# oresat-live-card.net
KiCad netlist of a schematic drawn in EAGLE
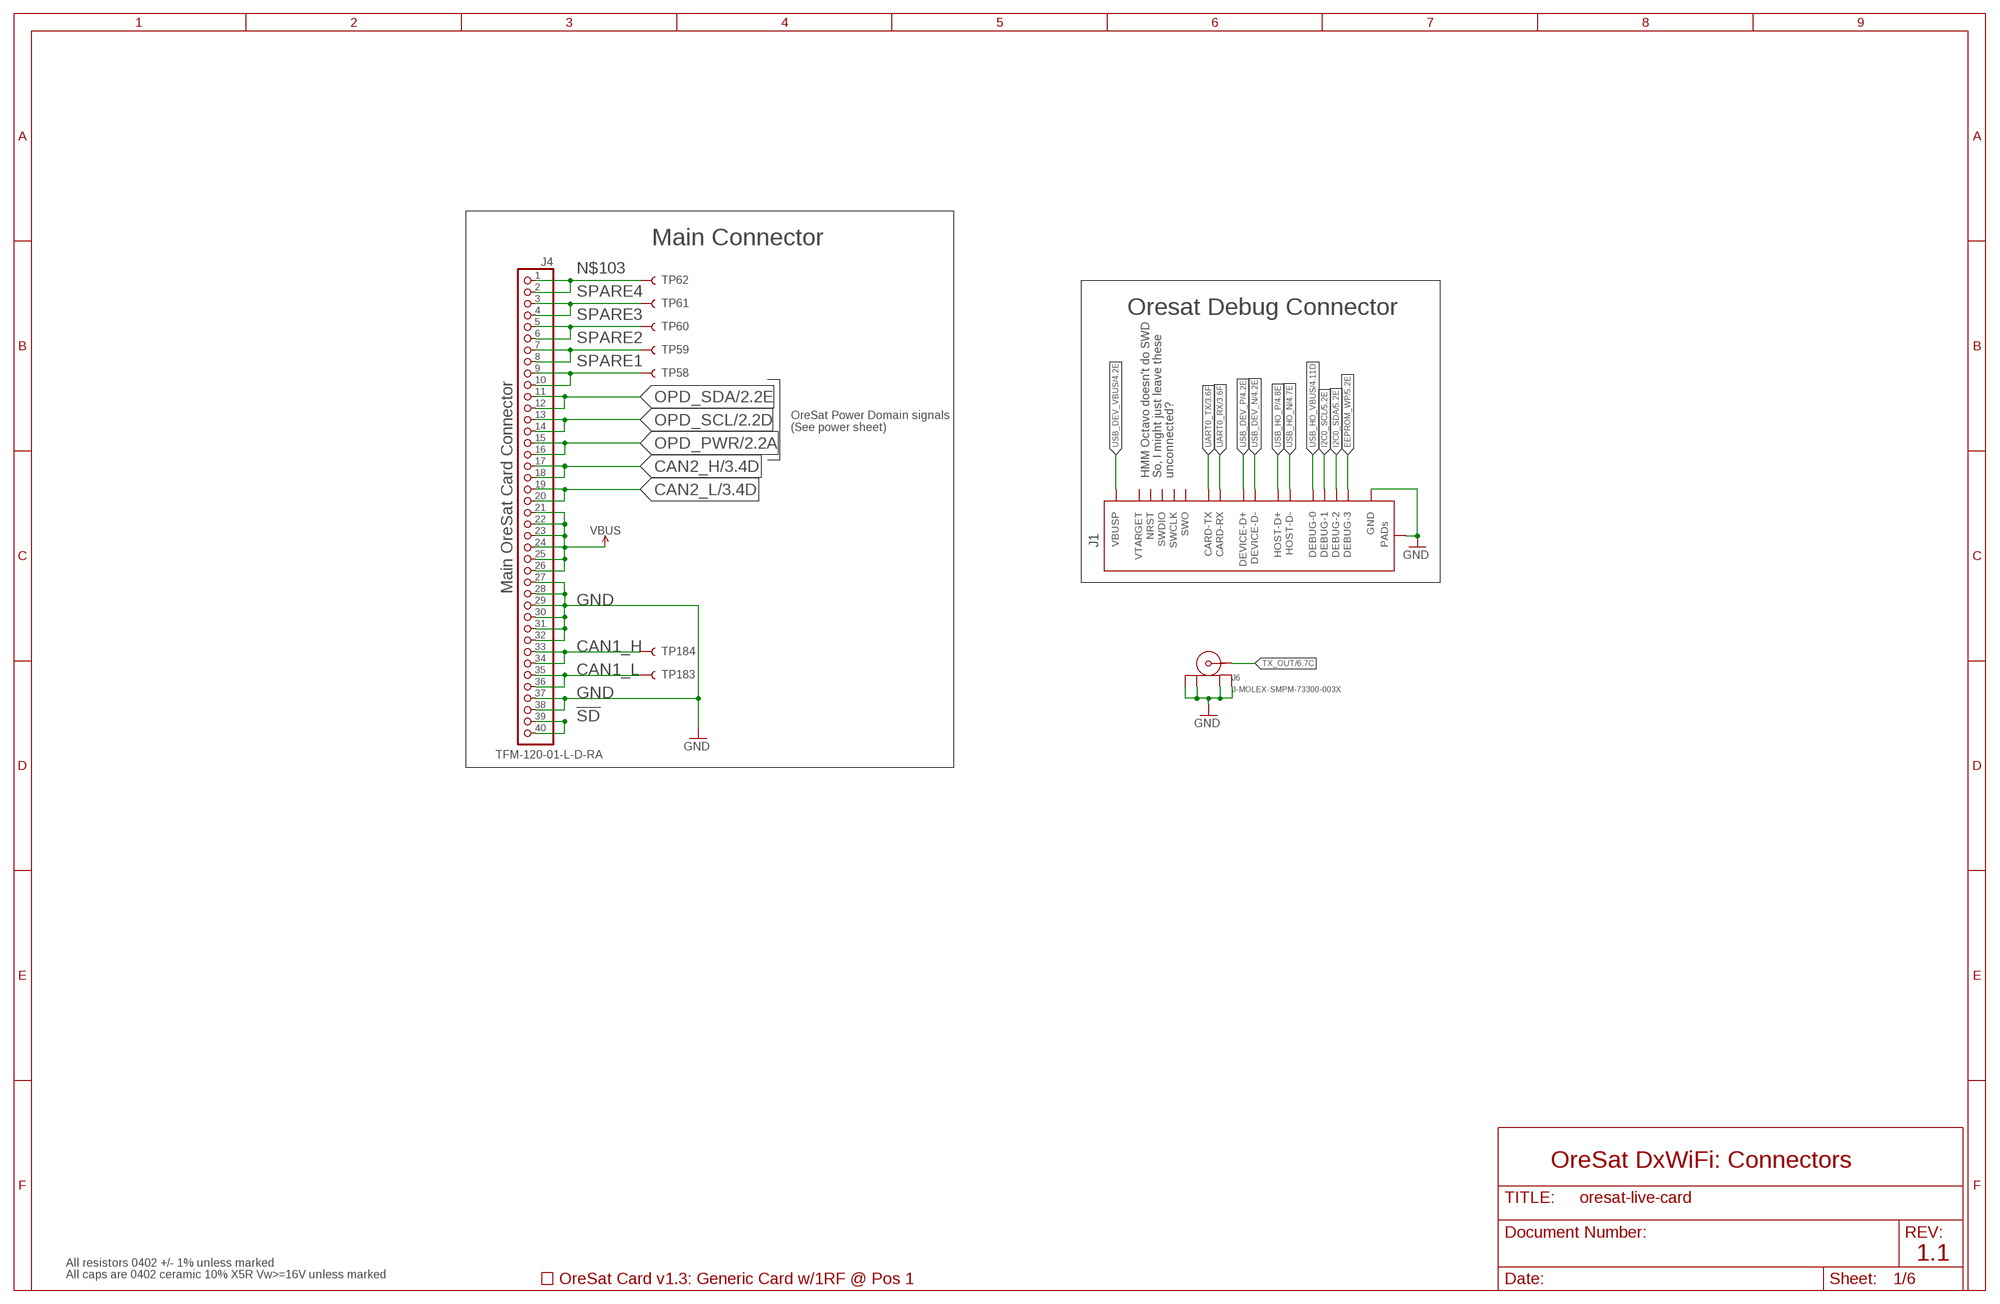
[diagram p0: schematic, sheet 1]
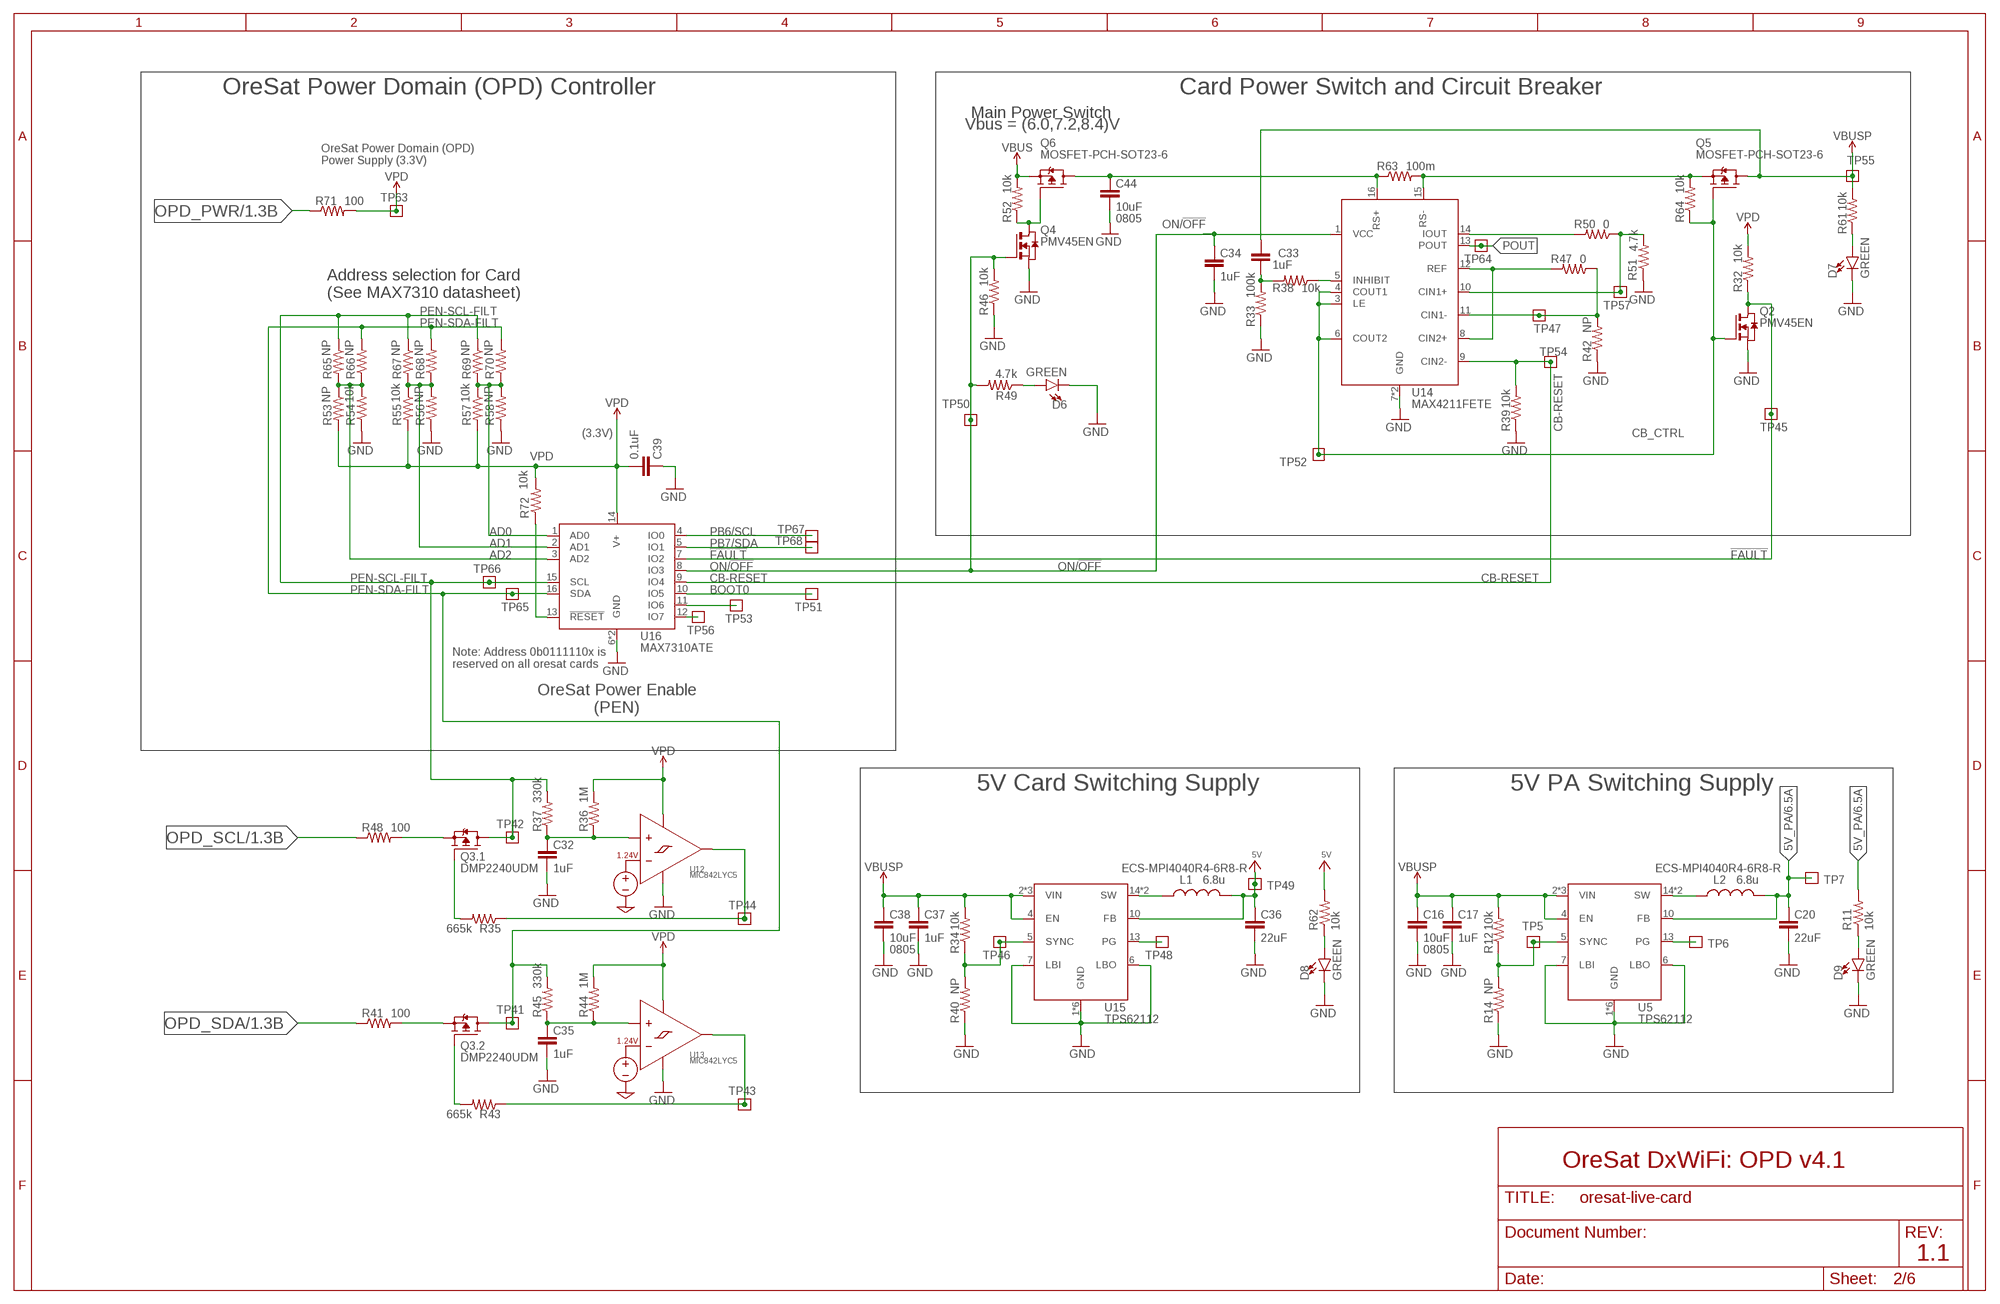
[diagram p1: schematic, sheet 2]
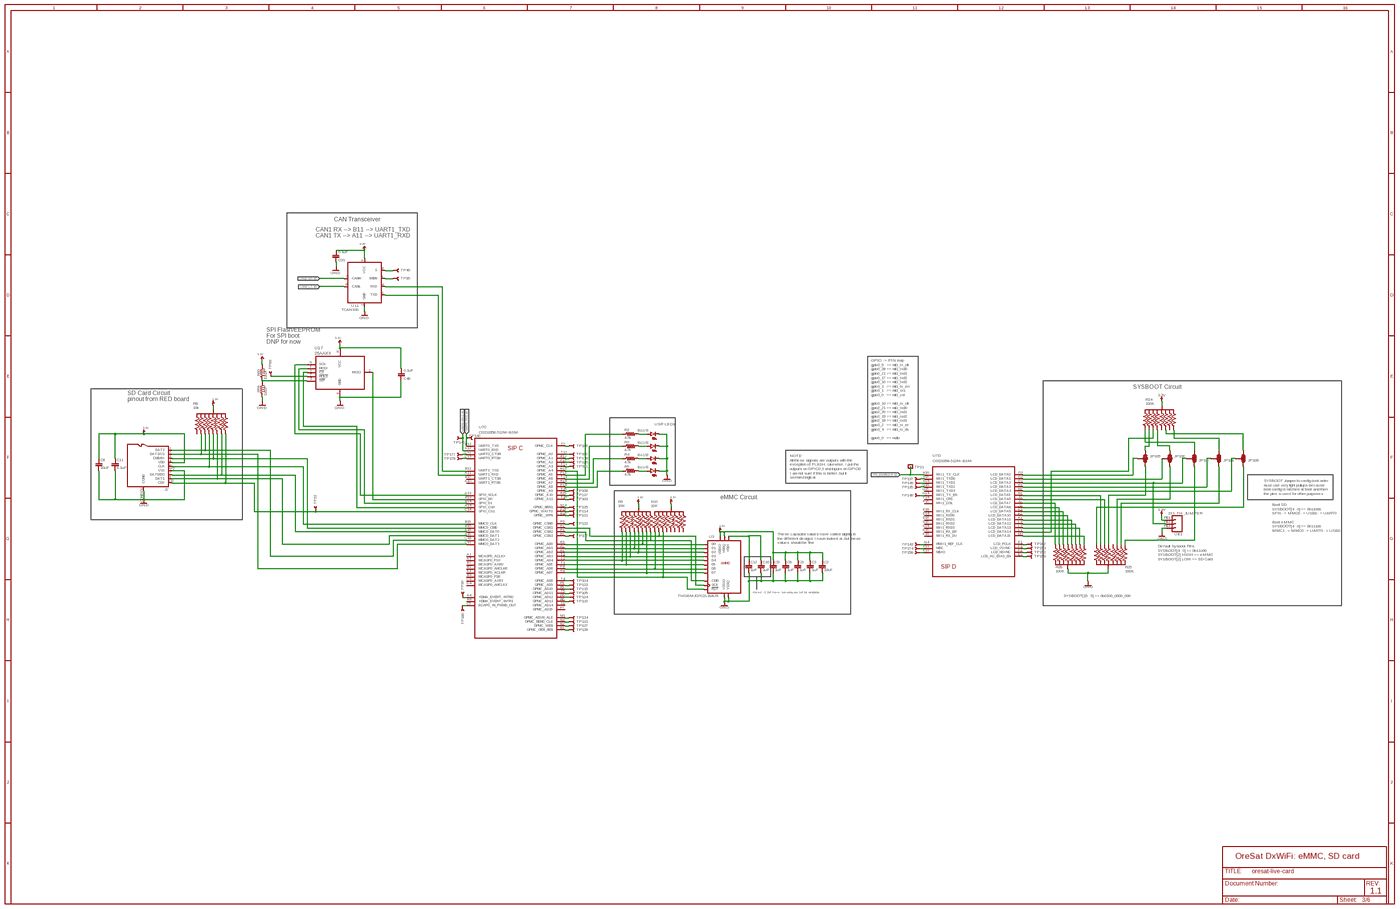
[diagram p2: schematic, sheet 3, overview]
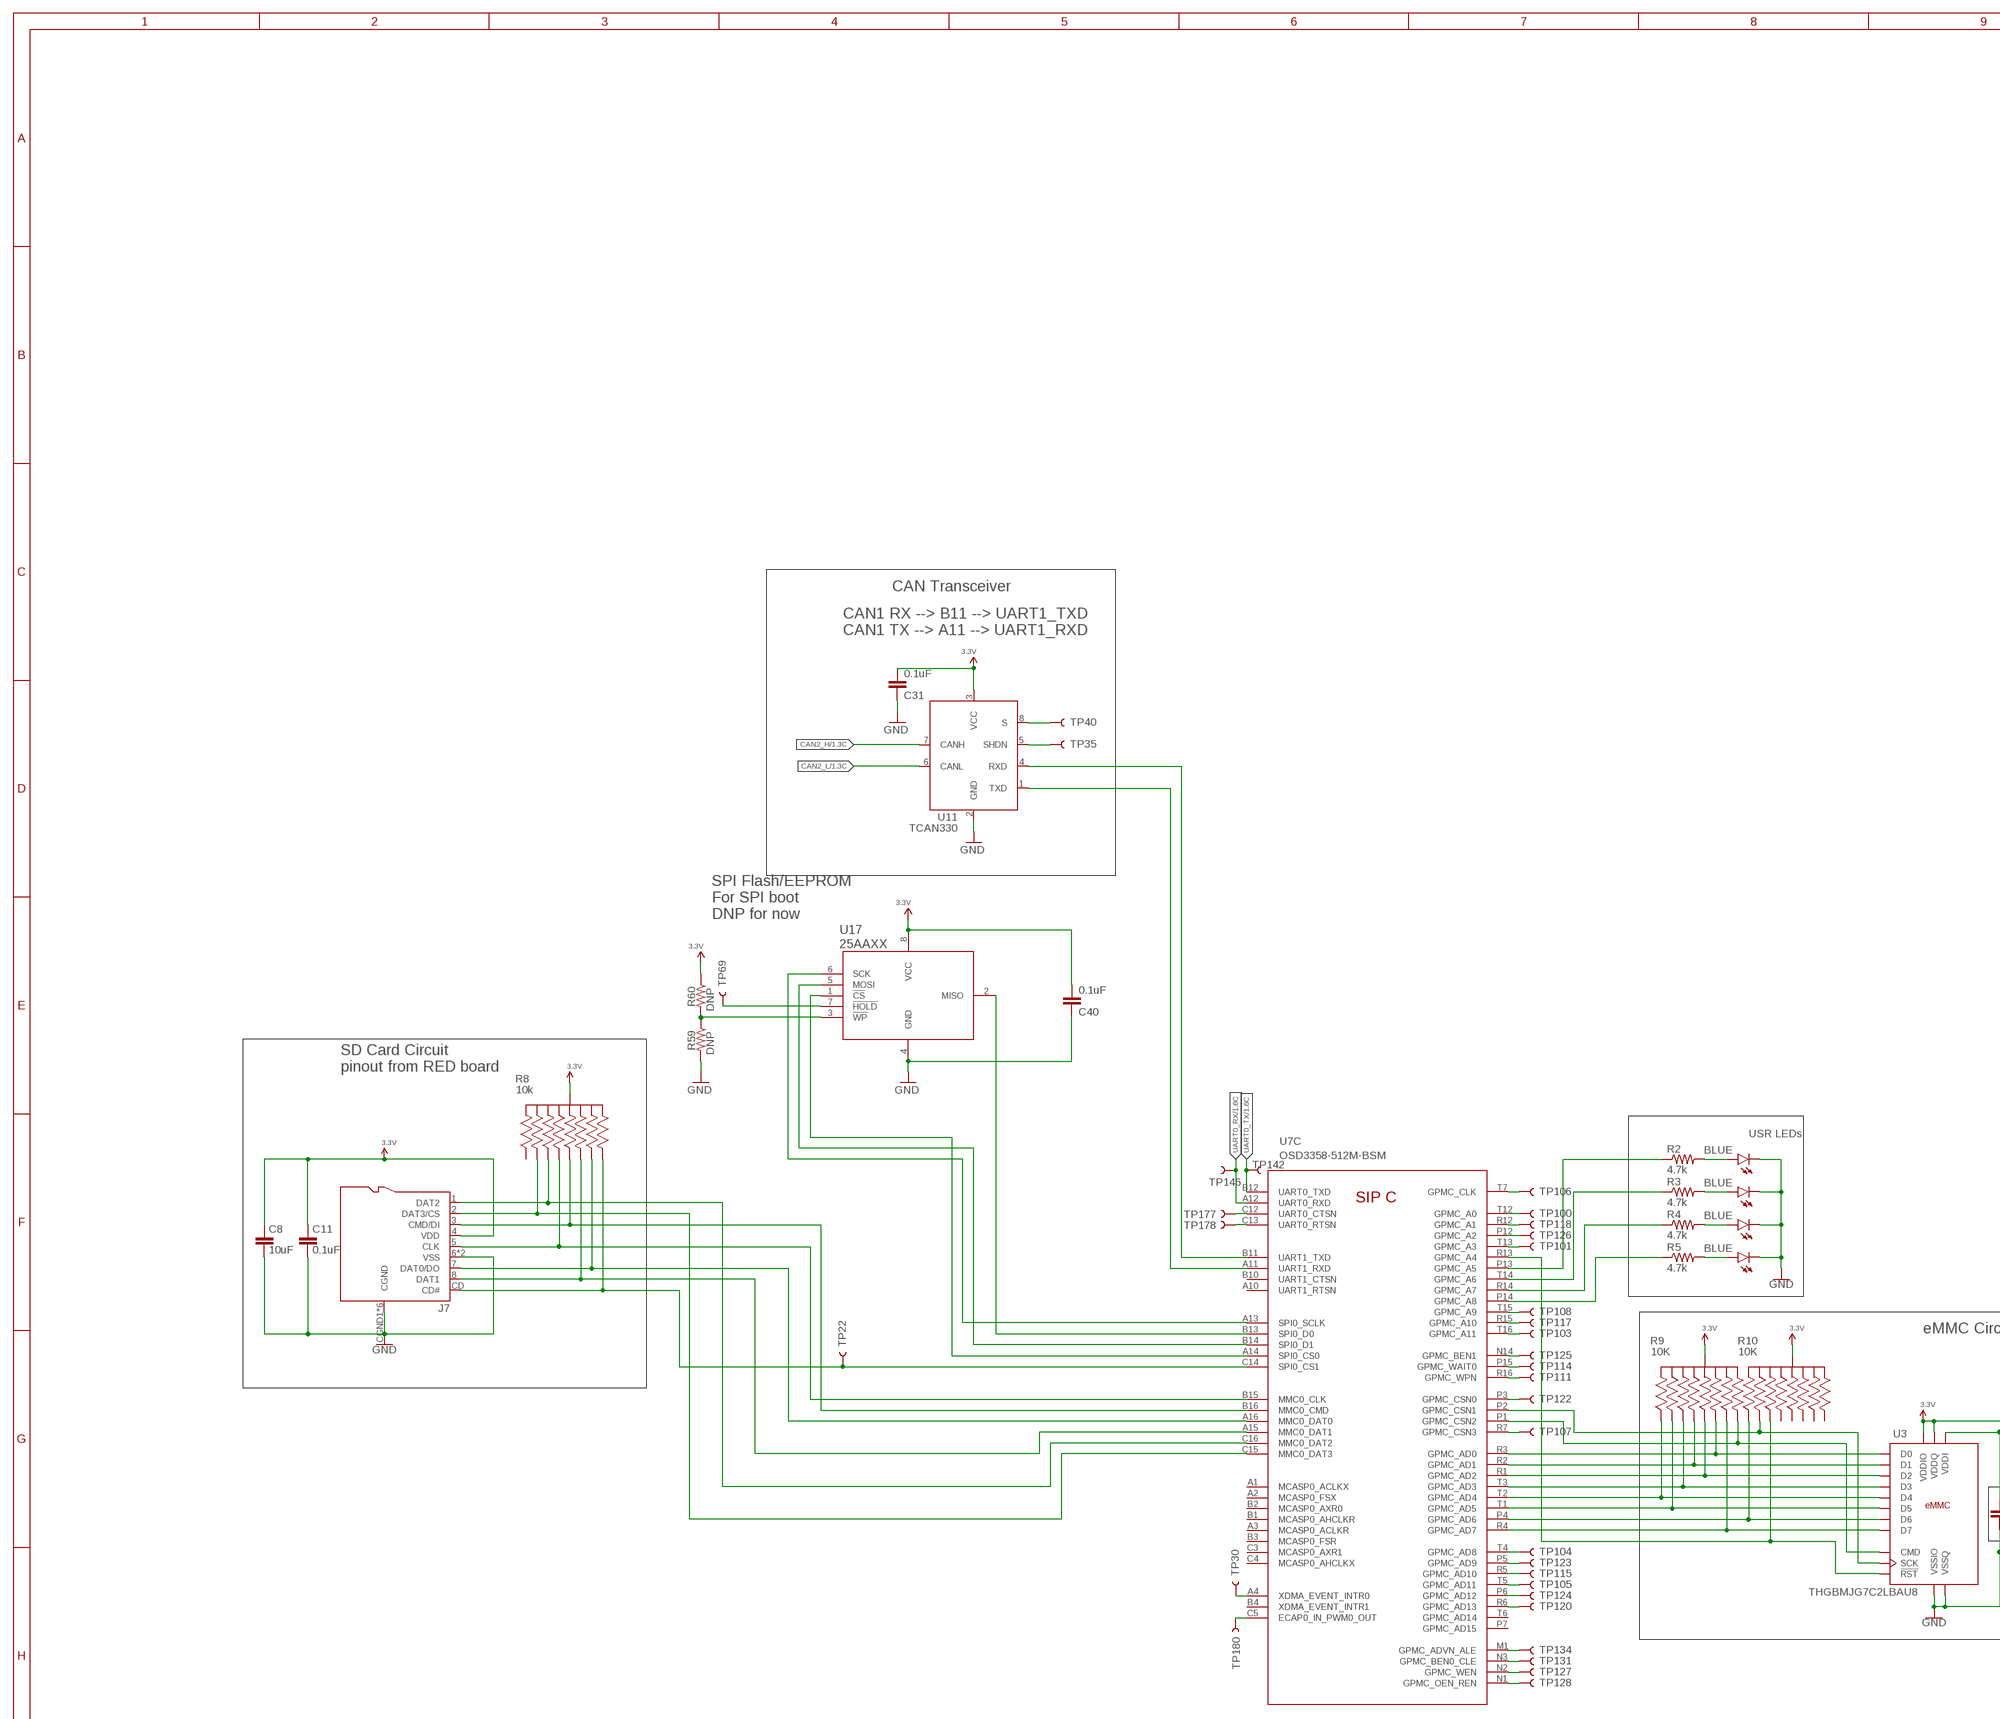
[diagram p3: schematic, sheet 3, part 1 of 4]
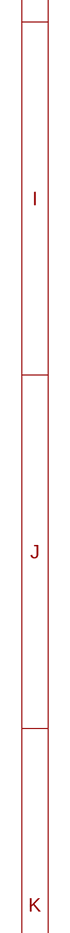
[diagram p4: schematic, sheet 3, part 2 of 4]
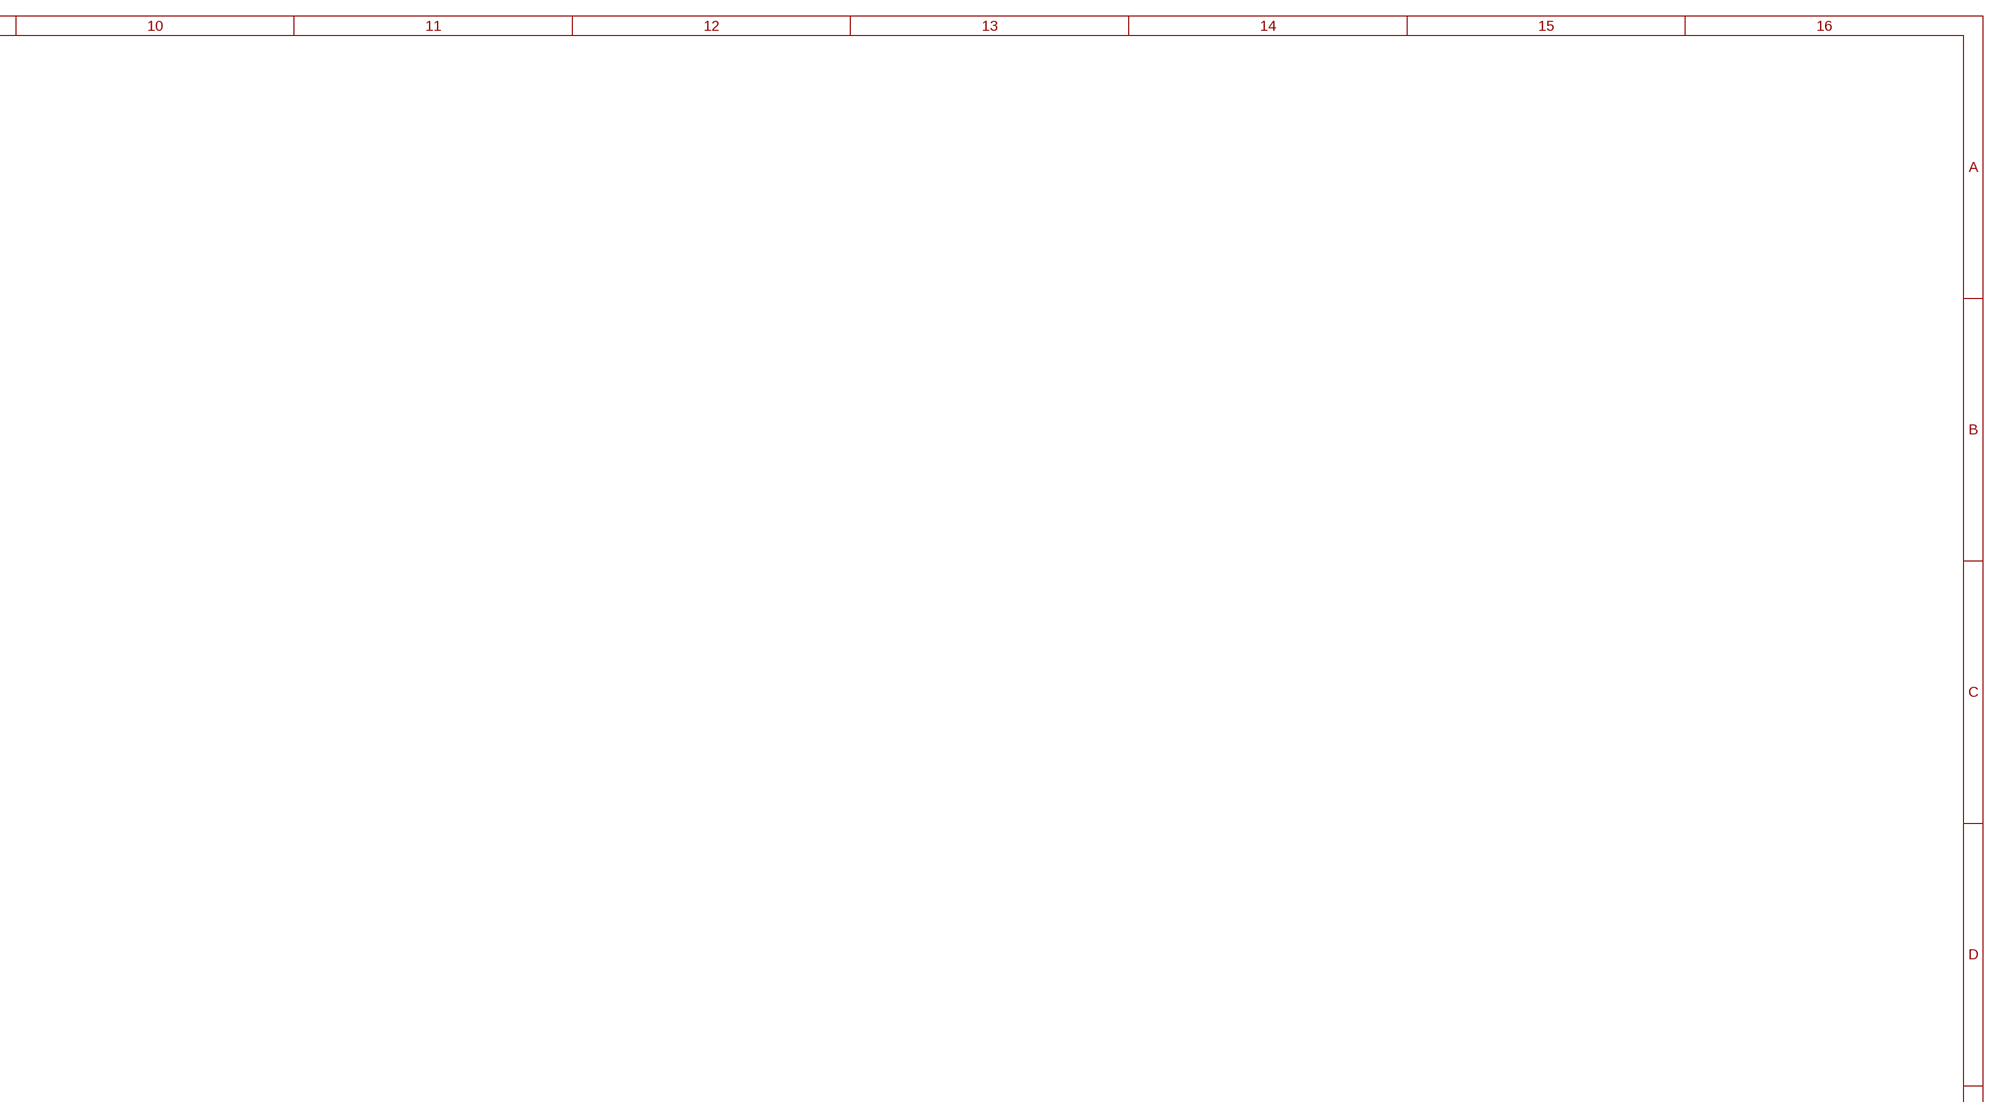
[diagram p5: schematic, sheet 3, part 3 of 4]
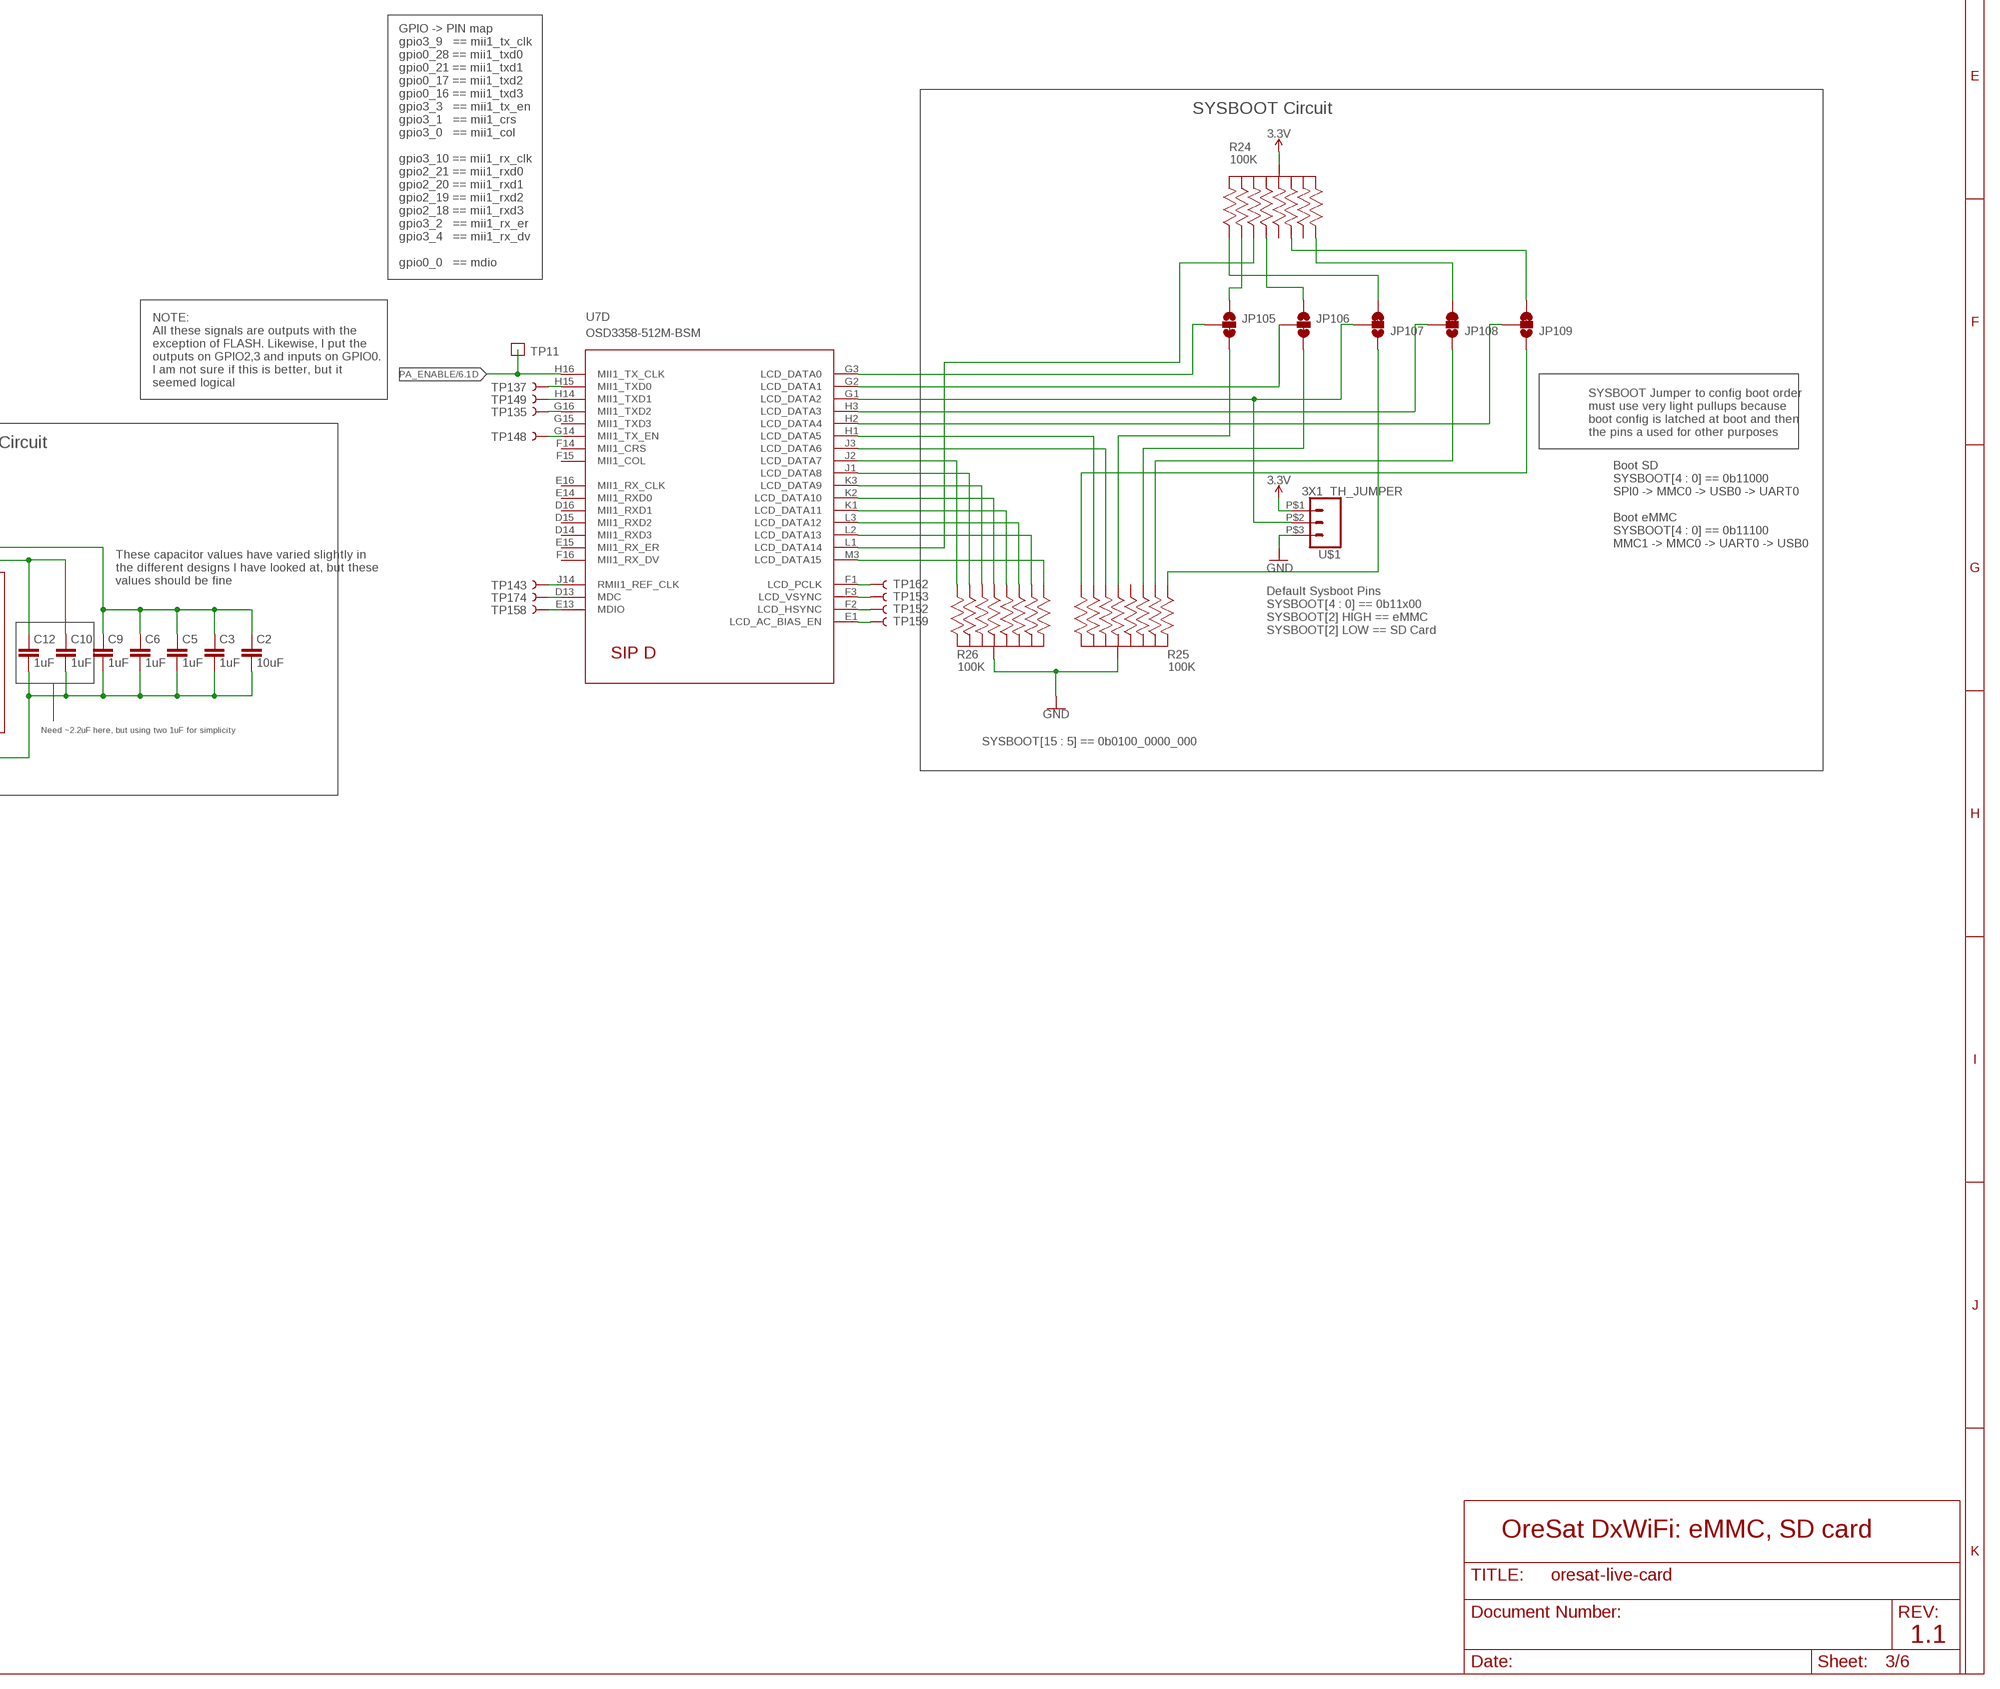
[diagram p6: schematic, sheet 3, part 4 of 4]
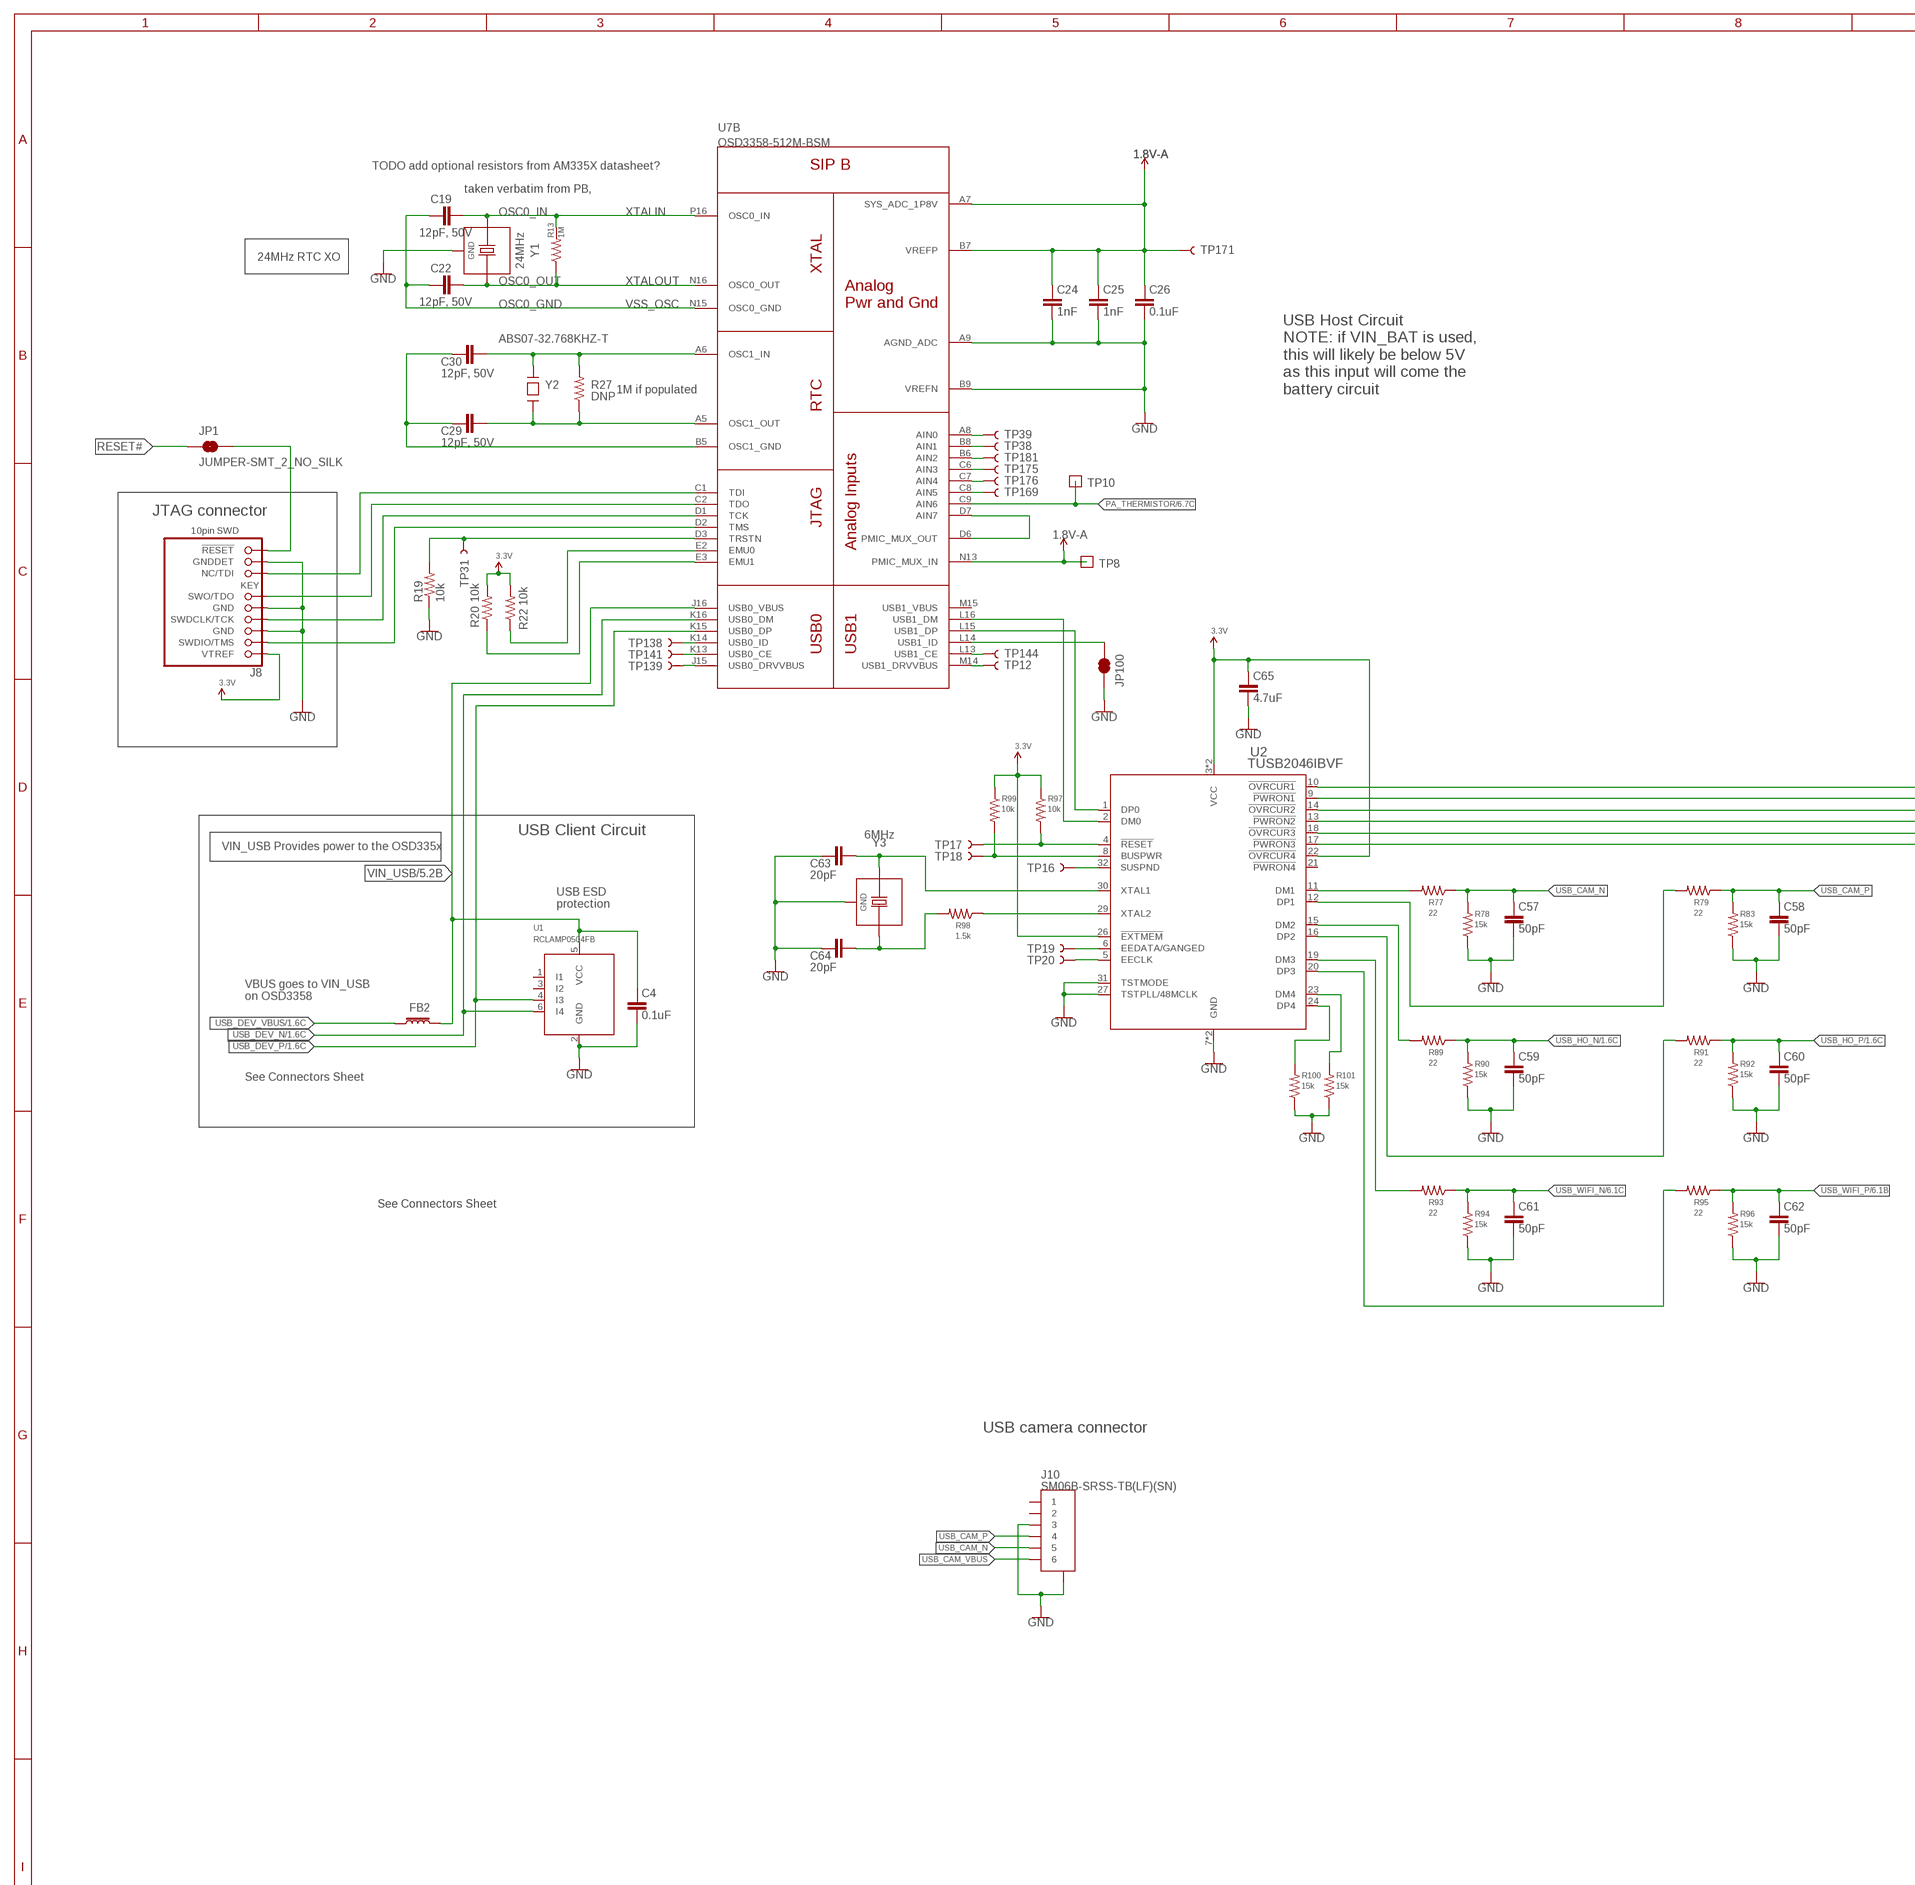
[diagram p7: schematic, sheet 4, part 1 of 2]
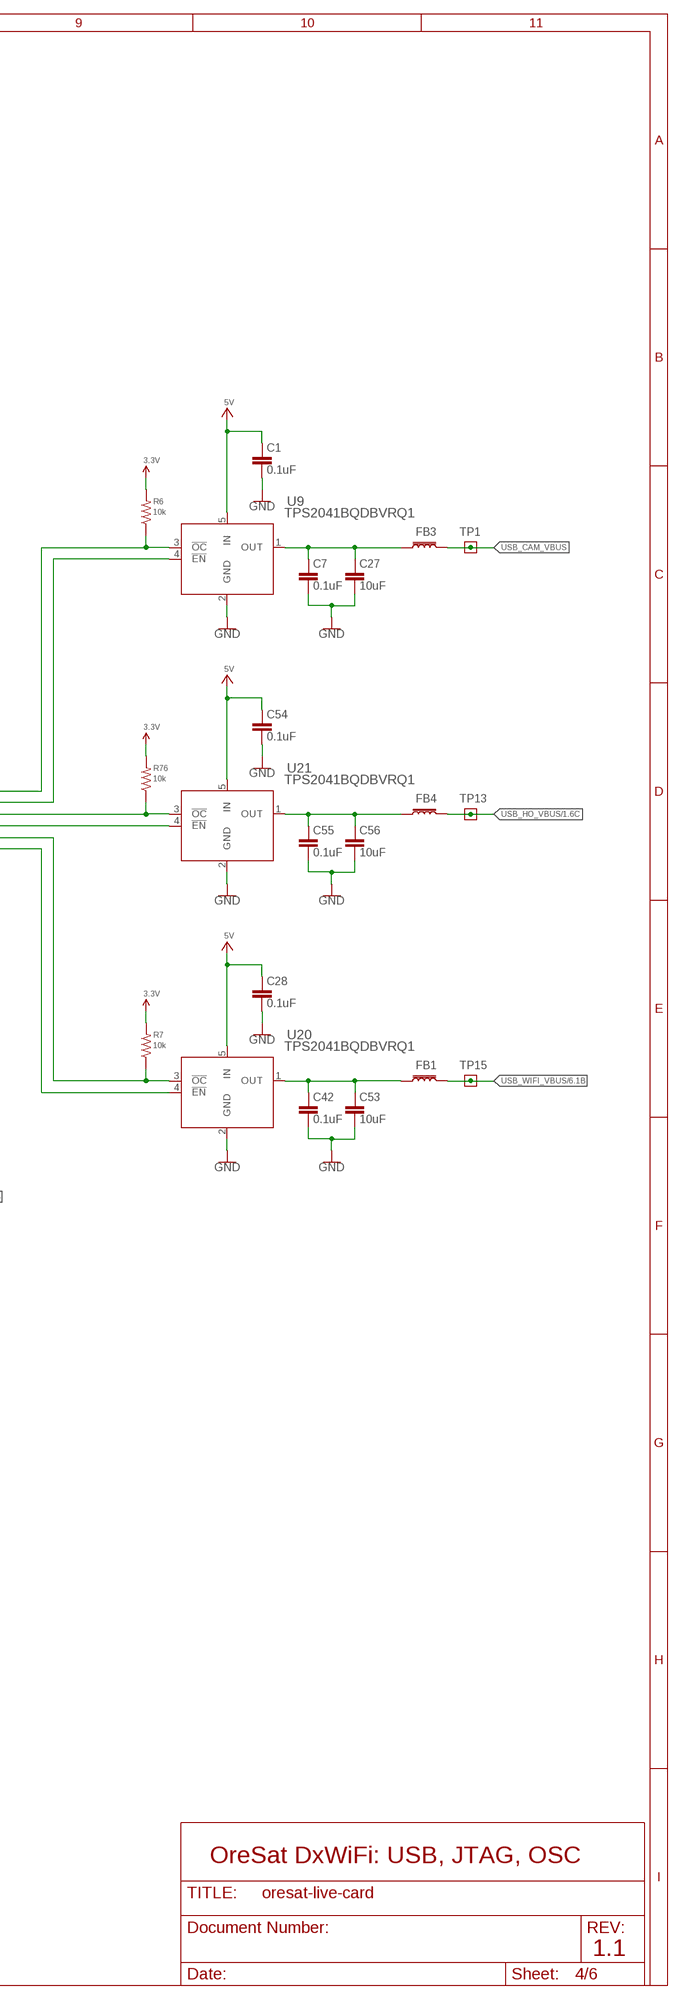
[diagram p8: schematic, sheet 4, part 2 of 2]
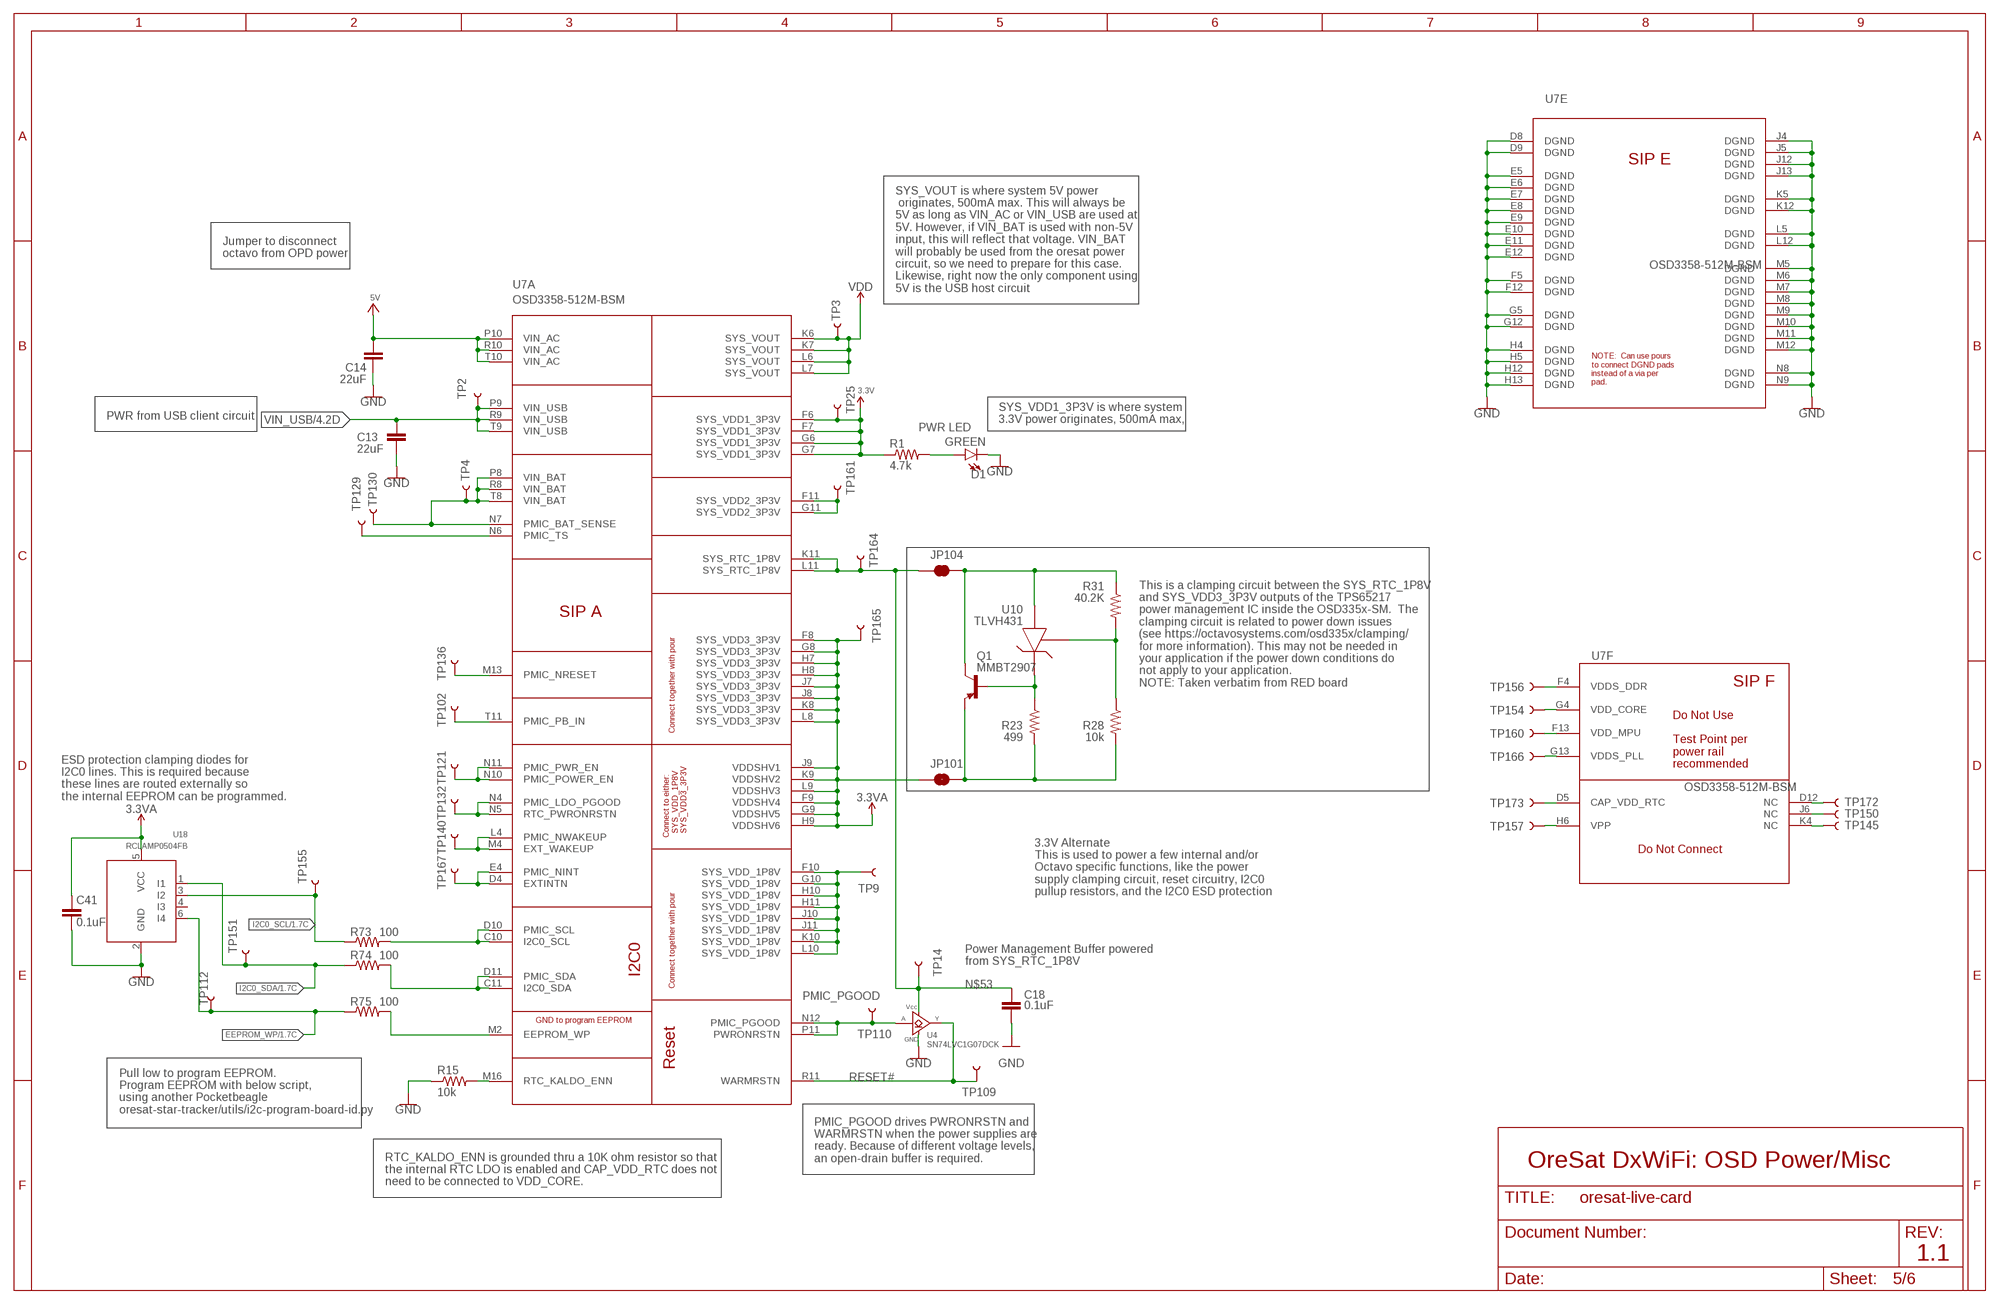
[diagram p9: schematic, sheet 5]
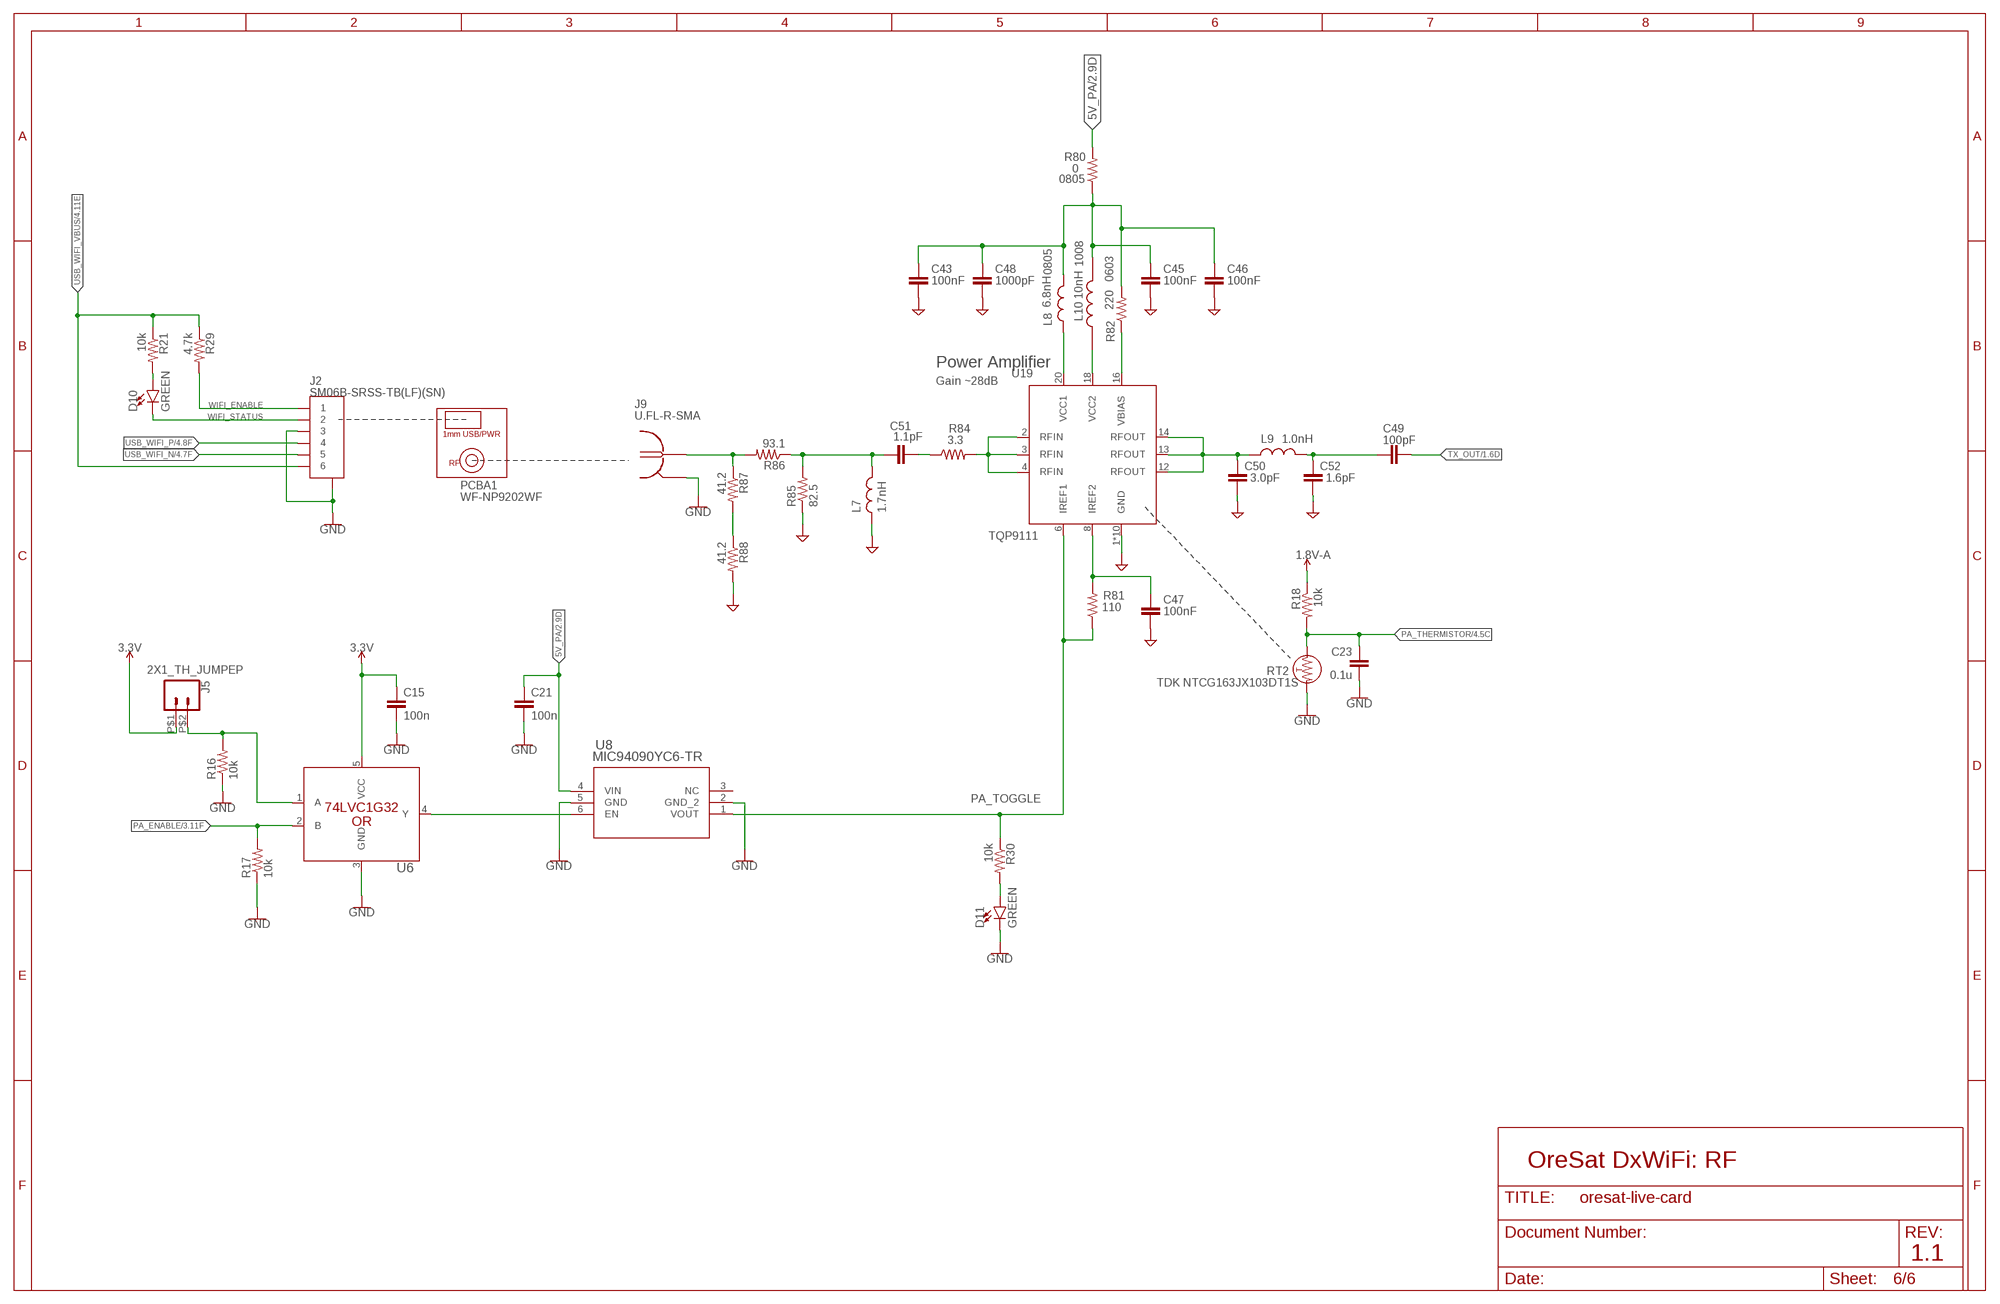
[diagram p10: schematic, sheet 6]

(export (version "E")
  (design (tool "Eeschema 10.0.6"))
  (components
    (comp (ref "C1")
      (value "0.1uF")
      (footprint "eagle-import:.0603-A")
      (libsource (lib "eagle-import") (part "C-EU0603-A"))
    )
    (comp (ref "C4")
      (value "0.1uF")
      (footprint "eagle-import:.0603-A")
      (libsource (lib "eagle-import") (part "C-EU0603-A"))
    )
    (comp (ref "C7")
      (value "0.1uF")
      (footprint "eagle-import:.0603-A")
      (libsource (lib "eagle-import") (part "C-EU0603-A"))
    )
    (comp (ref "C19")
      (value "12pF, 50V")
      (footprint "eagle-import:.0603-A")
      (libsource (lib "eagle-import") (part "C-EU0603-A"))
    )
    (comp (ref "C22")
      (value "12pF, 50V")
      (footprint "eagle-import:.0603-A")
      (libsource (lib "eagle-import") (part "C-EU0603-A"))
    )
    (comp (ref "C24")
      (value "1nF")
      (footprint "eagle-import:.0805-B")
      (libsource (lib "eagle-import") (part "C-EU0805-B"))
    )
    (comp (ref "C25")
      (value "1nF")
      (footprint "eagle-import:.0805-B")
      (libsource (lib "eagle-import") (part "C-EU0805-B"))
    )
    (comp (ref "C26")
      (value "0.1uF")
      (footprint "eagle-import:.0805-B")
      (libsource (lib "eagle-import") (part "C-EU0805-B"))
    )
    (comp (ref "C27")
      (value "10uF")
      (footprint "eagle-import:.0603-A")
      (libsource (lib "eagle-import") (part "C-EU0603-A"))
    )
    (comp (ref "C28")
      (value "0.1uF")
      (footprint "eagle-import:.0603-A")
      (libsource (lib "eagle-import") (part "C-EU0603-A"))
    )
    (comp (ref "C29")
      (value "12pF, 50V")
      (footprint "eagle-import:.0603-A")
      (libsource (lib "eagle-import") (part "C-EU0603-A"))
    )
    (comp (ref "C30")
      (value "12pF, 50V")
      (footprint "eagle-import:.0603-A")
      (libsource (lib "eagle-import") (part "C-EU0603-A"))
    )
    (comp (ref "C42")
      (value "0.1uF")
      (footprint "eagle-import:.0603-A")
      (libsource (lib "eagle-import") (part "C-EU0603-A"))
    )
    (comp (ref "C53")
      (value "10uF")
      (footprint "eagle-import:.0603-A")
      (libsource (lib "eagle-import") (part "C-EU0603-A"))
    )
    (comp (ref "C54")
      (value "0.1uF")
      (footprint "eagle-import:.0603-A")
      (libsource (lib "eagle-import") (part "C-EU0603-A"))
    )
    (comp (ref "C55")
      (value "0.1uF")
      (footprint "eagle-import:.0603-A")
      (libsource (lib "eagle-import") (part "C-EU0603-A"))
    )
    (comp (ref "C56")
      (value "10uF")
      (footprint "eagle-import:.0603-A")
      (libsource (lib "eagle-import") (part "C-EU0603-A"))
    )
    (comp (ref "C57")
      (value "50pF")
      (footprint "eagle-import:.0603-A")
      (libsource (lib "eagle-import") (part "C-EU0603-A"))
    )
    (comp (ref "C58")
      (value "50pF")
      (footprint "eagle-import:.0603-A")
      (libsource (lib "eagle-import") (part "C-EU0603-A"))
    )
    (comp (ref "C59")
      (value "50pF")
      (footprint "eagle-import:.0603-A")
      (libsource (lib "eagle-import") (part "C-EU0603-A"))
    )
    (comp (ref "C60")
      (value "50pF")
      (footprint "eagle-import:.0603-A")
      (libsource (lib "eagle-import") (part "C-EU0603-A"))
    )
    (comp (ref "C61")
      (value "50pF")
      (footprint "eagle-import:.0603-A")
      (libsource (lib "eagle-import") (part "C-EU0603-A"))
    )
    (comp (ref "C62")
      (value "50pF")
      (footprint "eagle-import:.0603-A")
      (libsource (lib "eagle-import") (part "C-EU0603-A"))
    )
    (comp (ref "C63")
      (value "20pF")
      (footprint "eagle-import:.0603-A")
      (libsource (lib "eagle-import") (part "C-EU0603-A"))
    )
    (comp (ref "C64")
      (value "20pF")
      (footprint "eagle-import:.0603-A")
      (libsource (lib "eagle-import") (part "C-EU0603-A"))
    )
    (comp (ref "C65")
      (value "4.7uF")
      (footprint "eagle-import:.0603-A")
      (libsource (lib "eagle-import") (part "C-EU0603-A"))
    )
    (comp (ref "FB1")
      (value "30Ω/1.8A")
      (footprint "eagle-import:0603")
      (fields (field (name "MPN") "BLM18KG300JH1D"))
      (libsource (lib "eagle-import") (part "FERRITE_BEAD-0603"))
    )
    (comp (ref "FB2")
      (value "30Ω/1.8A")
      (footprint "eagle-import:0603")
      (fields (field (name "MPN") "BLM18KG300JH1D"))
      (libsource (lib "eagle-import") (part "FERRITE_BEAD-0603"))
    )
    (comp (ref "FB3")
      (value "30Ω/1.8A")
      (footprint "eagle-import:0603")
      (fields (field (name "MPN") "BLM18KG300JH1D"))
      (libsource (lib "eagle-import") (part "FERRITE_BEAD-0603"))
    )
    (comp (ref "FB4")
      (value "30Ω/1.8A")
      (footprint "eagle-import:0603")
      (fields (field (name "MPN") "BLM18KG300JH1D"))
      (libsource (lib "eagle-import") (part "FERRITE_BEAD-0603"))
    )
    (comp (ref "J8")
      (value "FTSH-105-XX-X-DV-K")
      (footprint "eagle-import:CON10_2X5_DUK_FTSH")
      (libsource (lib "eagle-import") (part "FTSH-105-XX-X-DV-K"))
    )
    (comp (ref "J10")
      (value "SM06B-SRSS-TB(LF)(SN)")
      (footprint "eagle-import:CONN_SM06B-SRSS-TB_JST")
      (fields (field (name "COPYRIGHT") "Copyright (C) 2018 Accelerated Designs. All rights reserved"))
      (libsource (lib "eagle-import") (part "SM06B-SRSS-TB(LF)(SN)"))
    )
    (comp (ref "JP1")
      (value "JUMPER-SMT_2_NO_SILK")
      (footprint "eagle-import:SMT-JUMPER_2_NO_SILK")
      (libsource (lib "eagle-import") (part "JUMPER-SMT_2_NO_SILK"))
    )
    (comp (ref "JP100")
      (value "JUMPER-SMT_2_NC_TRACE_SILK")
      (footprint "eagle-import:SMT-JUMPER_2_NC_TRACE_SILK")
      (libsource (lib "eagle-import") (part "JUMPER-SMT_2_NC_TRACE_SILK"))
    )
    (comp (ref "R6")
      (value "10k")
      (footprint "eagle-import:.0603-A")
      (libsource (lib "eagle-import") (part "R-US_0603-A"))
    )
    (comp (ref "R7")
      (value "10k")
      (footprint "eagle-import:.0603-A")
      (libsource (lib "eagle-import") (part "R-US_0603-A"))
    )
    (comp (ref "R13")
      (value "1M")
      (footprint "eagle-import:.0603-A")
      (libsource (lib "eagle-import") (part "R-US_0603-A"))
    )
    (comp (ref "R19")
      (value "10k")
      (footprint "eagle-import:.0603-A")
      (libsource (lib "eagle-import") (part "R-US_0603-A"))
    )
    (comp (ref "R20")
      (value "10k")
      (footprint "eagle-import:.0603-A")
      (libsource (lib "eagle-import") (part "R-US_0603-A"))
    )
    (comp (ref "R22")
      (value "10k")
      (footprint "eagle-import:.0603-A")
      (libsource (lib "eagle-import") (part "R-US_0603-A"))
    )
    (comp (ref "R27")
      (value "DNP")
      (footprint "eagle-import:.0603-A")
      (libsource (lib "eagle-import") (part "R-US_0603-A"))
    )
    (comp (ref "R76")
      (value "10k")
      (footprint "eagle-import:.0603-A")
      (libsource (lib "eagle-import") (part "R-US_0603-A"))
    )
    (comp (ref "R77")
      (value "22")
      (footprint "eagle-import:.0603-A")
      (libsource (lib "eagle-import") (part "R-US_0603-A"))
    )
    (comp (ref "R78")
      (value "15k")
      (footprint "eagle-import:.0603-A")
      (libsource (lib "eagle-import") (part "R-US_0603-A"))
    )
    (comp (ref "R79")
      (value "22")
      (footprint "eagle-import:.0603-A")
      (libsource (lib "eagle-import") (part "R-US_0603-A"))
    )
    (comp (ref "R83")
      (value "15k")
      (footprint "eagle-import:.0603-A")
      (libsource (lib "eagle-import") (part "R-US_0603-A"))
    )
    (comp (ref "R89")
      (value "22")
      (footprint "eagle-import:.0603-A")
      (libsource (lib "eagle-import") (part "R-US_0603-A"))
    )
    (comp (ref "R90")
      (value "15k")
      (footprint "eagle-import:.0603-A")
      (libsource (lib "eagle-import") (part "R-US_0603-A"))
    )
    (comp (ref "R91")
      (value "22")
      (footprint "eagle-import:.0603-A")
      (libsource (lib "eagle-import") (part "R-US_0603-A"))
    )
    (comp (ref "R92")
      (value "15k")
      (footprint "eagle-import:.0603-A")
      (libsource (lib "eagle-import") (part "R-US_0603-A"))
    )
    (comp (ref "R93")
      (value "22")
      (footprint "eagle-import:.0603-A")
      (libsource (lib "eagle-import") (part "R-US_0603-A"))
    )
    (comp (ref "R94")
      (value "15k")
      (footprint "eagle-import:.0603-A")
      (libsource (lib "eagle-import") (part "R-US_0603-A"))
    )
    (comp (ref "R95")
      (value "22")
      (footprint "eagle-import:.0603-A")
      (libsource (lib "eagle-import") (part "R-US_0603-A"))
    )
    (comp (ref "R96")
      (value "15k")
      (footprint "eagle-import:.0603-A")
      (libsource (lib "eagle-import") (part "R-US_0603-A"))
    )
    (comp (ref "R97")
      (value "10k")
      (footprint "eagle-import:.0603-A")
      (libsource (lib "eagle-import") (part "R-US_0603-A"))
    )
    (comp (ref "R98")
      (value "1.5k")
      (footprint "eagle-import:.0603-A")
      (libsource (lib "eagle-import") (part "R-US_0603-A"))
    )
    (comp (ref "R99")
      (value "10k")
      (footprint "eagle-import:.0603-A")
      (libsource (lib "eagle-import") (part "R-US_0603-A"))
    )
    (comp (ref "R100")
      (value "15k")
      (footprint "eagle-import:.0603-A")
      (libsource (lib "eagle-import") (part "R-US_0603-A"))
    )
    (comp (ref "R101")
      (value "15k")
      (footprint "eagle-import:.0603-A")
      (libsource (lib "eagle-import") (part "R-US_0603-A"))
    )
    (comp (ref "TP1")
      (value "TEST-POINT")
      (footprint "eagle-import:2MM-TEST-POINT")
      (libsource (lib "eagle-import") (part "TEST-POINT"))
    )
    (comp (ref "TP8")
      (value "TEST-POINT")
      (footprint "eagle-import:2MM-TEST-POINT")
      (libsource (lib "eagle-import") (part "TEST-POINT"))
    )
    (comp (ref "TP10")
      (value "TEST-POINT")
      (footprint "eagle-import:2MM-TEST-POINT")
      (libsource (lib "eagle-import") (part "TEST-POINT"))
    )
    (comp (ref "TP12")
      (value "TEST-POINT3X4")
      (footprint "eagle-import:PAD.03X.04")
      (libsource (lib "eagle-import") (part "TEST-POINT3X4"))
    )
    (comp (ref "TP13")
      (value "TEST-POINT")
      (footprint "eagle-import:2MM-TEST-POINT")
      (libsource (lib "eagle-import") (part "TEST-POINT"))
    )
    (comp (ref "TP15")
      (value "TEST-POINT")
      (footprint "eagle-import:2MM-TEST-POINT")
      (libsource (lib "eagle-import") (part "TEST-POINT"))
    )
    (comp (ref "TP16")
      (value "TEST-POINT3X4")
      (footprint "eagle-import:PAD.03X.04")
      (libsource (lib "eagle-import") (part "TEST-POINT3X4"))
    )
    (comp (ref "TP17")
      (value "TEST-POINT3X4")
      (footprint "eagle-import:PAD.03X.04")
      (libsource (lib "eagle-import") (part "TEST-POINT3X4"))
    )
    (comp (ref "TP18")
      (value "TEST-POINT3X4")
      (footprint "eagle-import:PAD.03X.04")
      (libsource (lib "eagle-import") (part "TEST-POINT3X4"))
    )
    (comp (ref "TP19")
      (value "TEST-POINT3X4")
      (footprint "eagle-import:PAD.03X.04")
      (libsource (lib "eagle-import") (part "TEST-POINT3X4"))
    )
    (comp (ref "TP20")
      (value "TEST-POINT3X4")
      (footprint "eagle-import:PAD.03X.04")
      (libsource (lib "eagle-import") (part "TEST-POINT3X4"))
    )
    (comp (ref "TP31")
      (value "TEST-POINT3X4")
      (footprint "eagle-import:PAD.03X.04")
      (libsource (lib "eagle-import") (part "TEST-POINT3X4"))
    )
    (comp (ref "TP38")
      (value "TEST-POINT3X4")
      (footprint "eagle-import:PAD.03X.04")
      (libsource (lib "eagle-import") (part "TEST-POINT3X4"))
    )
    (comp (ref "TP39")
      (value "TEST-POINT3X4")
      (footprint "eagle-import:PAD.03X.04")
      (libsource (lib "eagle-import") (part "TEST-POINT3X4"))
    )
    (comp (ref "TP138")
      (value "TEST-POINT3X4")
      (footprint "eagle-import:PAD.03X.04")
      (libsource (lib "eagle-import") (part "TEST-POINT3X4"))
    )
    (comp (ref "TP139")
      (value "TEST-POINT3X4")
      (footprint "eagle-import:PAD.03X.04")
      (libsource (lib "eagle-import") (part "TEST-POINT3X4"))
    )
    (comp (ref "TP141")
      (value "TEST-POINT3X4")
      (footprint "eagle-import:PAD.03X.04")
      (libsource (lib "eagle-import") (part "TEST-POINT3X4"))
    )
    (comp (ref "TP144")
      (value "TEST-POINT3X4")
      (footprint "eagle-import:PAD.03X.04")
      (libsource (lib "eagle-import") (part "TEST-POINT3X4"))
    )
    (comp (ref "TP169")
      (value "TEST-POINT3X4")
      (footprint "eagle-import:PAD.03X.04")
      (libsource (lib "eagle-import") (part "TEST-POINT3X4"))
    )
    (comp (ref "TP171")
      (value "TEST-POINT3X4")
      (footprint "eagle-import:PAD.03X.04")
      (libsource (lib "eagle-import") (part "TEST-POINT3X4"))
    )
    (comp (ref "TP175")
      (value "TEST-POINT3X4")
      (footprint "eagle-import:PAD.03X.04")
      (libsource (lib "eagle-import") (part "TEST-POINT3X4"))
    )
    (comp (ref "TP176")
      (value "TEST-POINT3X4")
      (footprint "eagle-import:PAD.03X.04")
      (libsource (lib "eagle-import") (part "TEST-POINT3X4"))
    )
    (comp (ref "TP181")
      (value "TEST-POINT3X4")
      (footprint "eagle-import:PAD.03X.04")
      (libsource (lib "eagle-import") (part "TEST-POINT3X4"))
    )
    (comp (ref "U1")
      (value "RCLAMP0504FB")
      (footprint "eagle-import:SC70-6")
      (fields (field (name "MPN") "RCLAMP0504FBTCT"))
      (libsource (lib "eagle-import") (part "RCLAMP0504FB"))
    )
    (comp (ref "U2")
      (value "TUSB2046IBVF")
      (footprint "eagle-import:QFP80P900X900X160-32N")
      (libsource (lib "eagle-import") (part "TUSB2046IBVF"))
    )
    (comp (ref "U7")
      (value "OSD3358-512M-BSM")
      (footprint "eagle-import:OSD335X-BGA-256")
      (fields (field (name "MFR") "Octavo Systems"))
      (libsource (lib "eagle-import") (part "OSD3358-512M-BSM"))
    )
    (comp (ref "U9")
      (value "TPS2041BQDBVRQ1")
      (footprint "eagle-import:DBV5")
      (fields (field (name "COPYRIGHT") "Copyright (C) 2021 Ultra Librarian. All rights reserved."))
      (libsource (lib "eagle-import") (part "TPS2041BQDBVRQ1"))
    )
    (comp (ref "U20")
      (value "TPS2041BQDBVRQ1")
      (footprint "eagle-import:DBV5")
      (fields (field (name "COPYRIGHT") "Copyright (C) 2021 Ultra Librarian. All rights reserved."))
      (libsource (lib "eagle-import") (part "TPS2041BQDBVRQ1"))
    )
    (comp (ref "U21")
      (value "TPS2041BQDBVRQ1")
      (footprint "eagle-import:DBV5")
      (fields (field (name "COPYRIGHT") "Copyright (C) 2021 Ultra Librarian. All rights reserved."))
      (libsource (lib "eagle-import") (part "TPS2041BQDBVRQ1"))
    )
    (comp (ref "Y1")
      (value "24MHz")
      (footprint "eagle-import:5X3.2-4SMD")
      (fields (field (name "MPN") "ECS-240-12-30BQ-AEN-TR"))
      (libsource (lib "eagle-import") (part "ECS-240-12-30BQ-AEN-TR"))
    )
    (comp (ref "Y2")
      (value "ABS07-32.768KHZ-T")
      (footprint "eagle-import:CRYSTAL_3.2X1.5")
      (libsource (lib "eagle-import") (part "ABS07-32.768KHZ-T"))
    )
    (comp (ref "Y3")
      (value "6MHz")
      (footprint "eagle-import:ECS_ECS-060-18-20BM-JEN-TR")
      (fields (field (name "MF") "ECS Inc.") (field (name "MP") "ECS-060-18-20BM-JEN-TR"))
      (libsource (lib "eagle-import") (part "ECS-060-18-20BM-JEN-TR"))
    )
    (comp (ref "J1")
      (value "ORESAT-DEBUG-CONNECTOR-CARD")
      (footprint "eagle-import:TE_2-1734592-0")
      (fields (field (name "MPN") "2-1734592-0"))
      (libsource (lib "eagle-import") (part "ORESAT-DEBUG-CONNECTOR-CARD"))
    )
    (comp (ref "J4")
      (value "TFM-120-01-L-D-RA")
      (footprint "eagle-import:J-SAMTEC-TFM-120-X1-XXX-D-RA")
      (libsource (lib "eagle-import") (part "J-SAMTEC-TFM-120-X1-XXX-D-RA"))
    )
    (comp (ref "J6")
      (value "J-MOLEX-SMPM-73300-003X")
      (footprint "eagle-import:J-MOLEX-SMPM-073300-003X")
      (fields (field (name "MFG") "MOLEX"))
      (libsource (lib "eagle-import") (part "J-MOLEX-SMPM-73300-003X"))
    )
    (comp (ref "PCB1")
      (value "ORESAT-CARD-V1.3-GENERIC-1RF-POS1")
      (footprint "eagle-import:ORESAT-CARD-V1.3-GENERIC-1RF-POS1")
      (libsource (lib "eagle-import") (part "ORESAT-CARD-V1.3-GENERIC-1RF-POS1"))
    )
    (comp (ref "TP58")
      (value "TEST-POINT3X4")
      (footprint "eagle-import:PAD.03X.04")
      (libsource (lib "eagle-import") (part "TEST-POINT3X4"))
    )
    (comp (ref "TP59")
      (value "TEST-POINT3X4")
      (footprint "eagle-import:PAD.03X.04")
      (libsource (lib "eagle-import") (part "TEST-POINT3X4"))
    )
    (comp (ref "TP60")
      (value "TEST-POINT3X4")
      (footprint "eagle-import:PAD.03X.04")
      (libsource (lib "eagle-import") (part "TEST-POINT3X4"))
    )
    (comp (ref "TP61")
      (value "TEST-POINT3X4")
      (footprint "eagle-import:PAD.03X.04")
      (libsource (lib "eagle-import") (part "TEST-POINT3X4"))
    )
    (comp (ref "TP62")
      (value "TEST-POINT3X4")
      (footprint "eagle-import:PAD.03X.04")
      (libsource (lib "eagle-import") (part "TEST-POINT3X4"))
    )
    (comp (ref "TP183")
      (value "TEST-POINT3X4")
      (footprint "eagle-import:PAD.03X.04")
      (libsource (lib "eagle-import") (part "TEST-POINT3X4"))
    )
    (comp (ref "TP184")
      (value "TEST-POINT3X4")
      (footprint "eagle-import:PAD.03X.04")
      (libsource (lib "eagle-import") (part "TEST-POINT3X4"))
    )
    (comp (ref "C2")
      (value "10uF")
      (footprint "eagle-import:.0805-B")
      (libsource (lib "eagle-import") (part "C-EU0805-B"))
    )
    (comp (ref "C3")
      (value "1uF")
      (footprint "eagle-import:.0603-A")
      (libsource (lib "eagle-import") (part "C-EU0603-A"))
    )
    (comp (ref "C5")
      (value "1uF")
      (footprint "eagle-import:.0603-A")
      (libsource (lib "eagle-import") (part "C-EU0603-A"))
    )
    (comp (ref "C6")
      (value "1uF")
      (footprint "eagle-import:.0603-A")
      (libsource (lib "eagle-import") (part "C-EU0603-A"))
    )
    (comp (ref "C8")
      (value "10uF")
      (footprint "eagle-import:.0805-B")
      (libsource (lib "eagle-import") (part "C-EU0805-B"))
    )
    (comp (ref "C9")
      (value "1uF")
      (footprint "eagle-import:.0603-A")
      (libsource (lib "eagle-import") (part "C-EU0603-A"))
    )
    (comp (ref "C10")
      (value "1uF")
      (footprint "eagle-import:.0603-A")
      (libsource (lib "eagle-import") (part "C-EU0603-A"))
    )
    (comp (ref "C11")
      (value "0.1uF")
      (footprint "eagle-import:.0603-A")
      (libsource (lib "eagle-import") (part "C-EU0603-A"))
    )
    (comp (ref "C12")
      (value "1uF")
      (footprint "eagle-import:.0603-A")
      (libsource (lib "eagle-import") (part "C-EU0603-A"))
    )
    (comp (ref "C31")
      (value "0.1uF")
      (footprint "eagle-import:.0603-A")
      (libsource (lib "eagle-import") (part "C-EU0603-A"))
    )
    (comp (ref "C40")
      (value "0.1uF")
      (footprint "eagle-import:.0603-A")
      (libsource (lib "eagle-import") (part "C-EU0603-A"))
    )
    (comp (ref "D2")
      (value "BLUE")
      (footprint "eagle-import:LED-0603")
      (libsource (lib "eagle-import") (part "LED-BLUE0603"))
    )
    (comp (ref "D3")
      (value "BLUE")
      (footprint "eagle-import:LED-0603")
      (libsource (lib "eagle-import") (part "LED-BLUE0603"))
    )
    (comp (ref "D4")
      (value "BLUE")
      (footprint "eagle-import:LED-0603")
      (libsource (lib "eagle-import") (part "LED-BLUE0603"))
    )
    (comp (ref "D5")
      (value "BLUE")
      (footprint "eagle-import:LED-0603")
      (libsource (lib "eagle-import") (part "LED-BLUE0603"))
    )
    (comp (ref "J7")
      (value "DM3BT-DSF-PEJS")
      (footprint "eagle-import:DM3BT-DSF-PEJS")
      (libsource (lib "eagle-import") (part "DM3BT-DSF-PEJS"))
    )
    (comp (ref "JP105")
      (value "JUMPER-SMT_3_1-NC_TRACE_SILK")
      (footprint "eagle-import:SMT-JUMPER_3_1-NC_TRACE_SILK")
      (libsource (lib "eagle-import") (part "JUMPER-SMT_3_1-NC_TRACE_SILK"))
    )
    (comp (ref "JP106")
      (value "JUMPER-SMT_3_1-NC_TRACE_SILK")
      (footprint "eagle-import:SMT-JUMPER_3_1-NC_TRACE_SILK")
      (libsource (lib "eagle-import") (part "JUMPER-SMT_3_1-NC_TRACE_SILK"))
    )
    (comp (ref "JP107")
      (value "JUMPER-SMT_3_1-NC_TRACE_SILK")
      (footprint "eagle-import:SMT-JUMPER_3_1-NC_TRACE_SILK")
      (libsource (lib "eagle-import") (part "JUMPER-SMT_3_1-NC_TRACE_SILK"))
    )
    (comp (ref "JP108")
      (value "JUMPER-SMT_3_1-NC_TRACE_SILK")
      (footprint "eagle-import:SMT-JUMPER_3_1-NC_TRACE_SILK")
      (libsource (lib "eagle-import") (part "JUMPER-SMT_3_1-NC_TRACE_SILK"))
    )
    (comp (ref "JP109")
      (value "JUMPER-SMT_3_1-NC_TRACE_SILK")
      (footprint "eagle-import:SMT-JUMPER_3_1-NC_TRACE_SILK")
      (libsource (lib "eagle-import") (part "JUMPER-SMT_3_1-NC_TRACE_SILK"))
    )
    (comp (ref "R2")
      (value "4.7k")
      (footprint "eagle-import:.0603-A")
      (libsource (lib "eagle-import") (part "R-US_0603-A"))
    )
    (comp (ref "R3")
      (value "4.7k")
      (footprint "eagle-import:.0603-A")
      (libsource (lib "eagle-import") (part "R-US_0603-A"))
    )
    (comp (ref "R4")
      (value "4.7k")
      (footprint "eagle-import:.0603-A")
      (libsource (lib "eagle-import") (part "R-US_0603-A"))
    )
    (comp (ref "R5")
      (value "4.7k")
      (footprint "eagle-import:.0603-A")
      (libsource (lib "eagle-import") (part "R-US_0603-A"))
    )
    (comp (ref "R8")
      (value "10k")
      (footprint "eagle-import:ARRAY_EXBA-M")
      (fields
        (field (name "MFR") "Panasonic Electronic Components")
        (field (name "MPN") "EXB-A10PXXXJ")
        (field (name "MPN_1") "EXB-A10P103J")
      )
      (libsource (lib "eagle-import") (part "EXB-A10P391JC_ARRAY_EXBA-M"))
    )
    (comp (ref "R9")
      (value "10K")
      (footprint "eagle-import:ARRAY_EXBA-M")
      (fields
        (field (name "MFR") "Panasonic Electronic Components")
        (field (name "MPN") "EXB-A10PXXXJ")
        (field (name "MPN_1") "EXB-A10P103J")
      )
      (libsource (lib "eagle-import") (part "EXB-A10P391JC_ARRAY_EXBA-M"))
    )
    (comp (ref "R10")
      (value "10K")
      (footprint "eagle-import:ARRAY_EXBA-M")
      (fields
        (field (name "MFR") "Panasonic Electronic Components")
        (field (name "MPN") "EXB-A10PXXXJ")
        (field (name "DPN") "U7103CT-ND")
        (field (name "MPN_1") "EXB-A10P103J")
      )
      (libsource (lib "eagle-import") (part "EXB-A10P391JC_ARRAY_EXBA-M"))
    )
    (comp (ref "R24")
      (value "100K")
      (footprint "eagle-import:ARRAY_EXBA-M")
      (fields
        (field (name "MFR") "Panasonic Electronic Components")
        (field (name "MPN") "EXB-A10PXXXJ")
        (field (name "MPN_1") "EXB-A10P104J")
      )
      (libsource (lib "eagle-import") (part "EXB-A10P391JC_ARRAY_EXBA-M"))
    )
    (comp (ref "R25")
      (value "100K")
      (footprint "eagle-import:ARRAY_EXBA-M")
      (fields
        (field (name "MFR") "Panasonic Electronic Components")
        (field (name "MPN") "EXB-A10PXXXJ")
        (field (name "MPN_1") "EXB-A10P104J")
      )
      (libsource (lib "eagle-import") (part "EXB-A10P391JC_ARRAY_EXBA-M"))
    )
    (comp (ref "R26")
      (value "100K")
      (footprint "eagle-import:ARRAY_EXBA-M")
      (fields
        (field (name "MFR") "Panasonic Electronic Components")
        (field (name "MPN") "EXB-A10PXXXJ")
        (field (name "MPN_1") "EXB-A10P104J")
      )
      (libsource (lib "eagle-import") (part "EXB-A10P391JC_ARRAY_EXBA-M"))
    )
    (comp (ref "R59")
      (value "DNP")
      (footprint "eagle-import:.0603-A")
      (libsource (lib "eagle-import") (part "R-US_0603-A"))
    )
    (comp (ref "R60")
      (value "DNP")
      (footprint "eagle-import:.0603-A")
      (libsource (lib "eagle-import") (part "R-US_0603-A"))
    )
    (comp (ref "TP11")
      (value "TEST-POINT")
      (footprint "eagle-import:2MM-TEST-POINT")
      (libsource (lib "eagle-import") (part "TEST-POINT"))
    )
    (comp (ref "TP22")
      (value "TEST-POINT3X4")
      (footprint "eagle-import:PAD.03X.04")
      (libsource (lib "eagle-import") (part "TEST-POINT3X4"))
    )
    (comp (ref "TP30")
      (value "TEST-POINT3X4")
      (footprint "eagle-import:PAD.03X.04")
      (libsource (lib "eagle-import") (part "TEST-POINT3X4"))
    )
    (comp (ref "TP35")
      (value "TEST-POINT3X4")
      (footprint "eagle-import:PAD.03X.04")
      (libsource (lib "eagle-import") (part "TEST-POINT3X4"))
    )
    (comp (ref "TP40")
      (value "TEST-POINT3X4")
      (footprint "eagle-import:PAD.03X.04")
      (libsource (lib "eagle-import") (part "TEST-POINT3X4"))
    )
    (comp (ref "TP69")
      (value "TEST-POINT3X4")
      (footprint "eagle-import:PAD.03X.04")
      (libsource (lib "eagle-import") (part "TEST-POINT3X4"))
    )
    (comp (ref "TP100")
      (value "TEST-POINT3X4")
      (footprint "eagle-import:PAD.03X.04")
      (libsource (lib "eagle-import") (part "TEST-POINT3X4"))
    )
    (comp (ref "TP101")
      (value "TEST-POINT3X4")
      (footprint "eagle-import:PAD.03X.04")
      (libsource (lib "eagle-import") (part "TEST-POINT3X4"))
    )
    (comp (ref "TP103")
      (value "TEST-POINT3X4")
      (footprint "eagle-import:PAD.03X.04")
      (libsource (lib "eagle-import") (part "TEST-POINT3X4"))
    )
    (comp (ref "TP104")
      (value "TEST-POINT3X4")
      (footprint "eagle-import:PAD.03X.04")
      (libsource (lib "eagle-import") (part "TEST-POINT3X4"))
    )
    (comp (ref "TP105")
      (value "TEST-POINT3X4")
      (footprint "eagle-import:PAD.03X.04")
      (libsource (lib "eagle-import") (part "TEST-POINT3X4"))
    )
    (comp (ref "TP106")
      (value "TEST-POINT3X4")
      (footprint "eagle-import:PAD.03X.04")
      (libsource (lib "eagle-import") (part "TEST-POINT3X4"))
    )
    (comp (ref "TP107")
      (value "TEST-POINT3X4")
      (footprint "eagle-import:PAD.03X.04")
      (libsource (lib "eagle-import") (part "TEST-POINT3X4"))
    )
    (comp (ref "TP108")
      (value "TEST-POINT3X4")
      (footprint "eagle-import:PAD.03X.04")
      (libsource (lib "eagle-import") (part "TEST-POINT3X4"))
    )
    (comp (ref "TP111")
      (value "TEST-POINT3X4")
      (footprint "eagle-import:PAD.03X.04")
      (libsource (lib "eagle-import") (part "TEST-POINT3X4"))
    )
    (comp (ref "TP114")
      (value "TEST-POINT3X4")
      (footprint "eagle-import:PAD.03X.04")
      (libsource (lib "eagle-import") (part "TEST-POINT3X4"))
    )
    (comp (ref "TP115")
      (value "TEST-POINT3X4")
      (footprint "eagle-import:PAD.03X.04")
      (libsource (lib "eagle-import") (part "TEST-POINT3X4"))
    )
    (comp (ref "TP117")
      (value "TEST-POINT3X4")
      (footprint "eagle-import:PAD.03X.04")
      (libsource (lib "eagle-import") (part "TEST-POINT3X4"))
    )
    (comp (ref "TP118")
      (value "TEST-POINT3X4")
      (footprint "eagle-import:PAD.03X.04")
      (libsource (lib "eagle-import") (part "TEST-POINT3X4"))
    )
    (comp (ref "TP120")
      (value "TEST-POINT3X4")
      (footprint "eagle-import:PAD.03X.04")
      (libsource (lib "eagle-import") (part "TEST-POINT3X4"))
    )
    (comp (ref "TP122")
      (value "TEST-POINT3X4")
      (footprint "eagle-import:PAD.03X.04")
      (libsource (lib "eagle-import") (part "TEST-POINT3X4"))
    )
    (comp (ref "TP123")
      (value "TEST-POINT3X4")
      (footprint "eagle-import:PAD.03X.04")
      (libsource (lib "eagle-import") (part "TEST-POINT3X4"))
    )
    (comp (ref "TP124")
      (value "TEST-POINT3X4")
      (footprint "eagle-import:PAD.03X.04")
      (libsource (lib "eagle-import") (part "TEST-POINT3X4"))
    )
    (comp (ref "TP125")
      (value "TEST-POINT3X4")
      (footprint "eagle-import:PAD.03X.04")
      (libsource (lib "eagle-import") (part "TEST-POINT3X4"))
    )
    (comp (ref "TP126")
      (value "TEST-POINT3X4")
      (footprint "eagle-import:PAD.03X.04")
      (libsource (lib "eagle-import") (part "TEST-POINT3X4"))
    )
    (comp (ref "TP127")
      (value "TEST-POINT3X4")
      (footprint "eagle-import:PAD.03X.04")
      (libsource (lib "eagle-import") (part "TEST-POINT3X4"))
    )
    (comp (ref "TP128")
      (value "TEST-POINT3X4")
      (footprint "eagle-import:PAD.03X.04")
      (libsource (lib "eagle-import") (part "TEST-POINT3X4"))
    )
    (comp (ref "TP131")
      (value "TEST-POINT3X4")
      (footprint "eagle-import:PAD.03X.04")
      (libsource (lib "eagle-import") (part "TEST-POINT3X4"))
    )
    (comp (ref "TP134")
      (value "TEST-POINT3X4")
      (footprint "eagle-import:PAD.03X.04")
      (libsource (lib "eagle-import") (part "TEST-POINT3X4"))
    )
    (comp (ref "TP135")
      (value "TEST-POINT3X4")
      (footprint "eagle-import:PAD.03X.04")
      (libsource (lib "eagle-import") (part "TEST-POINT3X4"))
    )
    (comp (ref "TP137")
      (value "TEST-POINT3X4")
      (footprint "eagle-import:PAD.03X.04")
      (libsource (lib "eagle-import") (part "TEST-POINT3X4"))
    )
    (comp (ref "TP142")
      (value "TEST-POINT3X4")
      (footprint "eagle-import:PAD.03X.04")
      (libsource (lib "eagle-import") (part "TEST-POINT3X4"))
    )
    (comp (ref "TP143")
      (value "TEST-POINT3X4")
      (footprint "eagle-import:PAD.03X.04")
      (libsource (lib "eagle-import") (part "TEST-POINT3X4"))
    )
    (comp (ref "TP146")
      (value "TEST-POINT3X4")
      (footprint "eagle-import:PAD.03X.04")
      (libsource (lib "eagle-import") (part "TEST-POINT3X4"))
    )
    (comp (ref "TP148")
      (value "TEST-POINT3X4")
      (footprint "eagle-import:PAD.03X.04")
      (libsource (lib "eagle-import") (part "TEST-POINT3X4"))
    )
    (comp (ref "TP149")
      (value "TEST-POINT3X4")
      (footprint "eagle-import:PAD.03X.04")
      (libsource (lib "eagle-import") (part "TEST-POINT3X4"))
    )
    (comp (ref "TP152")
      (value "TEST-POINT3X4")
      (footprint "eagle-import:PAD.03X.04")
      (libsource (lib "eagle-import") (part "TEST-POINT3X4"))
    )
    (comp (ref "TP153")
      (value "TEST-POINT3X4")
      (footprint "eagle-import:PAD.03X.04")
      (libsource (lib "eagle-import") (part "TEST-POINT3X4"))
    )
    (comp (ref "TP158")
      (value "TEST-POINT3X4")
      (footprint "eagle-import:PAD.03X.04")
      (libsource (lib "eagle-import") (part "TEST-POINT3X4"))
    )
    (comp (ref "TP159")
      (value "TEST-POINT3X4")
      (footprint "eagle-import:PAD.03X.04")
      (libsource (lib "eagle-import") (part "TEST-POINT3X4"))
    )
    (comp (ref "TP162")
      (value "TEST-POINT3X4")
      (footprint "eagle-import:PAD.03X.04")
      (libsource (lib "eagle-import") (part "TEST-POINT3X4"))
    )
    (comp (ref "TP174")
      (value "TEST-POINT3X4")
      (footprint "eagle-import:PAD.03X.04")
      (libsource (lib "eagle-import") (part "TEST-POINT3X4"))
    )
    (comp (ref "TP177")
      (value "TEST-POINT3X4")
      (footprint "eagle-import:PAD.03X.04")
      (libsource (lib "eagle-import") (part "TEST-POINT3X4"))
    )
    (comp (ref "TP178")
      (value "TEST-POINT3X4")
      (footprint "eagle-import:PAD.03X.04")
      (libsource (lib "eagle-import") (part "TEST-POINT3X4"))
    )
    (comp (ref "TP180")
      (value "TEST-POINT3X4")
      (footprint "eagle-import:PAD.03X.04")
      (libsource (lib "eagle-import") (part "TEST-POINT3X4"))
    )
    (comp (ref "U$1")
      (value "3X1_TH_JUMPER")
      (footprint "eagle-import:3X1")
      (libsource (lib "eagle-import") (part "3X1_TH_JUMPER"))
    )
    (comp (ref "U3")
      (value "THGBMJG7C2LBAU8")
      (footprint "eagle-import:BGA-153(11.5X13)(EMMC-BA)")
      (libsource (lib "eagle-import") (part "EMMC+RESET+5.1-COMPATIBLE-BA"))
    )
    (comp (ref "U11")
      (value "TCAN330")
      (footprint "eagle-import:SOT23-8_TI-DCN")
      (fields (field (name "MPN") "TCAN330GDCNT"))
      (libsource (lib "eagle-import") (part "TCAN330"))
    )
    (comp (ref "U17")
      (value "25AAXX")
      (footprint "eagle-import:SOIC8")
      (fields (field (name "MPN") "25AA02E48T-I/SN"))
      (libsource (lib "eagle-import") (part "25AAXX"))
    )
    (comp (ref "C13")
      (value "22uF")
      (footprint "eagle-import:C1210")
      (libsource (lib "eagle-import") (part "C-EUC1210"))
    )
    (comp (ref "C14")
      (value "22uF")
      (footprint "eagle-import:C1210")
      (libsource (lib "eagle-import") (part "C-EUC1210"))
    )
    (comp (ref "C18")
      (value "0.1uF")
      (footprint "eagle-import:.0603-A")
      (libsource (lib "eagle-import") (part "C-EU0603-A"))
    )
    (comp (ref "C41")
      (value "0.1uF")
      (footprint "eagle-import:.0603-A")
      (libsource (lib "eagle-import") (part "C-EU0603-A"))
    )
    (comp (ref "D1")
      (value "GREEN")
      (footprint "eagle-import:LED-0603")
      (description "Green 573nm LED Indication - Discrete 2V 0603 (1608 Metric)")
      (fields
        (field (name "DIGI-KEY_PART_NUMBER") "732-12017-1-ND")
        (field (name "MANUFACTURER") "Würth Elektronik")
      )
      (libsource (lib "eagle-import") (part "LED-GREEN0603"))
    )
    (comp (ref "JP101")
      (value "JUMPER-SMT_2_NC_TRACE_SILK")
      (footprint "eagle-import:SMT-JUMPER_2_NC_TRACE_SILK")
      (libsource (lib "eagle-import") (part "JUMPER-SMT_2_NC_TRACE_SILK"))
    )
    (comp (ref "JP104")
      (value "JUMPER-SMT_2_NC_TRACE_SILK")
      (footprint "eagle-import:SMT-JUMPER_2_NC_TRACE_SILK")
      (libsource (lib "eagle-import") (part "JUMPER-SMT_2_NC_TRACE_SILK"))
    )
    (comp (ref "Q1")
      (value "MMBT2907")
      (footprint "eagle-import:SOT23-BEC")
      (fields (field (name "MPN") "MMBT2907A-7-F"))
      (libsource (lib "eagle-import") (part "MMBT2907SMD"))
    )
    (comp (ref "R1")
      (value "4.7k")
      (footprint "eagle-import:.0603-A")
      (libsource (lib "eagle-import") (part "R-US_0603-A"))
    )
    (comp (ref "R15")
      (value "10k")
      (footprint "eagle-import:.0603-A")
      (libsource (lib "eagle-import") (part "R-US_0603-A"))
    )
    (comp (ref "R23")
      (value "499")
      (footprint "eagle-import:.0603-A")
      (libsource (lib "eagle-import") (part "R-US_0603-A"))
    )
    (comp (ref "R28")
      (value "10k")
      (footprint "eagle-import:.0603-A")
      (libsource (lib "eagle-import") (part "R-US_0603-A"))
    )
    (comp (ref "R31")
      (value "40.2K")
      (footprint "eagle-import:.0603-A")
      (libsource (lib "eagle-import") (part "R-US_0603-A"))
    )
    (comp (ref "R73")
      (value "100")
      (footprint "eagle-import:.0603-A")
      (libsource (lib "eagle-import") (part "R-US_0603-A"))
    )
    (comp (ref "R74")
      (value "100")
      (footprint "eagle-import:.0603-A")
      (libsource (lib "eagle-import") (part "R-US_0603-A"))
    )
    (comp (ref "R75")
      (value "100")
      (footprint "eagle-import:.0603-A")
      (libsource (lib "eagle-import") (part "R-US_0603-A"))
    )
    (comp (ref "TP2")
      (value "TEST-POINT3X4")
      (footprint "eagle-import:PAD.03X.04")
      (libsource (lib "eagle-import") (part "TEST-POINT3X4"))
    )
    (comp (ref "TP3")
      (value "TEST-POINT3X4")
      (footprint "eagle-import:PAD.03X.04")
      (libsource (lib "eagle-import") (part "TEST-POINT3X4"))
    )
    (comp (ref "TP4")
      (value "TEST-POINT3X4")
      (footprint "eagle-import:PAD.03X.04")
      (libsource (lib "eagle-import") (part "TEST-POINT3X4"))
    )
    (comp (ref "TP9")
      (value "TEST-POINT3X4")
      (footprint "eagle-import:PAD.03X.04")
      (libsource (lib "eagle-import") (part "TEST-POINT3X4"))
    )
    (comp (ref "TP14")
      (value "TEST-POINT3X4")
      (footprint "eagle-import:PAD.03X.04")
      (libsource (lib "eagle-import") (part "TEST-POINT3X4"))
    )
    (comp (ref "TP25")
      (value "TEST-POINT3X4")
      (footprint "eagle-import:PAD.03X.04")
      (libsource (lib "eagle-import") (part "TEST-POINT3X4"))
    )
    (comp (ref "TP102")
      (value "TEST-POINT3X4")
      (footprint "eagle-import:PAD.03X.04")
      (libsource (lib "eagle-import") (part "TEST-POINT3X4"))
    )
    (comp (ref "TP109")
      (value "TEST-POINT3X4")
      (footprint "eagle-import:PAD.03X.04")
      (libsource (lib "eagle-import") (part "TEST-POINT3X4"))
    )
    (comp (ref "TP110")
      (value "TEST-POINT3X4")
      (footprint "eagle-import:PAD.03X.04")
      (libsource (lib "eagle-import") (part "TEST-POINT3X4"))
    )
    (comp (ref "TP112")
      (value "TEST-POINT3X4")
      (footprint "eagle-import:PAD.03X.04")
      (libsource (lib "eagle-import") (part "TEST-POINT3X4"))
    )
    (comp (ref "TP121")
      (value "TEST-POINT3X4")
      (footprint "eagle-import:PAD.03X.04")
      (libsource (lib "eagle-import") (part "TEST-POINT3X4"))
    )
    (comp (ref "TP129")
      (value "TEST-POINT3X4")
      (footprint "eagle-import:PAD.03X.04")
      (libsource (lib "eagle-import") (part "TEST-POINT3X4"))
    )
    (comp (ref "TP130")
      (value "TEST-POINT3X4")
      (footprint "eagle-import:PAD.03X.04")
      (libsource (lib "eagle-import") (part "TEST-POINT3X4"))
    )
    (comp (ref "TP132")
      (value "TEST-POINT3X4")
      (footprint "eagle-import:PAD.03X.04")
      (libsource (lib "eagle-import") (part "TEST-POINT3X4"))
    )
    (comp (ref "TP136")
      (value "TEST-POINT3X4")
      (footprint "eagle-import:PAD.03X.04")
      (libsource (lib "eagle-import") (part "TEST-POINT3X4"))
    )
    (comp (ref "TP140")
      (value "TEST-POINT3X4")
      (footprint "eagle-import:PAD.03X.04")
      (libsource (lib "eagle-import") (part "TEST-POINT3X4"))
    )
    (comp (ref "TP145")
      (value "TEST-POINT3X4")
      (footprint "eagle-import:PAD.03X.04")
      (libsource (lib "eagle-import") (part "TEST-POINT3X4"))
    )
    (comp (ref "TP150")
      (value "TEST-POINT3X4")
      (footprint "eagle-import:PAD.03X.04")
      (libsource (lib "eagle-import") (part "TEST-POINT3X4"))
    )
    (comp (ref "TP151")
      (value "TEST-POINT3X4")
      (footprint "eagle-import:PAD.03X.04")
      (libsource (lib "eagle-import") (part "TEST-POINT3X4"))
    )
    (comp (ref "TP154")
      (value "TEST-POINT3X4")
      (footprint "eagle-import:PAD.03X.04")
      (libsource (lib "eagle-import") (part "TEST-POINT3X4"))
    )
    (comp (ref "TP155")
      (value "TEST-POINT3X4")
      (footprint "eagle-import:PAD.03X.04")
      (libsource (lib "eagle-import") (part "TEST-POINT3X4"))
    )
    (comp (ref "TP156")
      (value "TEST-POINT3X4")
      (footprint "eagle-import:PAD.03X.04")
      (libsource (lib "eagle-import") (part "TEST-POINT3X4"))
    )
    (comp (ref "TP157")
      (value "TEST-POINT3X4")
      (footprint "eagle-import:PAD.03X.04")
      (libsource (lib "eagle-import") (part "TEST-POINT3X4"))
    )
    (comp (ref "TP160")
      (value "TEST-POINT3X4")
      (footprint "eagle-import:PAD.03X.04")
      (libsource (lib "eagle-import") (part "TEST-POINT3X4"))
    )
    (comp (ref "TP161")
      (value "TEST-POINT3X4")
      (footprint "eagle-import:PAD.03X.04")
      (libsource (lib "eagle-import") (part "TEST-POINT3X4"))
    )
    (comp (ref "TP164")
      (value "TEST-POINT3X4")
      (footprint "eagle-import:PAD.03X.04")
      (libsource (lib "eagle-import") (part "TEST-POINT3X4"))
    )
    (comp (ref "TP165")
      (value "TEST-POINT3X4")
      (footprint "eagle-import:PAD.03X.04")
      (libsource (lib "eagle-import") (part "TEST-POINT3X4"))
    )
    (comp (ref "TP166")
      (value "TEST-POINT3X4")
      (footprint "eagle-import:PAD.03X.04")
      (libsource (lib "eagle-import") (part "TEST-POINT3X4"))
    )
    (comp (ref "TP167")
      (value "TEST-POINT3X4")
      (footprint "eagle-import:PAD.03X.04")
      (libsource (lib "eagle-import") (part "TEST-POINT3X4"))
    )
    (comp (ref "TP172")
      (value "TEST-POINT3X4")
      (footprint "eagle-import:PAD.03X.04")
      (libsource (lib "eagle-import") (part "TEST-POINT3X4"))
    )
    (comp (ref "TP173")
      (value "TEST-POINT3X4")
      (footprint "eagle-import:PAD.03X.04")
      (libsource (lib "eagle-import") (part "TEST-POINT3X4"))
    )
    (comp (ref "U4")
      (value "SN74LVC1G07DCK")
      (footprint "eagle-import:C70(TI-DCK)")
      (fields (field (name "MPN") "SN74LVC1G07DCKR"))
      (libsource (lib "eagle-import") (part "SN74LVC1G07DCK"))
    )
    (comp (ref "U10")
      (value "TLVH431")
      (footprint "eagle-import:SOT23-3")
      (fields (field (name "MPN") "TLVH431BQDBZRQ1"))
      (libsource (lib "eagle-import") (part "TLVH431"))
    )
    (comp (ref "U18")
      (value "RCLAMP0504FB")
      (footprint "eagle-import:SC70-6")
      (fields (field (name "MPN") "RCLAMP0504FBTCT"))
      (libsource (lib "eagle-import") (part "RCLAMP0504FB"))
    )
    (comp (ref "C16")
      (value "10uF")
      (footprint "eagle-import:.0805-B")
      (libsource (lib "eagle-import") (part "C-EU0805-B"))
    )
    (comp (ref "C17")
      (value "1uF")
      (footprint "eagle-import:.0603-A")
      (libsource (lib "eagle-import") (part "C-EU0603-A"))
    )
    (comp (ref "C20")
      (value "22uF")
      (footprint "eagle-import:C1210")
      (fields (field (name "MFG") "Murata") (field (name "MPN") "GCJ32ER71C226KE01L"))
      (libsource (lib "eagle-import") (part "C-EUC1210"))
    )
    (comp (ref "C32")
      (value "1uF")
      (footprint "eagle-import:.0805-B-NOSILK")
      (libsource (lib "eagle-import") (part "C-EU0805-B-NOSILK"))
    )
    (comp (ref "C33")
      (value "1uF")
      (footprint "eagle-import:.0603-A")
      (fields (field (name "MFR") "Samsung") (field (name "MPN") "CL05B104KO5NNNC"))
      (libsource (lib "eagle-import") (part "C-EU0603-A"))
    )
    (comp (ref "C34")
      (value "1uF")
      (footprint "eagle-import:.0603-A")
      (libsource (lib "eagle-import") (part "C-EU0603-A"))
    )
    (comp (ref "C35")
      (value "1uF")
      (footprint "eagle-import:.0805-B-NOSILK")
      (libsource (lib "eagle-import") (part "C-EU0805-B-NOSILK"))
    )
    (comp (ref "C36")
      (value "22uF")
      (footprint "eagle-import:C1210")
      (libsource (lib "eagle-import") (part "C-EUC1210"))
    )
    (comp (ref "C37")
      (value "1uF")
      (footprint "eagle-import:.0603-A")
      (libsource (lib "eagle-import") (part "C-EU0603-A"))
    )
    (comp (ref "C38")
      (value "10uF")
      (footprint "eagle-import:.0805-B")
      (libsource (lib "eagle-import") (part "C-EU0805-B"))
    )
    (comp (ref "C39")
      (value "0.1uF")
      (footprint "eagle-import:.0603-A")
      (libsource (lib "eagle-import") (part "C-EU0603-A"))
    )
    (comp (ref "C44")
      (value "10uF")
      (footprint "eagle-import:.0805-B")
      (libsource (lib "eagle-import") (part "C-EU0805-B"))
    )
    (comp (ref "D6")
      (value "GREEN")
      (footprint "eagle-import:LED-0603")
      (description "Green 573nm LED Indication - Discrete 2V 0603 (1608 Metric)")
      (fields
        (field (name "DIGI-KEY_PART_NUMBER") "732-12017-1-ND")
        (field (name "MANUFACTURER") "Würth Elektronik")
      )
      (libsource (lib "eagle-import") (part "LED-GREEN0603"))
    )
    (comp (ref "D7")
      (value "GREEN")
      (footprint "eagle-import:LED-0603")
      (description "Green 573nm LED Indication - Discrete 2V 0603 (1608 Metric)")
      (fields
        (field (name "DIGI-KEY_PART_NUMBER") "732-12017-1-ND")
        (field (name "MANUFACTURER") "Würth Elektronik")
      )
      (libsource (lib "eagle-import") (part "LED-GREEN0603"))
    )
    (comp (ref "D8")
      (value "GREEN")
      (footprint "eagle-import:LED-0603")
      (description "Green 573nm LED Indication - Discrete 2V 0603 (1608 Metric)")
      (fields
        (field (name "DIGI-KEY_PART_NUMBER") "732-12017-1-ND")
        (field (name "MANUFACTURER") "Würth Elektronik")
      )
      (libsource (lib "eagle-import") (part "LED-GREEN0603"))
    )
    (comp (ref "D9")
      (value "GREEN")
      (footprint "eagle-import:LED-0603")
      (description "Green 573nm LED Indication - Discrete 2V 0603 (1608 Metric)")
      (fields
        (field (name "DIGI-KEY_PART_NUMBER") "732-12017-1-ND")
        (field (name "MANUFACTURER") "Würth Elektronik")
      )
      (libsource (lib "eagle-import") (part "LED-GREEN0603"))
    )
    (comp (ref "L1")
      (value "6.8u")
      (footprint "eagle-import:ECS-MPI4040")
      (fields (field (name "MPN") "ECS-MPI4040R4-6R8-R"))
      (libsource (lib "eagle-import") (part "L-ECS-MPI4040"))
    )
    (comp (ref "L2")
      (value "6.8u")
      (footprint "eagle-import:ECS-MPI4040")
      (fields (field (name "MPN") "ECS-MPI4040R4-6R8-R"))
      (libsource (lib "eagle-import") (part "L-ECS-MPI4040"))
    )
    (comp (ref "Q2")
      (value "PMV45EN")
      (footprint "eagle-import:SOT23")
      (fields (field (name "MPN") "PMV45EN2R"))
      (libsource (lib "eagle-import") (part "PMV45EN"))
    )
    (comp (ref "Q3")
      (value "DMP2240UDM")
      (footprint "eagle-import:SOT23-6")
      (fields (field (name "MPN") "DMP2240UDM-7"))
      (libsource (lib "eagle-import") (part "Q-MOSFET-PCH-dual-SOT23-6_MOSFET-PCH-SOT23-6"))
    )
    (comp (ref "Q4")
      (value "PMV45EN")
      (footprint "eagle-import:SOT23")
      (fields (field (name "MPN") "PMV45EN2R"))
      (libsource (lib "eagle-import") (part "PMV45EN"))
    )
    (comp (ref "Q5")
      (value "MOSFET-PCH-SOT23-6")
      (footprint "eagle-import:SOT23-6")
      (fields (field (name "MPN") "DMP3050LVT-7") (field (name "MPN_1") "DMP3050LVT-7"))
      (libsource (lib "eagle-import") (part "MOSFET-PCH-SOT23-6"))
    )
    (comp (ref "Q6")
      (value "MOSFET-PCH-SOT23-6")
      (footprint "eagle-import:SOT23-6")
      (fields (field (name "MPN") "DMP3050LVT-7") (field (name "MPN_1") "DMP3050LVT-7"))
      (libsource (lib "eagle-import") (part "MOSFET-PCH-SOT23-6"))
    )
    (comp (ref "R11")
      (value "10k")
      (footprint "eagle-import:.0603-A")
      (libsource (lib "eagle-import") (part "R-US_0603-A"))
    )
    (comp (ref "R12")
      (value "10k")
      (footprint "eagle-import:.0603-A")
      (libsource (lib "eagle-import") (part "R-US_0603-A"))
    )
    (comp (ref "R14")
      (value "NP")
      (footprint "eagle-import:.0603-A")
      (fields (field (name "MFR") "Samsung") (field (name "MPN") "RC1005F6653CS"))
      (libsource (lib "eagle-import") (part "R-US_0603-A"))
    )
    (comp (ref "R32")
      (value "10k")
      (footprint "eagle-import:.0603-A")
      (libsource (lib "eagle-import") (part "R-US_0603-A"))
    )
    (comp (ref "R33")
      (value "100k")
      (footprint "eagle-import:.0603-A")
      (fields (field (name "MFR") "Samsung") (field (name "MPN") "RC1005F6653CS"))
      (libsource (lib "eagle-import") (part "R-US_0603-A"))
    )
    (comp (ref "R34")
      (value "10k")
      (footprint "eagle-import:.0603-A")
      (libsource (lib "eagle-import") (part "R-US_0603-A"))
    )
    (comp (ref "R35")
      (value "665k")
      (footprint "eagle-import:.0603-A")
      (libsource (lib "eagle-import") (part "R-US_0603-A"))
    )
    (comp (ref "R36")
      (value "1M")
      (footprint "eagle-import:.0603-A")
      (libsource (lib "eagle-import") (part "R-US_0603-A"))
    )
    (comp (ref "R37")
      (value "330k")
      (footprint "eagle-import:.0603-A")
      (libsource (lib "eagle-import") (part "R-US_0603-A"))
    )
    (comp (ref "R38")
      (value "10k")
      (footprint "eagle-import:.0603-A")
      (fields (field (name "MFR") "Samsung") (field (name "MPN") "RC1005F6653CS"))
      (libsource (lib "eagle-import") (part "R-US_0603-A"))
    )
    (comp (ref "R39")
      (value "10k")
      (footprint "eagle-import:.0603-A")
      (libsource (lib "eagle-import") (part "R-US_0603-A"))
    )
    (comp (ref "R40")
      (value "NP")
      (footprint "eagle-import:.0603-A")
      (fields (field (name "MFR") "Samsung") (field (name "MPN") "RC1005F6653CS"))
      (libsource (lib "eagle-import") (part "R-US_0603-A"))
    )
    (comp (ref "R41")
      (value "100")
      (footprint "eagle-import:.0603-A")
      (libsource (lib "eagle-import") (part "R-US_0603-A"))
    )
    (comp (ref "R42")
      (value "NP")
      (footprint "eagle-import:.0603-A")
      (fields (field (name "MFR") "Samsung") (field (name "MPN") "RC1005F6653CS"))
      (libsource (lib "eagle-import") (part "R-US_0603-A"))
    )
    (comp (ref "R43")
      (value "665k")
      (footprint "eagle-import:.0603-A")
      (libsource (lib "eagle-import") (part "R-US_0603-A"))
    )
    (comp (ref "R44")
      (value "1M")
      (footprint "eagle-import:.0603-A")
      (libsource (lib "eagle-import") (part "R-US_0603-A"))
    )
    (comp (ref "R45")
      (value "330k")
      (footprint "eagle-import:.0603-A")
      (libsource (lib "eagle-import") (part "R-US_0603-A"))
    )
    (comp (ref "R46")
      (value "10k")
      (footprint "eagle-import:.0603-A")
      (libsource (lib "eagle-import") (part "R-US_0603-A"))
    )
    (comp (ref "R47")
      (value "0")
      (footprint "eagle-import:.0603-A")
      (libsource (lib "eagle-import") (part "R-US_0603-A"))
    )
    (comp (ref "R48")
      (value "100")
      (footprint "eagle-import:.0603-A")
      (libsource (lib "eagle-import") (part "R-US_0603-A"))
    )
    (comp (ref "R49")
      (value "4.7k")
      (footprint "eagle-import:.0603-A")
      (libsource (lib "eagle-import") (part "R-US_0603-A"))
    )
    (comp (ref "R50")
      (value "0")
      (footprint "eagle-import:.0603-A")
      (libsource (lib "eagle-import") (part "R-US_0603-A"))
    )
    (comp (ref "R51")
      (value "4.7k")
      (footprint "eagle-import:.0603-A")
      (fields (field (name "MFR") "Samsung") (field (name "MPN") "RC1005F6653CS"))
      (libsource (lib "eagle-import") (part "R-US_0603-A"))
    )
    (comp (ref "R52")
      (value "10k")
      (footprint "eagle-import:.0603-A")
      (libsource (lib "eagle-import") (part "R-US_0603-A"))
    )
    (comp (ref "R53")
      (value "NP")
      (footprint "eagle-import:.0603-A")
      (fields (field (name "MFR") "Samsung") (field (name "MPN") "RC1005F6653CS"))
      (libsource (lib "eagle-import") (part "R-US_0603-A"))
    )
    (comp (ref "R54")
      (value "10k")
      (footprint "eagle-import:.0603-A")
      (fields (field (name "MFR") "Samsung") (field (name "MPN") "RC1005F6653CS"))
      (libsource (lib "eagle-import") (part "R-US_0603-A"))
    )
    (comp (ref "R55")
      (value "10k")
      (footprint "eagle-import:.0603-A")
      (fields (field (name "MFR") "Samsung") (field (name "MPN") "RC1005F6653CS"))
      (libsource (lib "eagle-import") (part "R-US_0603-A"))
    )
    (comp (ref "R56")
      (value "NP")
      (footprint "eagle-import:.0603-A")
      (fields (field (name "MFR") "Samsung") (field (name "MPN") "RC1005F6653CS"))
      (libsource (lib "eagle-import") (part "R-US_0603-A"))
    )
    (comp (ref "R57")
      (value "10k")
      (footprint "eagle-import:.0603-A")
      (fields (field (name "MFR") "Samsung") (field (name "MPN") "RC1005F6653CS"))
      (libsource (lib "eagle-import") (part "R-US_0603-A"))
    )
    (comp (ref "R58")
      (value "NP")
      (footprint "eagle-import:.0603-A")
      (fields (field (name "MFR") "Samsung") (field (name "MPN") "RC1005F6653CS"))
      (libsource (lib "eagle-import") (part "R-US_0603-A"))
    )
    (comp (ref "R61")
      (value "10k")
      (footprint "eagle-import:.0603-A")
      (libsource (lib "eagle-import") (part "R-US_0603-A"))
    )
    (comp (ref "R62")
      (value "10k")
      (footprint "eagle-import:.0603-A")
      (libsource (lib "eagle-import") (part "R-US_0603-A"))
    )
    (comp (ref "R63")
      (value "100m")
      (footprint "eagle-import:R1206")
      (libsource (lib "eagle-import") (part "rcl_334_R-US_R1206"))
    )
    (comp (ref "R64")
      (value "10k")
      (footprint "eagle-import:.0603-A")
      (libsource (lib "eagle-import") (part "R-US_0603-A"))
    )
    (comp (ref "R65")
      (value "NP")
      (footprint "eagle-import:.0603-A")
      (fields (field (name "MFR") "Samsung") (field (name "MPN") "RC1005F6653CS"))
      (libsource (lib "eagle-import") (part "R-US_0603-A"))
    )
    (comp (ref "R66")
      (value "NP")
      (footprint "eagle-import:.0603-A")
      (fields (field (name "MFR") "Samsung") (field (name "MPN") "RC1005F6653CS"))
      (libsource (lib "eagle-import") (part "R-US_0603-A"))
    )
    (comp (ref "R67")
      (value "NP")
      (footprint "eagle-import:.0603-A")
      (fields (field (name "MFR") "Samsung") (field (name "MPN") "RC1005F6653CS"))
      (libsource (lib "eagle-import") (part "R-US_0603-A"))
    )
    (comp (ref "R68")
      (value "NP")
      (footprint "eagle-import:.0603-A")
      (fields (field (name "MFR") "Samsung") (field (name "MPN") "RC1005F6653CS"))
      (libsource (lib "eagle-import") (part "R-US_0603-A"))
    )
    (comp (ref "R69")
      (value "NP")
      (footprint "eagle-import:.0603-A")
      (fields (field (name "MFR") "Samsung") (field (name "MPN") "RC1005F6653CS"))
      (libsource (lib "eagle-import") (part "R-US_0603-A"))
    )
    (comp (ref "R70")
      (value "NP")
      (footprint "eagle-import:.0603-A")
      (fields (field (name "MFR") "Samsung") (field (name "MPN") "RC1005F6653CS"))
      (libsource (lib "eagle-import") (part "R-US_0603-A"))
    )
    (comp (ref "R71")
      (value "100")
      (footprint "eagle-import:.0603-A")
      (libsource (lib "eagle-import") (part "R-US_0603-A"))
    )
    (comp (ref "R72")
      (value "10k")
      (footprint "eagle-import:.0603-A")
      (libsource (lib "eagle-import") (part "R-US_0603-A"))
    )
    (comp (ref "TP5")
      (value "TEST-POINT")
      (footprint "eagle-import:2MM-TEST-POINT")
      (libsource (lib "eagle-import") (part "TEST-POINT"))
    )
    (comp (ref "TP6")
      (value "TEST-POINT")
      (footprint "eagle-import:2MM-TEST-POINT")
      (libsource (lib "eagle-import") (part "TEST-POINT"))
    )
    (comp (ref "TP7")
      (value "TEST-POINT")
      (footprint "eagle-import:2MM-TEST-POINT")
      (libsource (lib "eagle-import") (part "TEST-POINT"))
    )
    (comp (ref "TP41")
      (value "TEST-POINT")
      (footprint "eagle-import:2MM-TEST-POINT")
      (libsource (lib "eagle-import") (part "TEST-POINT"))
    )
    (comp (ref "TP42")
      (value "TEST-POINT")
      (footprint "eagle-import:2MM-TEST-POINT")
      (libsource (lib "eagle-import") (part "TEST-POINT"))
    )
    (comp (ref "TP43")
      (value "TEST-POINT")
      (footprint "eagle-import:2MM-TEST-POINT")
      (libsource (lib "eagle-import") (part "TEST-POINT"))
    )
    (comp (ref "TP44")
      (value "TEST-POINT")
      (footprint "eagle-import:2MM-TEST-POINT")
      (libsource (lib "eagle-import") (part "TEST-POINT"))
    )
    (comp (ref "TP45")
      (value "TEST-POINT")
      (footprint "eagle-import:2MM-TEST-POINT")
      (libsource (lib "eagle-import") (part "TEST-POINT"))
    )
    (comp (ref "TP46")
      (value "TEST-POINT")
      (footprint "eagle-import:2MM-TEST-POINT")
      (libsource (lib "eagle-import") (part "TEST-POINT"))
    )
    (comp (ref "TP47")
      (value "TEST-POINT")
      (footprint "eagle-import:2MM-TEST-POINT")
      (libsource (lib "eagle-import") (part "TEST-POINT"))
    )
    (comp (ref "TP48")
      (value "TEST-POINT")
      (footprint "eagle-import:2MM-TEST-POINT")
      (libsource (lib "eagle-import") (part "TEST-POINT"))
    )
    (comp (ref "TP49")
      (value "TEST-POINT")
      (footprint "eagle-import:2MM-TEST-POINT")
      (libsource (lib "eagle-import") (part "TEST-POINT"))
    )
    (comp (ref "TP50")
      (value "TEST-POINT")
      (footprint "eagle-import:2MM-TEST-POINT")
      (libsource (lib "eagle-import") (part "TEST-POINT"))
    )
    (comp (ref "TP51")
      (value "TEST-POINT")
      (footprint "eagle-import:2MM-TEST-POINT")
      (libsource (lib "eagle-import") (part "TEST-POINT"))
    )
    (comp (ref "TP52")
      (value "TEST-POINT")
      (footprint "eagle-import:2MM-TEST-POINT")
      (libsource (lib "eagle-import") (part "TEST-POINT"))
    )
    (comp (ref "TP53")
      (value "TEST-POINT")
      (footprint "eagle-import:2MM-TEST-POINT")
      (libsource (lib "eagle-import") (part "TEST-POINT"))
    )
    (comp (ref "TP54")
      (value "TEST-POINT")
      (footprint "eagle-import:2MM-TEST-POINT")
      (libsource (lib "eagle-import") (part "TEST-POINT"))
    )
    (comp (ref "TP55")
      (value "TEST-POINT")
      (footprint "eagle-import:2MM-TEST-POINT")
      (libsource (lib "eagle-import") (part "TEST-POINT"))
    )
    (comp (ref "TP56")
      (value "TEST-POINT")
      (footprint "eagle-import:2MM-TEST-POINT")
      (libsource (lib "eagle-import") (part "TEST-POINT"))
    )
    (comp (ref "TP57")
      (value "TEST-POINT")
      (footprint "eagle-import:2MM-TEST-POINT")
      (libsource (lib "eagle-import") (part "TEST-POINT"))
    )
    (comp (ref "TP63")
      (value "TEST-POINT")
      (footprint "eagle-import:2MM-TEST-POINT")
      (libsource (lib "eagle-import") (part "TEST-POINT"))
    )
    (comp (ref "TP64")
      (value "TEST-POINT")
      (footprint "eagle-import:2MM-TEST-POINT")
      (libsource (lib "eagle-import") (part "TEST-POINT"))
    )
    (comp (ref "TP65")
      (value "TEST-POINT")
      (footprint "eagle-import:2MM-TEST-POINT")
      (libsource (lib "eagle-import") (part "TEST-POINT"))
    )
    (comp (ref "TP66")
      (value "TEST-POINT")
      (footprint "eagle-import:2MM-TEST-POINT")
      (libsource (lib "eagle-import") (part "TEST-POINT"))
    )
    (comp (ref "TP67")
      (value "TEST-POINT")
      (footprint "eagle-import:2MM-TEST-POINT")
      (libsource (lib "eagle-import") (part "TEST-POINT"))
    )
    (comp (ref "TP68")
      (value "TEST-POINT")
      (footprint "eagle-import:2MM-TEST-POINT")
      (libsource (lib "eagle-import") (part "TEST-POINT"))
    )
    (comp (ref "U5")
      (value "TPS62112")
      (footprint "eagle-import:S-PVQFN-16")
      (fields (field (name "MPN") "TPS62112RSAR"))
      (libsource (lib "eagle-import") (part "TPS6211X"))
    )
    (comp (ref "U12")
      (value "MIC842LYC5")
      (footprint "eagle-import:SC70-5")
      (libsource (lib "eagle-import") (part "MIC842LYC5"))
    )
    (comp (ref "U13")
      (value "MIC842LYC5")
      (footprint "eagle-import:SC70-5")
      (libsource (lib "eagle-import") (part "MIC842LYC5"))
    )
    (comp (ref "U14")
      (value "MAX4211FETE")
      (footprint "eagle-import:QFN65P400X400X80-17T210")
      (fields (field (name "MPN") "MAX4211FETE+"))
      (libsource (lib "eagle-import") (part "MAX4211"))
    )
    (comp (ref "U15")
      (value "TPS62112")
      (footprint "eagle-import:S-PVQFN-16")
      (fields (field (name "MPN") "TPS62112RSAR"))
      (libsource (lib "eagle-import") (part "TPS6211X"))
    )
    (comp (ref "U16")
      (value "MAX7310ATE")
      (footprint "eagle-import:QFN65P400X400X80-17T210")
      (fields
        (field (name "MPN") "MAX7310ATE+")
        (field (name "MFR") "Maxim")
        (field (name "MPN_1") "MAX7310ATE")
      )
      (libsource (lib "eagle-import") (part "MAX7310"))
    )
    (comp (ref "C15")
      (value "100n")
      (footprint "eagle-import:.0603-A")
      (libsource (lib "eagle-import") (part "C-EU0603-A"))
    )
    (comp (ref "C21")
      (value "100n")
      (footprint "eagle-import:.0603-A")
      (libsource (lib "eagle-import") (part "C-EU0603-A"))
    )
    (comp (ref "C23")
      (value "0.1u")
      (footprint "eagle-import:.0603-A")
      (libsource (lib "eagle-import") (part "C-EU0603-A"))
    )
    (comp (ref "C43")
      (value "100nF")
      (footprint "eagle-import:.0402-B-NOSILK")
      (description "CAP CER 0.1UF 16V X7R 0402")
      (fields (field (name "MFR") "TDK") (field (name "MPN") "CGA2B1X7R1C104K050BC"))
      (libsource (lib "eagle-import") (part "C-EU0402-B-NOSILK"))
    )
    (comp (ref "C45")
      (value "100nF")
      (footprint "eagle-import:.0402-B-NOSILK")
      (description "CAP CER 0.1UF 16V X7R 0402")
      (fields (field (name "MFR") "TDK") (field (name "MPN") "CGA2B1X7R1C104K050BC"))
      (libsource (lib "eagle-import") (part "C-EU0402-B-NOSILK"))
    )
    (comp (ref "C46")
      (value "100nF")
      (footprint "eagle-import:.0402-B-NOSILK")
      (description "CAP CER 0.1UF 16V X7R 0402")
      (fields (field (name "MFR") "TDK") (field (name "MPN") "CGA2B1X7R1C104K050BC"))
      (libsource (lib "eagle-import") (part "C-EU0402-B-NOSILK"))
    )
    (comp (ref "C47")
      (value "100nF")
      (footprint "eagle-import:.0402-C-NOSILK")
      (description "CAP CER 0.1UF 16V X7R 0402")
      (fields (field (name "MFR") "TDK") (field (name "MPN") "CGA2B1X7R1C104K050BC"))
      (libsource (lib "eagle-import") (part "C-EU0402-C-NOSILK"))
    )
    (comp (ref "C48")
      (value "1000pF")
      (footprint "eagle-import:.0402-B-NOSILK")
      (description "CAP CER 1000PF 50V NP0 0402")
      (fields (field (name "MFR") "TDK") (field (name "MPN") "CGA2B2NP01H102J050BA"))
      (libsource (lib "eagle-import") (part "C-EU0402-B-NOSILK"))
    )
    (comp (ref "C49")
      (value "100pF")
      (footprint "eagle-import:.0402-C-NOSILK")
      (description "CAP CER 100PF 50V C0G/NP0 0603")
      (fields (field (name "MFR") "Murata") (field (name "MPN") "GCM1885C1H101JA16D "))
      (libsource (lib "eagle-import") (part "C-EU0402-C-NOSILK"))
    )
    (comp (ref "C50")
      (value "3.0pF")
      (footprint "eagle-import:.0402-C-NOSILK")
      (description "CAP CER 3PF 50V NP0 0402")
      (fields (field (name "MFR") "AVX") (field (name "MPN") "04025U3R0BAT2A"))
      (libsource (lib "eagle-import") (part "C-EU0402-C-NOSILK"))
    )
    (comp (ref "C51")
      (value "1.1pF")
      (footprint "eagle-import:.0402-C-NOSILK")
      (description "50V 1.1pF .02pFTol ThinFilm 0402")
      (fields (field (name "MFR") "AVX") (field (name "MPN") "04025J1R1PBSTR\\500"))
      (libsource (lib "eagle-import") (part "C-EU0402-C-NOSILK"))
    )
    (comp (ref "C52")
      (value "1.6pF")
      (footprint "eagle-import:.0402-C-NOSILK")
      (description "CAP CER 1.6PF 50V NP0 0402")
      (fields (field (name "MFR") "AVX") (field (name "MPN") "04025U1R6BAT2A"))
      (libsource (lib "eagle-import") (part "C-EU0402-C-NOSILK"))
    )
    (comp (ref "D10")
      (value "GREEN")
      (footprint "eagle-import:LED-0603")
      (description "Green 573nm LED Indication - Discrete 2V 0603 (1608 Metric)")
      (fields
        (field (name "DIGI-KEY_PART_NUMBER") "732-12017-1-ND")
        (field (name "MANUFACTURER") "Würth Elektronik")
      )
      (libsource (lib "eagle-import") (part "LED0603"))
    )
    (comp (ref "D11")
      (value "GREEN")
      (footprint "eagle-import:LED-0603")
      (description "Green 573nm LED Indication - Discrete 2V 0603 (1608 Metric)")
      (fields
        (field (name "DIGI-KEY_PART_NUMBER") "732-12017-1-ND")
        (field (name "MANUFACTURER") "Würth Elektronik")
      )
      (libsource (lib "eagle-import") (part "LED0603"))
    )
    (comp (ref "J2")
      (value "SM06B-SRSS-TB(LF)(SN)")
      (footprint "eagle-import:CONN_SM06B-SRSS-TB_JST")
      (fields (field (name "COPYRIGHT") "Copyright (C) 2018 Accelerated Designs. All rights reserved"))
      (libsource (lib "eagle-import") (part "SM06B-SRSS-TB(LF)(SN)"))
    )
    (comp (ref "J5")
      (value "2X1_TH_JUMPEP")
      (footprint "eagle-import:2X1")
      (libsource (lib "eagle-import") (part "2X1_TH_JUMPEP"))
    )
    (comp (ref "J9")
      (value "U.FL-R-SMA")
      (footprint "eagle-import:U.FL-R-SMT")
      (libsource (lib "eagle-import") (part "U.FL-R-SMA"))
    )
    (comp (ref "L7")
      (value "1.7nH")
      (footprint "eagle-import:.0402-C-NOSILK")
      (description "1.7nH RF Inductor, ceramic core, 5% tol, SMT, RoHS")
      (fields (field (name "MFR") "Coilcraft") (field (name "MPN") "0402DC-1N7XJRU"))
      (libsource (lib "eagle-import") (part "L-US0402-C-NOSILK"))
    )
    (comp (ref "L8")
      (value "6.8nH")
      (footprint "eagle-import:.0805-C-NOSILK")
      (description "Fixed Inductors 0805CS 6.8 nH 5 % 0.6 A")
      (fields (field (name "MFR") "Coilcraft") (field (name "MPN") "0805CS-060XJLC"))
      (libsource (lib "eagle-import") (part "L-US0805-C-NOSILK"))
    )
    (comp (ref "L9")
      (value "1.0nH")
      (footprint "eagle-import:.0402-C-NOSILK")
      (description "FIXED IND 1NH 500MA 100 MOHM SMD")
      (fields (field (name "MFR") "TDK Corporation") (field (name "MPN") "MLK1005S1N0ST000"))
      (libsource (lib "eagle-import") (part "L-US0402-C-NOSILK"))
    )
    (comp (ref "L10")
      (value "10nH")
      (footprint "eagle-import:INDC2928X203N")
      (description "Fixed Inductors 1008 10nH Unshld 5% 1.6A 60mOhms")
      (fields (field (name "MFR") "COILCRAFT") (field (name "MPN") "1008HQ-10NXJLB"))
      (libsource (lib "eagle-import") (part "1008HQ-10NXJLB"))
    )
    (comp (ref "PCBA1")
      (value "WF-NP9202WF")
      (footprint "eagle-import:WF-NP9202")
      (libsource (lib "eagle-import") (part "WF-NP9202WF"))
    )
    (comp (ref "R16")
      (value "10k")
      (footprint "eagle-import:.0603-A")
      (libsource (lib "eagle-import") (part "R-US_0603-A"))
    )
    (comp (ref "R17")
      (value "10k")
      (footprint "eagle-import:.0603-A")
      (libsource (lib "eagle-import") (part "R-US_0603-A"))
    )
    (comp (ref "R18")
      (value "10k")
      (footprint "eagle-import:.0603-A")
      (libsource (lib "eagle-import") (part "R-US_0603-A"))
    )
    (comp (ref "R21")
      (value "10k")
      (footprint "eagle-import:.0603-A")
      (libsource (lib "eagle-import") (part "R-US_0603-A"))
    )
    (comp (ref "R29")
      (value "4.7k")
      (footprint "eagle-import:.0603-A")
      (libsource (lib "eagle-import") (part "R-US_0603-A"))
    )
    (comp (ref "R30")
      (value "10k")
      (footprint "eagle-import:.0603-A")
      (libsource (lib "eagle-import") (part "R-US_0603-A"))
    )
    (comp (ref "R80")
      (value "0")
      (footprint "eagle-import:R0805")
      (description "RES SMD 0 OHM JUMPER 1/8W 0805")
      (fields (field (name "MFR") "Panasonic") (field (name "MPN") "ERJ-6GEY0R00V"))
      (libsource (lib "eagle-import") (part "rcl_334_R-US_R0805"))
    )
    (comp (ref "R81")
      (value "110")
      (footprint "eagle-import:.0402-B-NOSILK")
      (description "RES SMD 110 OHM 1% 1/10W 0402")
      (fields (field (name "MFR") "Panasonic") (field (name "MPN") "ERJ-2RKF1100X"))
      (libsource (lib "eagle-import") (part "R-US_0402-B-NOSILK"))
    )
    (comp (ref "R82")
      (value "220")
      (footprint "eagle-import:.0603-C-NOSILK")
      (description "RES SMD 220 OHM 1% 1/10W 0603")
      (fields (field (name "MFR") "Panasonic") (field (name "MPN") "ERJ-3EKF2200V"))
      (libsource (lib "eagle-import") (part "R-US_0603-C-NOSILK"))
    )
    (comp (ref "R84")
      (value "3.3")
      (footprint "eagle-import:.0402-C-NOSILK")
      (description "Resistor- SMD 1/16watt 3.3ohms 1% 100ppm")
      (fields (field (name "MFR") "Vishay / Dale") (field (name "MPN") "CRCW04023R30FKED"))
      (libsource (lib "eagle-import") (part "R-US_0402-C-NOSILK"))
    )
    (comp (ref "R85")
      (value "82.5")
      (footprint "eagle-import:.0603-A")
      (description "82.5 Ohms, 1%, 0603")
      (fields (field (name "MPN") "ERJ-3EKF82R5V"))
      (libsource (lib "eagle-import") (part "R-US_0603-A"))
    )
    (comp (ref "R86")
      (value "93.1")
      (footprint "eagle-import:.0603-A")
      (description "93.1 Ohms, 1%, 0603")
      (fields (field (name "MPN") "ERJ-3EKF93R1V"))
      (libsource (lib "eagle-import") (part "R-US_0603-A"))
    )
    (comp (ref "R87")
      (value "41.2")
      (footprint "eagle-import:.0603-A")
      (description "41.2 Ohms, 1%, 0603")
      (fields (field (name "MFR") "Panasonic") (field (name "MPN") "ERJ-3EKF41R2V"))
      (libsource (lib "eagle-import") (part "R-US_0603-A"))
    )
    (comp (ref "R88")
      (value "41.2")
      (footprint "eagle-import:.0603-A")
      (description "41.2 Ohms, 1%, 0603")
      (fields (field (name "MFR") "Panasonic") (field (name "MPN") "ERJ-3EKF41R2V"))
      (libsource (lib "eagle-import") (part "R-US_0603-A"))
    )
    (comp (ref "RT2")
      (value "TDK NTCG163JX103DT1S")
      (footprint "eagle-import:0603-THERMISTOR-B")
      (libsource (lib "eagle-import") (part "THERMISTOR--0603-THERMISTOR-B"))
    )
    (comp (ref "U6")
      (value "SN74LVC1G32QDBVRQ1")
      (footprint "eagle-import:DBV5")
      (fields
        (field (name "GENERIC_PART_NUMBER") "SN74LVC1G32-Q1")
        (field (name "MANUFACTURER") "Texas Instruments")
      )
      (libsource (lib "eagle-import") (part "SN74LVC1G32QDBVRQ1"))
    )
    (comp (ref "U8")
      (value "MIC94090YC6-TR")
      (footprint "eagle-import:SC-70-6_MCH")
      (fields
        (field (name "MANUFACTURER_PART_NUMBER") "MIC94090YC6")
        (field (name "COPYRIGHT") "Copyright (C) 2018 Accelerated Designs. All rights reserved")
      )
      (libsource (lib "eagle-import") (part "MIC94090YC6-TR"))
    )
    (comp (ref "U19")
      (value "TQP9111")
      (footprint "eagle-import:QFN50P400X400X102-21N")
      (fields (field (name "MFR") "Qorvo"))
      (libsource (lib "eagle-import") (part "TQP9111"))
    )
  )
  (nets
    (net (code "1") (name "1.8V-A") (class "Default")
      (node (ref "C24") (pin "1") (pinfunction "1_1") (pintype "passive"))
      (node (ref "C25") (pin "1") (pinfunction "1_1") (pintype "passive"))
      (node (ref "C26") (pin "1") (pinfunction "1_1") (pintype "passive"))
      (node (ref "R18") (pin "1") (pinfunction "1_1") (pintype "passive"))
      (node (ref "TP171") (pin "1") (pinfunction "1_1") (pintype "bidirectional"))
      (node (ref "TP8") (pin "1") (pinfunction "1_1") (pintype "passive"))
      (node (ref "U7") (pin "A7") (pinfunction "SYS_ADC_1P8V_A7") (pintype "bidirectional"))
      (node (ref "U7") (pin "B7") (pinfunction "VREFP_B7") (pintype "bidirectional"))
      (node (ref "U7") (pin "N13") (pinfunction "PMIC_MUX_IN_N13") (pintype "bidirectional"))
    )
    (net (code "2") (name "3.3V") (class "Default")
      (node (ref "C11") (pin "1") (pinfunction "1_1") (pintype "passive"))
      (node (ref "C15") (pin "1") (pinfunction "1_1") (pintype "passive"))
      (node (ref "C2") (pin "1") (pinfunction "1_1") (pintype "passive"))
      (node (ref "C3") (pin "1") (pinfunction "1_1") (pintype "passive"))
      (node (ref "C31") (pin "2") (pinfunction "2_2") (pintype "passive"))
      (node (ref "C40") (pin "2") (pinfunction "2_2") (pintype "passive"))
      (node (ref "C5") (pin "1") (pinfunction "1_1") (pintype "passive"))
      (node (ref "C6") (pin "1") (pinfunction "1_1") (pintype "passive"))
      (node (ref "C65") (pin "1") (pinfunction "1_1") (pintype "passive"))
      (node (ref "C8") (pin "1") (pinfunction "1_1") (pintype "passive"))
      (node (ref "C9") (pin "1") (pinfunction "1_1") (pintype "passive"))
      (node (ref "J5") (pin "P$1") (pinfunction "1_P$1") (pintype "passive"))
      (node (ref "J7") (pin "4") (pinfunction "VDD_4") (pintype "bidirectional"))
      (node (ref "J8") (pin "1") (pinfunction "VTREF_1") (pintype "passive"))
      (node (ref "R1") (pin "1") (pinfunction "1_1") (pintype "passive"))
      (node (ref "R10") (pin "10") (pinfunction "55_10") (pintype "passive"))
      (node (ref "R10") (pin "5") (pinfunction "55_5") (pintype "passive"))
      (node (ref "R20") (pin "2") (pinfunction "2_2") (pintype "passive"))
      (node (ref "R22") (pin "2") (pinfunction "2_2") (pintype "passive"))
      (node (ref "R24") (pin "10") (pinfunction "55_10") (pintype "passive"))
      (node (ref "R24") (pin "5") (pinfunction "55_5") (pintype "passive"))
      (node (ref "R6") (pin "2") (pinfunction "2_2") (pintype "passive"))
      (node (ref "R60") (pin "1") (pinfunction "1_1") (pintype "passive"))
      (node (ref "R7") (pin "2") (pinfunction "2_2") (pintype "passive"))
      (node (ref "R76") (pin "2") (pinfunction "2_2") (pintype "passive"))
      (node (ref "R8") (pin "10") (pinfunction "55_10") (pintype "passive"))
      (node (ref "R8") (pin "5") (pinfunction "55_5") (pintype "passive"))
      (node (ref "R9") (pin "10") (pinfunction "55_10") (pintype "passive"))
      (node (ref "R9") (pin "5") (pinfunction "55_5") (pintype "passive"))
      (node (ref "R97") (pin "1") (pinfunction "1_1") (pintype "passive"))
      (node (ref "R99") (pin "1") (pinfunction "1_1") (pintype "passive"))
      (node (ref "TP25") (pin "1") (pinfunction "1_1") (pintype "bidirectional"))
      (node (ref "U$1") (pin "P$1") (pinfunction "1_P$1") (pintype "passive"))
      (node (ref "U11") (pin "3") (pinfunction "VCC_3") (pintype "power_in"))
      (node (ref "U17") (pin "8") (pinfunction "VCC_8") (pintype "power_in"))
      (node (ref "U2") (pin "22") (pinfunction "~{OVRCUR4}_22") (pintype "input"))
      (node (ref "U2") (pin "25") (pinfunction "VCC_25") (pintype "power_in"))
      (node (ref "U2") (pin "26") (pinfunction "~{EXTMEM}_26") (pintype "input"))
      (node (ref "U2") (pin "3") (pinfunction "VCC_3") (pintype "power_in"))
      (node (ref "U3") (pin "C6") (pinfunction "VDDQ_C6") (pintype "power_in"))
      (node (ref "U3") (pin "E6") (pinfunction "VDDIO_E6") (pintype "power_in"))
      (node (ref "U3") (pin "F5") (pinfunction "VDDIO_F5") (pintype "power_in"))
      (node (ref "U3") (pin "J10") (pinfunction "VDDIO_J10") (pintype "power_in"))
      (node (ref "U3") (pin "K9") (pinfunction "VDDIO_K9") (pintype "power_in"))
      (node (ref "U3") (pin "M4") (pinfunction "VDDQ_M4") (pintype "power_in"))
      (node (ref "U3") (pin "N4") (pinfunction "VDDQ_N4") (pintype "power_in"))
      (node (ref "U3") (pin "P3") (pinfunction "VDDQ_P3") (pintype "power_in"))
      (node (ref "U3") (pin "P5") (pinfunction "VDDQ_P5") (pintype "power_in"))
      (node (ref "U6") (pin "5") (pinfunction "VCC_5") (pintype "power_in"))
      (node (ref "U7") (pin "F6") (pinfunction "SYS_VDD1_3P3V_F6") (pintype "power_in"))
      (node (ref "U7") (pin "F7") (pinfunction "SYS_VDD1_3P3V_F7") (pintype "power_in"))
      (node (ref "U7") (pin "G6") (pinfunction "SYS_VDD1_3P3V_G6") (pintype "power_in"))
      (node (ref "U7") (pin "G7") (pinfunction "SYS_VDD1_3P3V_G7") (pintype "power_in"))
    )
    (net (code "3") (name "3.3VA") (class "Default")
      (node (ref "C41") (pin "1") (pinfunction "1_1") (pintype "passive"))
      (node (ref "JP101") (pin "1") (pinfunction "1_1") (pintype "passive"))
      (node (ref "TP165") (pin "1") (pinfunction "1_1") (pintype "bidirectional"))
      (node (ref "U18") (pin "5") (pinfunction "VCC_5") (pintype "power_in"))
      (node (ref "U7") (pin "F8") (pinfunction "SYS_VDD3_3P3V_F8") (pintype "power_in"))
      (node (ref "U7") (pin "F9") (pinfunction "VDDSHV4_F9") (pintype "power_in"))
      (node (ref "U7") (pin "G8") (pinfunction "SYS_VDD3_3P3V_G8") (pintype "power_in"))
      (node (ref "U7") (pin "G9") (pinfunction "VDDSHV5_G9") (pintype "power_in"))
      (node (ref "U7") (pin "H7") (pinfunction "SYS_VDD3_3P3V_H7") (pintype "power_in"))
      (node (ref "U7") (pin "H8") (pinfunction "SYS_VDD3_3P3V_H8") (pintype "power_in"))
      (node (ref "U7") (pin "H9") (pinfunction "VDDSHV6_H9") (pintype "power_in"))
      (node (ref "U7") (pin "J7") (pinfunction "SYS_VDD3_3P3V_J7") (pintype "power_in"))
      (node (ref "U7") (pin "J8") (pinfunction "SYS_VDD3_3P3V_J8") (pintype "power_in"))
      (node (ref "U7") (pin "J9") (pinfunction "VDDSHV1_J9") (pintype "power_in"))
      (node (ref "U7") (pin "K8") (pinfunction "SYS_VDD3_3P3V_K8") (pintype "power_in"))
      (node (ref "U7") (pin "K9") (pinfunction "VDDSHV2_K9") (pintype "power_in"))
      (node (ref "U7") (pin "L8") (pinfunction "SYS_VDD3_3P3V_L8") (pintype "power_in"))
      (node (ref "U7") (pin "L9") (pinfunction "VDDSHV3_L9") (pintype "power_in"))
    )
    (net (code "4") (name "5V") (class "Default")
      (node (ref "C1") (pin "1") (pinfunction "1_1") (pintype "passive"))
      (node (ref "C14") (pin "1") (pinfunction "1_1") (pintype "passive"))
      (node (ref "C28") (pin "1") (pinfunction "1_1") (pintype "passive"))
      (node (ref "C36") (pin "1") (pinfunction "1_1") (pintype "passive"))
      (node (ref "C54") (pin "1") (pinfunction "1_1") (pintype "passive"))
      (node (ref "L1") (pin "2") (pinfunction "2_2") (pintype "passive"))
      (node (ref "R62") (pin "2") (pinfunction "2_2") (pintype "passive"))
      (node (ref "TP49") (pin "1") (pinfunction "1_1") (pintype "passive"))
      (node (ref "U15") (pin "10") (pinfunction "FB_10") (pintype "input"))
      (node (ref "U20") (pin "5") (pinfunction "IN_5") (pintype "power_in"))
      (node (ref "U21") (pin "5") (pinfunction "IN_5") (pintype "power_in"))
      (node (ref "U7") (pin "P10") (pinfunction "VIN_AC_P10") (pintype "power_in"))
      (node (ref "U7") (pin "R10") (pinfunction "VIN_AC_R10") (pintype "power_in"))
      (node (ref "U7") (pin "T10") (pinfunction "VIN_AC_T10") (pintype "power_in"))
      (node (ref "U9") (pin "5") (pinfunction "IN_5") (pintype "power_in"))
    )
    (net (code "5") (name "5V_PA") (class "Default")
      (node (ref "C20") (pin "1") (pinfunction "1_1") (pintype "passive"))
      (node (ref "C21") (pin "1") (pinfunction "1_1") (pintype "passive"))
      (node (ref "L2") (pin "2") (pinfunction "2_2") (pintype "passive"))
      (node (ref "R11") (pin "2") (pinfunction "2_2") (pintype "passive"))
      (node (ref "R80") (pin "2") (pinfunction "2_2") (pintype "passive"))
      (node (ref "TP7") (pin "1") (pinfunction "1_1") (pintype "passive"))
      (node (ref "U5") (pin "10") (pinfunction "FB_10") (pintype "input"))
      (node (ref "U8") (pin "4") (pinfunction "VIN_4") (pintype "input"))
    )
    (net (code "6") (name "AD0") (class "Default")
      (node (ref "R57") (pin "1") (pinfunction "1_1") (pintype "passive"))
      (node (ref "R58") (pin "2") (pinfunction "2_2") (pintype "passive"))
      (node (ref "R69") (pin "2") (pinfunction "2_2") (pintype "passive"))
      (node (ref "R70") (pin "1") (pinfunction "1_1") (pintype "passive"))
      (node (ref "U16") (pin "1") (pinfunction "AD0_1") (pintype "input"))
    )
    (net (code "7") (name "AD1") (class "Default")
      (node (ref "R55") (pin "1") (pinfunction "1_1") (pintype "passive"))
      (node (ref "R56") (pin "2") (pinfunction "2_2") (pintype "passive"))
      (node (ref "R67") (pin "2") (pinfunction "2_2") (pintype "passive"))
      (node (ref "R68") (pin "1") (pinfunction "1_1") (pintype "passive"))
      (node (ref "U16") (pin "2") (pinfunction "AD1_2") (pintype "input"))
    )
    (net (code "8") (name "AD2") (class "Default")
      (node (ref "R53") (pin "1") (pinfunction "1_1") (pintype "passive"))
      (node (ref "R54") (pin "2") (pinfunction "2_2") (pintype "passive"))
      (node (ref "R65") (pin "2") (pinfunction "2_2") (pintype "passive"))
      (node (ref "R66") (pin "1") (pinfunction "1_1") (pintype "passive"))
      (node (ref "U16") (pin "3") (pinfunction "AD2_3") (pintype "input"))
    )
    (net (code "9") (name "BOOT0") (class "Default")
      (node (ref "TP51") (pin "1") (pinfunction "1_1") (pintype "passive"))
      (node (ref "U16") (pin "10") (pinfunction "IO5_10") (pintype "bidirectional"))
    )
    (net (code "10") (name "CAN1_H") (class "Default")
      (node (ref "J4") (pin "33") (pinfunction "33_33") (pintype "passive"))
      (node (ref "J4") (pin "34") (pinfunction "34_34") (pintype "passive"))
      (node (ref "TP184") (pin "1") (pinfunction "1_1") (pintype "bidirectional"))
    )
    (net (code "11") (name "CAN1_L") (class "Default")
      (node (ref "J4") (pin "35") (pinfunction "35_35") (pintype "passive"))
      (node (ref "J4") (pin "36") (pinfunction "36_36") (pintype "passive"))
      (node (ref "TP183") (pin "1") (pinfunction "1_1") (pintype "bidirectional"))
    )
    (net (code "12") (name "CAN2_H") (class "Default")
      (node (ref "J4") (pin "17") (pinfunction "17_17") (pintype "passive"))
      (node (ref "J4") (pin "18") (pinfunction "18_18") (pintype "passive"))
      (node (ref "U11") (pin "7") (pinfunction "CANH_7") (pintype "bidirectional"))
    )
    (net (code "13") (name "CAN2_L") (class "Default")
      (node (ref "J4") (pin "19") (pinfunction "19_19") (pintype "passive"))
      (node (ref "J4") (pin "20") (pinfunction "20_20") (pintype "passive"))
      (node (ref "U11") (pin "6") (pinfunction "CANL_6") (pintype "bidirectional"))
    )
    (net (code "14") (name "CB-RESET") (class "Default")
      (node (ref "R39") (pin "2") (pinfunction "2_2") (pintype "passive"))
      (node (ref "TP54") (pin "1") (pinfunction "1_1") (pintype "passive"))
      (node (ref "U14") (pin "9") (pinfunction "CIN2-_9") (pintype "input"))
      (node (ref "U16") (pin "9") (pinfunction "IO4_9") (pintype "bidirectional"))
    )
    (net (code "15") (name "CB_CTRL") (class "Default")
      (node (ref "Q2") (pin "1") (pinfunction "G_1") (pintype "passive"))
      (node (ref "Q5") (pin "3") (pinfunction "G_3") (pintype "passive"))
      (node (ref "R64") (pin "1") (pinfunction "1_1") (pintype "passive"))
      (node (ref "TP52") (pin "1") (pinfunction "1_1") (pintype "passive"))
      (node (ref "U14") (pin "3") (pinfunction "LE_3") (pintype "input"))
      (node (ref "U14") (pin "4") (pinfunction "COUT1_4") (pintype "open_collector"))
      (node (ref "U14") (pin "6") (pinfunction "COUT2_6") (pintype "open_collector"))
    )
    (net (code "16") (name "EEPROM_WP") (class "Default")
      (node (ref "J1") (pin "20") (pinfunction "DEBUG-3_20") (pintype "passive"))
      (node (ref "R75") (pin "1") (pinfunction "1_1") (pintype "passive"))
      (node (ref "TP112") (pin "1") (pinfunction "1_1") (pintype "bidirectional"))
      (node (ref "U18") (pin "6") (pinfunction "I4_6") (pintype "bidirectional"))
    )
    (net (code "17") (name "GND") (class "Default")
      (node (ref "C1") (pin "2") (pinfunction "2_2") (pintype "passive"))
      (node (ref "C10") (pin "2") (pinfunction "2_2") (pintype "passive"))
      (node (ref "C11") (pin "2") (pinfunction "2_2") (pintype "passive"))
      (node (ref "C12") (pin "2") (pinfunction "2_2") (pintype "passive"))
      (node (ref "C13") (pin "2") (pinfunction "2_2") (pintype "passive"))
      (node (ref "C14") (pin "2") (pinfunction "2_2") (pintype "passive"))
      (node (ref "C15") (pin "2") (pinfunction "2_2") (pintype "passive"))
      (node (ref "C16") (pin "2") (pinfunction "2_2") (pintype "passive"))
      (node (ref "C17") (pin "2") (pinfunction "2_2") (pintype "passive"))
      (node (ref "C18") (pin "2") (pinfunction "2_2") (pintype "passive"))
      (node (ref "C2") (pin "2") (pinfunction "2_2") (pintype "passive"))
      (node (ref "C20") (pin "2") (pinfunction "2_2") (pintype "passive"))
      (node (ref "C21") (pin "2") (pinfunction "2_2") (pintype "passive"))
      (node (ref "C23") (pin "2") (pinfunction "2_2") (pintype "passive"))
      (node (ref "C24") (pin "2") (pinfunction "2_2") (pintype "passive"))
      (node (ref "C25") (pin "2") (pinfunction "2_2") (pintype "passive"))
      (node (ref "C26") (pin "2") (pinfunction "2_2") (pintype "passive"))
      (node (ref "C27") (pin "2") (pinfunction "2_2") (pintype "passive"))
      (node (ref "C28") (pin "2") (pinfunction "2_2") (pintype "passive"))
      (node (ref "C3") (pin "2") (pinfunction "2_2") (pintype "passive"))
      (node (ref "C31") (pin "1") (pinfunction "1_1") (pintype "passive"))
      (node (ref "C32") (pin "2") (pinfunction "2_2") (pintype "passive"))
      (node (ref "C34") (pin "2") (pinfunction "2_2") (pintype "passive"))
      (node (ref "C35") (pin "2") (pinfunction "2_2") (pintype "passive"))
      (node (ref "C36") (pin "2") (pinfunction "2_2") (pintype "passive"))
      (node (ref "C37") (pin "2") (pinfunction "2_2") (pintype "passive"))
      (node (ref "C38") (pin "2") (pinfunction "2_2") (pintype "passive"))
      (node (ref "C39") (pin "1") (pinfunction "1_1") (pintype "passive"))
      (node (ref "C4") (pin "2") (pinfunction "2_2") (pintype "passive"))
      (node (ref "C40") (pin "1") (pinfunction "1_1") (pintype "passive"))
      (node (ref "C41") (pin "2") (pinfunction "2_2") (pintype "passive"))
      (node (ref "C42") (pin "2") (pinfunction "2_2") (pintype "passive"))
      (node (ref "C43") (pin "2") (pinfunction "2_2") (pintype "passive"))
      (node (ref "C44") (pin "2") (pinfunction "2_2") (pintype "passive"))
      (node (ref "C45") (pin "2") (pinfunction "2_2") (pintype "passive"))
      (node (ref "C46") (pin "2") (pinfunction "2_2") (pintype "passive"))
      (node (ref "C47") (pin "2") (pinfunction "2_2") (pintype "passive"))
      (node (ref "C48") (pin "2") (pinfunction "2_2") (pintype "passive"))
      (node (ref "C5") (pin "2") (pinfunction "2_2") (pintype "passive"))
      (node (ref "C50") (pin "2") (pinfunction "2_2") (pintype "passive"))
      (node (ref "C52") (pin "2") (pinfunction "2_2") (pintype "passive"))
      (node (ref "C53") (pin "2") (pinfunction "2_2") (pintype "passive"))
      (node (ref "C54") (pin "2") (pinfunction "2_2") (pintype "passive"))
      (node (ref "C55") (pin "2") (pinfunction "2_2") (pintype "passive"))
      (node (ref "C56") (pin "2") (pinfunction "2_2") (pintype "passive"))
      (node (ref "C57") (pin "2") (pinfunction "2_2") (pintype "passive"))
      (node (ref "C58") (pin "2") (pinfunction "2_2") (pintype "passive"))
      (node (ref "C59") (pin "2") (pinfunction "2_2") (pintype "passive"))
      (node (ref "C6") (pin "2") (pinfunction "2_2") (pintype "passive"))
      (node (ref "C60") (pin "2") (pinfunction "2_2") (pintype "passive"))
      (node (ref "C61") (pin "2") (pinfunction "2_2") (pintype "passive"))
      (node (ref "C62") (pin "2") (pinfunction "2_2") (pintype "passive"))
      (node (ref "C63") (pin "2") (pinfunction "2_2") (pintype "passive"))
      (node (ref "C64") (pin "2") (pinfunction "2_2") (pintype "passive"))
      (node (ref "C65") (pin "2") (pinfunction "2_2") (pintype "passive"))
      (node (ref "C7") (pin "2") (pinfunction "2_2") (pintype "passive"))
      (node (ref "C8") (pin "2") (pinfunction "2_2") (pintype "passive"))
      (node (ref "C9") (pin "2") (pinfunction "2_2") (pintype "passive"))
      (node (ref "D1") (pin "C") (pinfunction "C_C") (pintype "passive"))
      (node (ref "D11") (pin "C") (pinfunction "C_C") (pintype "passive"))
      (node (ref "D2") (pin "C") (pinfunction "C_C") (pintype "passive"))
      (node (ref "D3") (pin "C") (pinfunction "C_C") (pintype "passive"))
      (node (ref "D4") (pin "C") (pinfunction "C_C") (pintype "passive"))
      (node (ref "D5") (pin "C") (pinfunction "C_C") (pintype "passive"))
      (node (ref "D6") (pin "C") (pinfunction "C_C") (pintype "passive"))
      (node (ref "D7") (pin "C") (pinfunction "C_C") (pintype "passive"))
      (node (ref "D8") (pin "C") (pinfunction "C_C") (pintype "passive"))
      (node (ref "D9") (pin "C") (pinfunction "C_C") (pintype "passive"))
      (node (ref "J1") (pin "3") (pinfunction "GND_3") (pintype "passive"))
      (node (ref "J1") (pin "6") (pinfunction "GND_6") (pintype "passive"))
      (node (ref "J1") (pin "9") (pinfunction "GND_9") (pintype "passive"))
      (node (ref "J1") (pin "PAD1") (pinfunction "PAD_PAD1") (pintype "bidirectional"))
      (node (ref "J1") (pin "PAD2") (pinfunction "PAD_PAD2") (pintype "bidirectional"))
      (node (ref "J10") (pin "3") (pinfunction "3_3") (pintype "passive"))
      (node (ref "J10") (pin "7") (pinfunction "7_7") (pintype "passive"))
      (node (ref "J10") (pin "8") (pinfunction "7_8") (pintype "passive"))
      (node (ref "J2") (pin "3") (pinfunction "3_3") (pintype "passive"))
      (node (ref "J2") (pin "7") (pinfunction "7_7") (pintype "passive"))
      (node (ref "J2") (pin "8") (pinfunction "7_8") (pintype "passive"))
      (node (ref "J4") (pin "27") (pinfunction "27_27") (pintype "passive"))
      (node (ref "J4") (pin "28") (pinfunction "28_28") (pintype "passive"))
      (node (ref "J4") (pin "29") (pinfunction "29_29") (pintype "passive"))
      (node (ref "J4") (pin "30") (pinfunction "30_30") (pintype "passive"))
      (node (ref "J4") (pin "31") (pinfunction "31_31") (pintype "passive"))
      (node (ref "J4") (pin "32") (pinfunction "32_32") (pintype "passive"))
      (node (ref "J4") (pin "37") (pinfunction "37_37") (pintype "passive"))
      (node (ref "J4") (pin "38") (pinfunction "38_38") (pintype "passive"))
      (node (ref "J6") (pin "P$1") (pinfunction "SHIELD3_P$1") (pintype "passive"))
      (node (ref "J6") (pin "P$2") (pinfunction "SHIELD2_P$2") (pintype "passive"))
      (node (ref "J6") (pin "P$3") (pinfunction "SHIELD1_P$3") (pintype "passive"))
      (node (ref "J6") (pin "P$4") (pinfunction "SHIELD_P$4") (pintype "passive"))
      (node (ref "J7") (pin "6") (pinfunction "VSS_6") (pintype "bidirectional"))
      (node (ref "J7") (pin "CGND1") (pinfunction "CGND_CGND1") (pintype "bidirectional"))
      (node (ref "J7") (pin "CGND2") (pinfunction "CGND_CGND2") (pintype "bidirectional"))
      (node (ref "J7") (pin "CGND3") (pinfunction "CGND_CGND3") (pintype "bidirectional"))
      (node (ref "J7") (pin "CGND4") (pinfunction "CGND_CGND4") (pintype "bidirectional"))
      (node (ref "J7") (pin "CGND5") (pinfunction "CGND_CGND5") (pintype "bidirectional"))
      (node (ref "J7") (pin "CGND6") (pinfunction "CGND_CGND6") (pintype "bidirectional"))
      (node (ref "J7") (pin "GND") (pinfunction "VSS_GND") (pintype "bidirectional"))
      (node (ref "J8") (pin "3") (pinfunction "GND_3") (pintype "passive"))
      (node (ref "J8") (pin "5") (pinfunction "GND_5") (pintype "passive"))
      (node (ref "J8") (pin "9") (pinfunction "GNDDET_9") (pintype "passive"))
      (node (ref "J9") (pin "2") (pinfunction "P$2_2") (pintype "bidirectional"))
      (node (ref "J9") (pin "3") (pinfunction "P$2_3") (pintype "bidirectional"))
      (node (ref "JP100") (pin "2") (pinfunction "2_2") (pintype "passive"))
      (node (ref "L7") (pin "1") (pinfunction "1_1") (pintype "passive"))
      (node (ref "Q2") (pin "2") (pinfunction "S_2") (pintype "passive"))
      (node (ref "Q4") (pin "2") (pinfunction "S_2") (pintype "passive"))
      (node (ref "R100") (pin "1") (pinfunction "1_1") (pintype "passive"))
      (node (ref "R101") (pin "1") (pinfunction "1_1") (pintype "passive"))
      (node (ref "R14") (pin "1") (pinfunction "1_1") (pintype "passive"))
      (node (ref "R15") (pin "1") (pinfunction "1_1") (pintype "passive"))
      (node (ref "R16") (pin "1") (pinfunction "1_1") (pintype "passive"))
      (node (ref "R17") (pin "1") (pinfunction "1_1") (pintype "passive"))
      (node (ref "R19") (pin "1") (pinfunction "1_1") (pintype "passive"))
      (node (ref "R25") (pin "10") (pinfunction "55_10") (pintype "passive"))
      (node (ref "R25") (pin "5") (pinfunction "55_5") (pintype "passive"))
      (node (ref "R26") (pin "10") (pinfunction "55_10") (pintype "passive"))
      (node (ref "R26") (pin "5") (pinfunction "55_5") (pintype "passive"))
      (node (ref "R33") (pin "1") (pinfunction "1_1") (pintype "passive"))
      (node (ref "R39") (pin "1") (pinfunction "1_1") (pintype "passive"))
      (node (ref "R40") (pin "1") (pinfunction "1_1") (pintype "passive"))
      (node (ref "R42") (pin "1") (pinfunction "1_1") (pintype "passive"))
      (node (ref "R46") (pin "1") (pinfunction "1_1") (pintype "passive"))
      (node (ref "R51") (pin "1") (pinfunction "1_1") (pintype "passive"))
      (node (ref "R54") (pin "1") (pinfunction "1_1") (pintype "passive"))
      (node (ref "R56") (pin "1") (pinfunction "1_1") (pintype "passive"))
      (node (ref "R58") (pin "1") (pinfunction "1_1") (pintype "passive"))
      (node (ref "R59") (pin "2") (pinfunction "2_2") (pintype "passive"))
      (node (ref "R78") (pin "1") (pinfunction "1_1") (pintype "passive"))
      (node (ref "R83") (pin "1") (pinfunction "1_1") (pintype "passive"))
      (node (ref "R85") (pin "1") (pinfunction "1_1") (pintype "passive"))
      (node (ref "R88") (pin "2") (pinfunction "2_2") (pintype "passive"))
      (node (ref "R90") (pin "1") (pinfunction "1_1") (pintype "passive"))
      (node (ref "R92") (pin "1") (pinfunction "1_1") (pintype "passive"))
      (node (ref "R94") (pin "1") (pinfunction "1_1") (pintype "passive"))
      (node (ref "R96") (pin "1") (pinfunction "1_1") (pintype "passive"))
      (node (ref "RT2") (pin "2") (pinfunction "2_2") (pintype "passive"))
      (node (ref "U$1") (pin "P$3") (pinfunction "3_P$3") (pintype "passive"))
      (node (ref "U1") (pin "2") (pinfunction "GND_2") (pintype "power_in"))
      (node (ref "U11") (pin "2") (pinfunction "GND_2") (pintype "power_in"))
      (node (ref "U12") (pin "2") (pinfunction "GND_2") (pintype "power_in"))
      (node (ref "U13") (pin "2") (pinfunction "GND_2") (pintype "power_in"))
      (node (ref "U14") (pin "7") (pinfunction "GND_7") (pintype "power_in"))
      (node (ref "U14") (pin "EPAD") (pinfunction "GND_EPAD") (pintype "power_in"))
      (node (ref "U15") (pin "1") (pinfunction "GND_1") (pintype "power_in"))
      (node (ref "U15") (pin "11") (pinfunction "GND_11") (pintype "power_in"))
      (node (ref "U15") (pin "12") (pinfunction "GND_12") (pintype "power_in"))
      (node (ref "U15") (pin "16") (pinfunction "GND_16") (pintype "power_in"))
      (node (ref "U15") (pin "6") (pinfunction "LBO_6") (pintype "open_collector"))
      (node (ref "U15") (pin "7") (pinfunction "LBI_7") (pintype "input"))
      (node (ref "U15") (pin "9") (pinfunction "GND_9") (pintype "power_in"))
      (node (ref "U15") (pin "PAD") (pinfunction "GND_PAD") (pintype "power_in"))
      (node (ref "U16") (pin "6") (pinfunction "GND_6") (pintype "power_in"))
      (node (ref "U16") (pin "EPAD") (pinfunction "GND_EPAD") (pintype "power_in"))
      (node (ref "U17") (pin "4") (pinfunction "GND_4") (pintype "power_in"))
      (node (ref "U18") (pin "2") (pinfunction "GND_2") (pintype "power_in"))
      (node (ref "U19") (pin "1") (pinfunction "GND_1") (pintype "power_in"))
      (node (ref "U19") (pin "10") (pinfunction "GND_10") (pintype "power_in"))
      (node (ref "U19") (pin "11") (pinfunction "GND_11") (pintype "power_in"))
      (node (ref "U19") (pin "15") (pinfunction "GND_15") (pintype "power_in"))
      (node (ref "U19") (pin "17") (pinfunction "GND_17") (pintype "power_in"))
      (node (ref "U19") (pin "19") (pinfunction "GND_19") (pintype "power_in"))
      (node (ref "U19") (pin "21") (pinfunction "GND_21") (pintype "power_in"))
      (node (ref "U19") (pin "5") (pinfunction "GND_5") (pintype "power_in"))
      (node (ref "U19") (pin "7") (pinfunction "GND_7") (pintype "power_in"))
      (node (ref "U19") (pin "9") (pinfunction "GND_9") (pintype "power_in"))
      (node (ref "U2") (pin "27") (pinfunction "TSTPLL/48MCLK_27") (pintype "passive"))
      (node (ref "U2") (pin "28") (pinfunction "GND_28") (pintype "power_in"))
      (node (ref "U2") (pin "31") (pinfunction "TSTMODE_31") (pintype "passive"))
      (node (ref "U2") (pin "7") (pinfunction "GND_7") (pintype "power_in"))
      (node (ref "U20") (pin "2") (pinfunction "GND_2") (pintype "power_in"))
      (node (ref "U21") (pin "2") (pinfunction "GND_2") (pintype "power_in"))
      (node (ref "U3") (pin "A6") (pinfunction "VSSIO_A6") (pintype "power_in"))
      (node (ref "U3") (pin "C4") (pinfunction "VSSQ_C4") (pintype "power_in"))
      (node (ref "U3") (pin "E7") (pinfunction "VSSIO_E7") (pintype "power_in"))
      (node (ref "U3") (pin "G5") (pinfunction "VSSIO_G5") (pintype "power_in"))
      (node (ref "U3") (pin "H10") (pinfunction "VSSIO_H10") (pintype "power_in"))
      (node (ref "U3") (pin "J5") (pinfunction "VSSIO_J5") (pintype "power_in"))
      (node (ref "U3") (pin "K8") (pinfunction "VSSIO_K8") (pintype "power_in"))
      (node (ref "U3") (pin "N2") (pinfunction "VSSQ_N2") (pintype "power_in"))
      (node (ref "U3") (pin "N5") (pinfunction "VSSQ_N5") (pintype "power_in"))
      (node (ref "U3") (pin "P4") (pinfunction "VSSQ_P4") (pintype "power_in"))
      (node (ref "U3") (pin "P6") (pinfunction "VSSQ_P6") (pintype "power_in"))
      (node (ref "U4") (pin "3") (pinfunction "GND_3") (pintype "bidirectional"))
      (node (ref "U5") (pin "1") (pinfunction "GND_1") (pintype "power_in"))
      (node (ref "U5") (pin "11") (pinfunction "GND_11") (pintype "power_in"))
      (node (ref "U5") (pin "12") (pinfunction "GND_12") (pintype "power_in"))
      (node (ref "U5") (pin "16") (pinfunction "GND_16") (pintype "power_in"))
      (node (ref "U5") (pin "6") (pinfunction "LBO_6") (pintype "open_collector"))
      (node (ref "U5") (pin "7") (pinfunction "LBI_7") (pintype "input"))
      (node (ref "U5") (pin "9") (pinfunction "GND_9") (pintype "power_in"))
      (node (ref "U5") (pin "PAD") (pinfunction "GND_PAD") (pintype "power_in"))
      (node (ref "U6") (pin "3") (pinfunction "GND_3") (pintype "power_in"))
      (node (ref "U7") (pin "A9") (pinfunction "AGND_ADC_A9") (pintype "bidirectional"))
      (node (ref "U7") (pin "B9") (pinfunction "VREFN_B9") (pintype "bidirectional"))
      (node (ref "U7") (pin "D8") (pinfunction "DGND_D8") (pintype "bidirectional"))
      (node (ref "U7") (pin "D9") (pinfunction "DGND_D9") (pintype "bidirectional"))
      (node (ref "U7") (pin "E10") (pinfunction "DGND_E10") (pintype "bidirectional"))
      (node (ref "U7") (pin "E11") (pinfunction "DGND_E11") (pintype "bidirectional"))
      (node (ref "U7") (pin "E12") (pinfunction "DGND_E12") (pintype "bidirectional"))
      (node (ref "U7") (pin "E5") (pinfunction "DGND_E5") (pintype "bidirectional"))
      (node (ref "U7") (pin "E6") (pinfunction "DGND_E6") (pintype "bidirectional"))
      (node (ref "U7") (pin "E7") (pinfunction "DGND_E7") (pintype "bidirectional"))
      (node (ref "U7") (pin "E8") (pinfunction "DGND_E8") (pintype "bidirectional"))
      (node (ref "U7") (pin "E9") (pinfunction "DGND_E9") (pintype "bidirectional"))
      (node (ref "U7") (pin "F12") (pinfunction "DGND_F12") (pintype "bidirectional"))
      (node (ref "U7") (pin "F5") (pinfunction "DGND_F5") (pintype "bidirectional"))
      (node (ref "U7") (pin "G12") (pinfunction "DGND_G12") (pintype "bidirectional"))
      (node (ref "U7") (pin "G5") (pinfunction "DGND_G5") (pintype "bidirectional"))
      (node (ref "U7") (pin "H12") (pinfunction "DGND_H12") (pintype "bidirectional"))
      (node (ref "U7") (pin "H13") (pinfunction "DGND_H13") (pintype "bidirectional"))
      (node (ref "U7") (pin "H4") (pinfunction "DGND_H4") (pintype "bidirectional"))
      (node (ref "U7") (pin "H5") (pinfunction "DGND_H5") (pintype "bidirectional"))
      (node (ref "U7") (pin "J12") (pinfunction "DGND_J12") (pintype "bidirectional"))
      (node (ref "U7") (pin "J13") (pinfunction "DGND_J13") (pintype "bidirectional"))
      (node (ref "U7") (pin "J4") (pinfunction "DGND_J4") (pintype "bidirectional"))
      (node (ref "U7") (pin "J5") (pinfunction "DGND_J5") (pintype "bidirectional"))
      (node (ref "U7") (pin "K12") (pinfunction "DGND_K12") (pintype "bidirectional"))
      (node (ref "U7") (pin "K5") (pinfunction "DGND_K5") (pintype "bidirectional"))
      (node (ref "U7") (pin "L12") (pinfunction "DGND_L12") (pintype "bidirectional"))
      (node (ref "U7") (pin "L5") (pinfunction "DGND_L5") (pintype "bidirectional"))
      (node (ref "U7") (pin "M10") (pinfunction "DGND_M10") (pintype "bidirectional"))
      (node (ref "U7") (pin "M11") (pinfunction "DGND_M11") (pintype "bidirectional"))
      (node (ref "U7") (pin "M12") (pinfunction "DGND_M12") (pintype "bidirectional"))
      (node (ref "U7") (pin "M5") (pinfunction "DGND_M5") (pintype "bidirectional"))
      (node (ref "U7") (pin "M6") (pinfunction "DGND_M6") (pintype "bidirectional"))
      (node (ref "U7") (pin "M7") (pinfunction "DGND_M7") (pintype "bidirectional"))
      (node (ref "U7") (pin "M8") (pinfunction "DGND_M8") (pintype "bidirectional"))
      (node (ref "U7") (pin "M9") (pinfunction "DGND_M9") (pintype "bidirectional"))
      (node (ref "U7") (pin "N8") (pinfunction "DGND_N8") (pintype "bidirectional"))
      (node (ref "U7") (pin "N9") (pinfunction "DGND_N9") (pintype "bidirectional"))
      (node (ref "U8") (pin "2") (pinfunction "GND_2_2") (pintype "passive"))
      (node (ref "U8") (pin "5") (pinfunction "GND_5") (pintype "passive"))
      (node (ref "U9") (pin "2") (pinfunction "GND_2") (pintype "power_in"))
      (node (ref "Y1") (pin "2") (pinfunction "GND_2") (pintype "power_in"))
      (node (ref "Y1") (pin "4") (pinfunction "GND_4") (pintype "power_in"))
      (node (ref "Y3") (pin "2") (pinfunction "GND_2") (pintype "power_in"))
      (node (ref "Y3") (pin "4") (pinfunction "GND_4") (pintype "power_in"))
    )
    (net (code "18") (name "I2C0_SCL") (class "Default")
      (node (ref "J1") (pin "18") (pinfunction "DEBUG-1_18") (pintype "passive"))
      (node (ref "R73") (pin "1") (pinfunction "1_1") (pintype "passive"))
      (node (ref "TP155") (pin "1") (pinfunction "1_1") (pintype "bidirectional"))
      (node (ref "U18") (pin "3") (pinfunction "I2_3") (pintype "bidirectional"))
    )
    (net (code "19") (name "I2C0_SDA") (class "Default")
      (node (ref "J1") (pin "19") (pinfunction "DEBUG-2_19") (pintype "passive"))
      (node (ref "R74") (pin "1") (pinfunction "1_1") (pintype "passive"))
      (node (ref "TP151") (pin "1") (pinfunction "1_1") (pintype "bidirectional"))
      (node (ref "U18") (pin "1") (pinfunction "I1_1") (pintype "bidirectional"))
    )
    (net (code "20") (name "N$53") (class "Default")
      (node (ref "C18") (pin "1") (pinfunction "1_1") (pintype "passive"))
      (node (ref "JP104") (pin "1") (pinfunction "1_1") (pintype "passive"))
      (node (ref "TP14") (pin "1") (pinfunction "1_1") (pintype "bidirectional"))
      (node (ref "TP164") (pin "1") (pinfunction "1_1") (pintype "bidirectional"))
      (node (ref "U4") (pin "5") (pinfunction "VCC_5") (pintype "bidirectional"))
      (node (ref "U7") (pin "K11") (pinfunction "SYS_RTC_1P8V_K11") (pintype "power_in"))
      (node (ref "U7") (pin "L11") (pinfunction "SYS_RTC_1P8V_L11") (pintype "power_in"))
    )
    (net (code "21") (name "N$103") (class "Default")
      (node (ref "J4") (pin "1") (pinfunction "1_1") (pintype "passive"))
      (node (ref "J4") (pin "2") (pinfunction "2_2") (pintype "passive"))
      (node (ref "TP62") (pin "1") (pinfunction "1_1") (pintype "bidirectional"))
    )
    (net (code "22") (name "Net-(C33-Pad1)") (class "Default")
      (node (ref "C33") (pin "1") (pinfunction "1_1") (pintype "passive"))
      (node (ref "R33") (pin "2") (pinfunction "2_2") (pintype "passive"))
      (node (ref "R38") (pin "2") (pinfunction "2_2") (pintype "passive"))
    )
    (net (code "23") (name "Net-(C43-Pad1)") (class "Default")
      (node (ref "C43") (pin "1") (pinfunction "1_1") (pintype "passive"))
      (node (ref "C45") (pin "1") (pinfunction "1_1") (pintype "passive"))
      (node (ref "C46") (pin "1") (pinfunction "1_1") (pintype "passive"))
      (node (ref "C48") (pin "1") (pinfunction "1_1") (pintype "passive"))
      (node (ref "L10") (pin "2") (pinfunction "2_2") (pintype "bidirectional"))
      (node (ref "L8") (pin "2") (pinfunction "2_2") (pintype "passive"))
      (node (ref "R80") (pin "1") (pinfunction "1_1") (pintype "passive"))
      (node (ref "R82") (pin "2") (pinfunction "2_2") (pintype "passive"))
    )
    (net (code "24") (name "Net-(C49-Pad1)") (class "Default")
      (node (ref "C49") (pin "1") (pinfunction "1_1") (pintype "passive"))
      (node (ref "C52") (pin "1") (pinfunction "1_1") (pintype "passive"))
      (node (ref "L9") (pin "2") (pinfunction "2_2") (pintype "passive"))
    )
    (net (code "25") (name "Net-(C50-Pad1)") (class "Default")
      (node (ref "C50") (pin "1") (pinfunction "1_1") (pintype "passive"))
      (node (ref "L9") (pin "1") (pinfunction "1_1") (pintype "passive"))
      (node (ref "U19") (pin "12") (pinfunction "RFOUT_12") (pintype "output"))
      (node (ref "U19") (pin "13") (pinfunction "RFOUT_13") (pintype "output"))
      (node (ref "U19") (pin "14") (pinfunction "RFOUT_14") (pintype "output"))
    )
    (net (code "26") (name "Net-(C51-Pad1)") (class "Default")
      (node (ref "C51") (pin "1") (pinfunction "1_1") (pintype "passive"))
      (node (ref "L7") (pin "2") (pinfunction "2_2") (pintype "passive"))
      (node (ref "R85") (pin "2") (pinfunction "2_2") (pintype "passive"))
      (node (ref "R86") (pin "1") (pinfunction "1_1") (pintype "passive"))
    )
    (net (code "27") (name "Net-(C51-Pad2)") (class "Default")
      (node (ref "C51") (pin "2") (pinfunction "2_2") (pintype "passive"))
      (node (ref "R84") (pin "1") (pinfunction "1_1") (pintype "passive"))
    )
    (net (code "28") (name "Net-(D1-PadA)") (class "Default")
      (node (ref "D1") (pin "A") (pinfunction "A_A") (pintype "passive"))
      (node (ref "R1") (pin "2") (pinfunction "2_2") (pintype "passive"))
    )
    (net (code "29") (name "Net-(D2-PadA)") (class "Default")
      (node (ref "D2") (pin "A") (pinfunction "A_A") (pintype "passive"))
      (node (ref "R2") (pin "2") (pinfunction "2_2") (pintype "passive"))
    )
    (net (code "30") (name "Net-(D3-PadA)") (class "Default")
      (node (ref "D3") (pin "A") (pinfunction "A_A") (pintype "passive"))
      (node (ref "R3") (pin "2") (pinfunction "2_2") (pintype "passive"))
    )
    (net (code "31") (name "Net-(D4-PadA)") (class "Default")
      (node (ref "D4") (pin "A") (pinfunction "A_A") (pintype "passive"))
      (node (ref "R4") (pin "2") (pinfunction "2_2") (pintype "passive"))
    )
    (net (code "32") (name "Net-(D5-PadA)") (class "Default")
      (node (ref "D5") (pin "A") (pinfunction "A_A") (pintype "passive"))
      (node (ref "R5") (pin "2") (pinfunction "2_2") (pintype "passive"))
    )
    (net (code "33") (name "Net-(D6-PadA)") (class "Default")
      (node (ref "D6") (pin "A") (pinfunction "A_A") (pintype "passive"))
      (node (ref "R49") (pin "1") (pinfunction "1_1") (pintype "passive"))
    )
    (net (code "34") (name "Net-(D7-PadA)") (class "Default")
      (node (ref "D7") (pin "A") (pinfunction "A_A") (pintype "passive"))
      (node (ref "R61") (pin "1") (pinfunction "1_1") (pintype "passive"))
    )
    (net (code "35") (name "Net-(D8-PadA)") (class "Default")
      (node (ref "D8") (pin "A") (pinfunction "A_A") (pintype "passive"))
      (node (ref "R62") (pin "1") (pinfunction "1_1") (pintype "passive"))
    )
    (net (code "36") (name "Net-(D9-PadA)") (class "Default")
      (node (ref "D9") (pin "A") (pinfunction "A_A") (pintype "passive"))
      (node (ref "R11") (pin "1") (pinfunction "1_1") (pintype "passive"))
    )
    (net (code "37") (name "Net-(D10-PadA)") (class "Default")
      (node (ref "D10") (pin "A") (pinfunction "A_A") (pintype "passive"))
      (node (ref "R21") (pin "2") (pinfunction "2_2") (pintype "passive"))
    )
    (net (code "38") (name "Net-(D11-PadA)") (class "Default")
      (node (ref "D11") (pin "A") (pinfunction "A_A") (pintype "passive"))
      (node (ref "R30") (pin "2") (pinfunction "2_2") (pintype "passive"))
    )
    (net (code "39") (name "Net-(J5-2)") (class "Default")
      (node (ref "J5") (pin "P$2") (pinfunction "2_P$2") (pintype "passive"))
      (node (ref "R16") (pin "2") (pinfunction "2_2") (pintype "passive"))
      (node (ref "U6") (pin "1") (pinfunction "A_1") (pintype "input"))
    )
    (net (code "40") (name "Net-(J7-CD#)") (class "Default")
      (node (ref "J7") (pin "CD") (pinfunction "CD#_CD") (pintype "bidirectional"))
      (node (ref "R8") (pin "6") (pinfunction "66_6") (pintype "passive"))
      (node (ref "TP22") (pin "1") (pinfunction "1_1") (pintype "bidirectional"))
      (node (ref "U7") (pin "C14") (pinfunction "SPI0_CS1_C14") (pintype "bidirectional"))
    )
    (net (code "41") (name "Net-(J7-CLK)") (class "Default")
      (node (ref "J7") (pin "5") (pinfunction "CLK_5") (pintype "bidirectional"))
      (node (ref "R8") (pin "8") (pinfunction "88_8") (pintype "passive"))
      (node (ref "U7") (pin "B15") (pinfunction "MMC0_CLK_B15") (pintype "bidirectional"))
    )
    (net (code "42") (name "Net-(J7-CMD{slash}DI)") (class "Default")
      (node (ref "J7") (pin "3") (pinfunction "CMD/DI_3") (pintype "bidirectional"))
      (node (ref "R8") (pin "3") (pinfunction "33_3") (pintype "passive"))
      (node (ref "U7") (pin "B16") (pinfunction "MMC0_CMD_B16") (pintype "bidirectional"))
    )
    (net (code "43") (name "Net-(J7-DAT0{slash}DO)") (class "Default")
      (node (ref "J7") (pin "7") (pinfunction "DAT0/DO_7") (pintype "bidirectional"))
      (node (ref "R8") (pin "4") (pinfunction "44_4") (pintype "passive"))
      (node (ref "U7") (pin "A16") (pinfunction "MMC0_DAT0_A16") (pintype "bidirectional"))
    )
    (net (code "44") (name "Net-(J7-DAT1)") (class "Default")
      (node (ref "J7") (pin "8") (pinfunction "DAT1_8") (pintype "bidirectional"))
      (node (ref "R8") (pin "7") (pinfunction "77_7") (pintype "passive"))
      (node (ref "U7") (pin "A15") (pinfunction "MMC0_DAT1_A15") (pintype "bidirectional"))
    )
    (net (code "45") (name "Net-(J7-DAT2)") (class "Default")
      (node (ref "J7") (pin "1") (pinfunction "DAT2_1") (pintype "bidirectional"))
      (node (ref "R8") (pin "2") (pinfunction "22_2") (pintype "passive"))
      (node (ref "U7") (pin "C16") (pinfunction "MMC0_DAT2_C16") (pintype "bidirectional"))
    )
    (net (code "46") (name "Net-(J7-DAT3{slash}CS)") (class "Default")
      (node (ref "J7") (pin "2") (pinfunction "DAT3/CS_2") (pintype "bidirectional"))
      (node (ref "R8") (pin "9") (pinfunction "99_9") (pintype "passive"))
      (node (ref "U7") (pin "C15") (pinfunction "MMC0_DAT3_C15") (pintype "bidirectional"))
    )
    (net (code "47") (name "Net-(J8-NC{slash}TDI)") (class "Default")
      (node (ref "J8") (pin "8") (pinfunction "NC/TDI_8") (pintype "passive"))
      (node (ref "U7") (pin "C1") (pinfunction "TDI_C1") (pintype "bidirectional"))
    )
    (net (code "48") (name "Net-(J8-SWDCLK{slash}TCK)") (class "Default")
      (node (ref "J8") (pin "4") (pinfunction "SWDCLK/TCK_4") (pintype "passive"))
      (node (ref "U7") (pin "D1") (pinfunction "TCK_D1") (pintype "bidirectional"))
    )
    (net (code "49") (name "Net-(J8-SWDIO{slash}TMS)") (class "Default")
      (node (ref "J8") (pin "2") (pinfunction "SWDIO/TMS_2") (pintype "passive"))
      (node (ref "U7") (pin "D2") (pinfunction "TMS_D2") (pintype "bidirectional"))
    )
    (net (code "50") (name "Net-(J8-SWO{slash}TDO)") (class "Default")
      (node (ref "J8") (pin "6") (pinfunction "SWO/TDO_6") (pintype "passive"))
      (node (ref "U7") (pin "C2") (pinfunction "TDO_C2") (pintype "bidirectional"))
    )
    (net (code "51") (name "Net-(J8-~{RESET})") (class "Default")
      (node (ref "J8") (pin "10") (pinfunction "~{RESET}_10") (pintype "passive"))
      (node (ref "JP1") (pin "2") (pinfunction "2_2") (pintype "passive"))
    )
    (net (code "52") (name "Net-(J9-P$1)") (class "Default")
      (node (ref "J9") (pin "1") (pinfunction "P$1_1") (pintype "bidirectional"))
      (node (ref "R86") (pin "2") (pinfunction "2_2") (pintype "passive"))
      (node (ref "R87") (pin "1") (pinfunction "1_1") (pintype "passive"))
    )
    (net (code "53") (name "Net-(JP101-Pad2)") (class "Default")
      (node (ref "JP101") (pin "2") (pinfunction "2_2") (pintype "passive"))
      (node (ref "Q1") (pin "E") (pinfunction "E_E") (pintype "passive"))
      (node (ref "R23") (pin "2") (pinfunction "2_2") (pintype "passive"))
      (node (ref "R28") (pin "2") (pinfunction "2_2") (pintype "passive"))
    )
    (net (code "54") (name "Net-(L1-Pad1)") (class "Default")
      (node (ref "L1") (pin "1") (pinfunction "1_1") (pintype "passive"))
      (node (ref "U15") (pin "14") (pinfunction "SW_14") (pintype "output"))
      (node (ref "U15") (pin "15") (pinfunction "SW_15") (pintype "output"))
    )
    (net (code "55") (name "Net-(L2-Pad1)") (class "Default")
      (node (ref "L2") (pin "1") (pinfunction "1_1") (pintype "passive"))
      (node (ref "U5") (pin "14") (pinfunction "SW_14") (pintype "output"))
      (node (ref "U5") (pin "15") (pinfunction "SW_15") (pintype "output"))
    )
    (net (code "56") (name "Net-(Q3A-G)") (class "Default")
      (node (ref "Q3") (pin "1") (pinfunction "G_1") (pintype "passive"))
      (node (ref "R35") (pin "2") (pinfunction "2_2") (pintype "passive"))
    )
    (net (code "57") (name "Net-(Q3A-S)") (class "Default")
      (node (ref "Q3") (pin "5") (pinfunction "S_5") (pintype "passive"))
      (node (ref "R48") (pin "2") (pinfunction "2_2") (pintype "passive"))
    )
    (net (code "58") (name "Net-(Q3B-G)") (class "Default")
      (node (ref "Q3") (pin "3") (pinfunction "G_3") (pintype "passive"))
      (node (ref "R43") (pin "2") (pinfunction "2_2") (pintype "passive"))
    )
    (net (code "59") (name "Net-(Q3B-S)") (class "Default")
      (node (ref "Q3") (pin "2") (pinfunction "S_2") (pintype "passive"))
      (node (ref "R41") (pin "2") (pinfunction "2_2") (pintype "passive"))
    )
    (net (code "60") (name "Net-(Q4-D)") (class "Default")
      (node (ref "Q4") (pin "3") (pinfunction "D_3") (pintype "passive"))
      (node (ref "Q6") (pin "3") (pinfunction "G_3") (pintype "passive"))
      (node (ref "R52") (pin "1") (pinfunction "1_1") (pintype "passive"))
    )
    (net (code "61") (name "Net-(Q5-S)") (class "Default")
      (node (ref "Q5") (pin "4") (pinfunction "S_4") (pintype "passive"))
      (node (ref "R63") (pin "2") (pinfunction "2_2") (pintype "passive"))
      (node (ref "R64") (pin "2") (pinfunction "2_2") (pintype "passive"))
      (node (ref "U14") (pin "15") (pinfunction "RS-_15") (pintype "passive"))
    )
    (net (code "62") (name "Net-(R9-11)") (class "Default")
      (node (ref "R9") (pin "1") (pinfunction "11_1") (pintype "passive"))
      (node (ref "U3") (pin "B3") (pinfunction "D4_B3") (pintype "input"))
      (node (ref "U7") (pin "T2") (pinfunction "GPMC_AD4_T2") (pintype "bidirectional"))
    )
    (net (code "63") (name "Net-(R9-22)") (class "Default")
      (node (ref "R9") (pin "2") (pinfunction "22_2") (pintype "passive"))
      (node (ref "U3") (pin "B2") (pinfunction "D3_B2") (pintype "input"))
      (node (ref "U7") (pin "T3") (pinfunction "GPMC_AD3_T3") (pintype "bidirectional"))
    )
    (net (code "64") (name "Net-(R9-33)") (class "Default")
      (node (ref "R9") (pin "3") (pinfunction "33_3") (pintype "passive"))
      (node (ref "U3") (pin "A5") (pinfunction "D2_A5") (pintype "input"))
      (node (ref "U7") (pin "R1") (pinfunction "GPMC_AD2_R1") (pintype "bidirectional"))
    )
    (net (code "65") (name "Net-(R9-44)") (class "Default")
      (node (ref "R9") (pin "4") (pinfunction "44_4") (pintype "passive"))
      (node (ref "U3") (pin "B6") (pinfunction "D7_B6") (pintype "input"))
      (node (ref "U7") (pin "R4") (pinfunction "GPMC_AD7_R4") (pintype "bidirectional"))
    )
    (net (code "66") (name "Net-(R9-66)") (class "Default")
      (node (ref "R9") (pin "6") (pinfunction "66_6") (pintype "passive"))
      (node (ref "U3") (pin "M5") (pinfunction "CMD_M5") (pintype "input"))
      (node (ref "U7") (pin "P1") (pinfunction "GPMC_CSN2_P1") (pintype "bidirectional"))
    )
    (net (code "67") (name "Net-(R9-77)") (class "Default")
      (node (ref "R9") (pin "7") (pinfunction "77_7") (pintype "passive"))
      (node (ref "U3") (pin "A3") (pinfunction "D0_A3") (pintype "input"))
      (node (ref "U7") (pin "R3") (pinfunction "GPMC_AD0_R3") (pintype "bidirectional"))
    )
    (net (code "68") (name "Net-(R9-88)") (class "Default")
      (node (ref "R9") (pin "8") (pinfunction "88_8") (pintype "passive"))
      (node (ref "U3") (pin "A4") (pinfunction "D1_A4") (pintype "input"))
      (node (ref "U7") (pin "R2") (pinfunction "GPMC_AD1_R2") (pintype "bidirectional"))
    )
    (net (code "69") (name "Net-(R9-99)") (class "Default")
      (node (ref "R9") (pin "9") (pinfunction "99_9") (pintype "passive"))
      (node (ref "U3") (pin "B4") (pinfunction "D5_B4") (pintype "input"))
      (node (ref "U7") (pin "T1") (pinfunction "GPMC_AD5_T1") (pintype "bidirectional"))
    )
    (net (code "70") (name "Net-(R10-11)") (class "Default")
      (node (ref "R10") (pin "1") (pinfunction "11_1") (pintype "passive"))
      (node (ref "U3") (pin "B5") (pinfunction "D6_B5") (pintype "bidirectional"))
      (node (ref "U7") (pin "P4") (pinfunction "GPMC_AD6_P4") (pintype "bidirectional"))
    )
    (net (code "71") (name "Net-(R10-22)") (class "Default")
      (node (ref "R10") (pin "2") (pinfunction "22_2") (pintype "passive"))
      (node (ref "U3") (pin "K5") (pinfunction "~{RST}_K5") (pintype "input"))
      (node (ref "U7") (pin "R13") (pinfunction "GPMC_A4_R13") (pintype "bidirectional"))
    )
    (net (code "72") (name "Net-(R10-99)") (class "Default")
      (node (ref "R10") (pin "9") (pinfunction "99_9") (pintype "passive"))
      (node (ref "U3") (pin "M6") (pinfunction "SCK_M6") (pintype "input"))
      (node (ref "U7") (pin "P2") (pinfunction "GPMC_CSN1_P2") (pintype "bidirectional"))
    )
    (net (code "73") (name "Net-(R24-11)") (class "Default")
      (node (ref "JP107") (pin "3") (pinfunction "3_3") (pintype "passive"))
      (node (ref "R24") (pin "1") (pinfunction "11_1") (pintype "passive"))
    )
    (net (code "74") (name "Net-(R24-22)") (class "Default")
      (node (ref "R24") (pin "2") (pinfunction "22_2") (pintype "passive"))
      (node (ref "U7") (pin "L1") (pinfunction "LCD_DATA14_L1") (pintype "bidirectional"))
    )
    (net (code "75") (name "Net-(R24-66)") (class "Default")
      (node (ref "JP108") (pin "3") (pinfunction "3_3") (pintype "passive"))
      (node (ref "R24") (pin "6") (pinfunction "66_6") (pintype "passive"))
    )
    (net (code "76") (name "Net-(R24-77)") (class "Default")
      (node (ref "JP109") (pin "3") (pinfunction "3_3") (pintype "passive"))
      (node (ref "R24") (pin "7") (pinfunction "77_7") (pintype "passive"))
    )
    (net (code "77") (name "Net-(R24-88)") (class "Default")
      (node (ref "JP106") (pin "1") (pinfunction "1_1") (pintype "passive"))
      (node (ref "R24") (pin "8") (pinfunction "88_8") (pintype "passive"))
    )
    (net (code "78") (name "Net-(R24-99)") (class "Default")
      (node (ref "JP105") (pin "1") (pinfunction "1_1") (pintype "passive"))
      (node (ref "R24") (pin "9") (pinfunction "99_9") (pintype "passive"))
    )
    (net (code "79") (name "Net-(R25-11)") (class "Default")
      (node (ref "JP107") (pin "1") (pinfunction "1_1") (pintype "passive"))
      (node (ref "R25") (pin "1") (pinfunction "11_1") (pintype "passive"))
    )
    (net (code "80") (name "Net-(R25-22)") (class "Default")
      (node (ref "JP106") (pin "3") (pinfunction "3_3") (pintype "passive"))
      (node (ref "R25") (pin "2") (pinfunction "22_2") (pintype "passive"))
    )
    (net (code "81") (name "Net-(R25-33)") (class "Default")
      (node (ref "JP105") (pin "3") (pinfunction "3_3") (pintype "passive"))
      (node (ref "R25") (pin "3") (pinfunction "33_3") (pintype "passive"))
    )
    (net (code "82") (name "Net-(R25-44)") (class "Default")
      (node (ref "R25") (pin "4") (pinfunction "44_4") (pintype "passive"))
      (node (ref "U7") (pin "H1") (pinfunction "LCD_DATA5_H1") (pintype "bidirectional"))
    )
    (net (code "83") (name "Net-(R25-66)") (class "Default")
      (node (ref "JP109") (pin "1") (pinfunction "1_1") (pintype "passive"))
      (node (ref "R25") (pin "6") (pinfunction "66_6") (pintype "passive"))
    )
    (net (code "84") (name "Net-(R25-77)") (class "Default")
      (node (ref "R25") (pin "7") (pinfunction "77_7") (pintype "passive"))
      (node (ref "U7") (pin "J3") (pinfunction "LCD_DATA6_J3") (pintype "bidirectional"))
    )
    (net (code "85") (name "Net-(R25-99)") (class "Default")
      (node (ref "JP108") (pin "1") (pinfunction "1_1") (pintype "passive"))
      (node (ref "R25") (pin "9") (pinfunction "99_9") (pintype "passive"))
    )
    (net (code "86") (name "Net-(R26-11)") (class "Default")
      (node (ref "R26") (pin "1") (pinfunction "11_1") (pintype "passive"))
      (node (ref "U7") (pin "M3") (pinfunction "LCD_DATA15_M3") (pintype "bidirectional"))
    )
    (net (code "87") (name "Net-(R26-22)") (class "Default")
      (node (ref "R26") (pin "2") (pinfunction "22_2") (pintype "passive"))
      (node (ref "U7") (pin "L3") (pinfunction "LCD_DATA12_L3") (pintype "bidirectional"))
    )
    (net (code "88") (name "Net-(R26-33)") (class "Default")
      (node (ref "R26") (pin "3") (pinfunction "33_3") (pintype "passive"))
      (node (ref "U7") (pin "K2") (pinfunction "LCD_DATA10_K2") (pintype "bidirectional"))
    )
    (net (code "89") (name "Net-(R26-44)") (class "Default")
      (node (ref "R26") (pin "4") (pinfunction "44_4") (pintype "passive"))
      (node (ref "U7") (pin "J1") (pinfunction "LCD_DATA8_J1") (pintype "bidirectional"))
    )
    (net (code "90") (name "Net-(R26-66)") (class "Default")
      (node (ref "R26") (pin "6") (pinfunction "66_6") (pintype "passive"))
      (node (ref "U7") (pin "J2") (pinfunction "LCD_DATA7_J2") (pintype "bidirectional"))
    )
    (net (code "91") (name "Net-(R26-77)") (class "Default")
      (node (ref "R26") (pin "7") (pinfunction "77_7") (pintype "passive"))
      (node (ref "U7") (pin "K3") (pinfunction "LCD_DATA9_K3") (pintype "bidirectional"))
    )
    (net (code "92") (name "Net-(R26-88)") (class "Default")
      (node (ref "R26") (pin "8") (pinfunction "88_8") (pintype "passive"))
      (node (ref "U7") (pin "K1") (pinfunction "LCD_DATA11_K1") (pintype "bidirectional"))
    )
    (net (code "93") (name "Net-(R26-99)") (class "Default")
      (node (ref "R26") (pin "9") (pinfunction "99_9") (pintype "passive"))
      (node (ref "U7") (pin "L2") (pinfunction "LCD_DATA13_L2") (pintype "bidirectional"))
    )
    (net (code "94") (name "Net-(R84-Pad2)") (class "Default")
      (node (ref "R84") (pin "2") (pinfunction "2_2") (pintype "passive"))
      (node (ref "U19") (pin "2") (pinfunction "RFIN_2") (pintype "input"))
      (node (ref "U19") (pin "3") (pinfunction "RFIN_3") (pintype "input"))
      (node (ref "U19") (pin "4") (pinfunction "RFIN_4") (pintype "input"))
    )
    (net (code "95") (name "Net-(R87-Pad2)") (class "Default")
      (node (ref "R87") (pin "2") (pinfunction "2_2") (pintype "passive"))
      (node (ref "R88") (pin "1") (pinfunction "1_1") (pintype "passive"))
    )
    (net (code "96") (name "Net-(TP9-Pad1)") (class "Default")
      (node (ref "TP9") (pin "1") (pinfunction "1_1") (pintype "bidirectional"))
      (node (ref "U7") (pin "F10") (pinfunction "SYS_VDD_1P8V_F10") (pintype "power_in"))
      (node (ref "U7") (pin "G10") (pinfunction "SYS_VDD_1P8V_G10") (pintype "power_in"))
      (node (ref "U7") (pin "H10") (pinfunction "SYS_VDD_1P8V_H10") (pintype "power_in"))
      (node (ref "U7") (pin "H11") (pinfunction "SYS_VDD_1P8V_H11") (pintype "power_in"))
      (node (ref "U7") (pin "J10") (pinfunction "SYS_VDD_1P8V_J10") (pintype "power_in"))
      (node (ref "U7") (pin "J11") (pinfunction "SYS_VDD_1P8V_J11") (pintype "power_in"))
      (node (ref "U7") (pin "K10") (pinfunction "SYS_VDD_1P8V_K10") (pintype "power_in"))
      (node (ref "U7") (pin "L10") (pinfunction "SYS_VDD_1P8V_L10") (pintype "power_in"))
    )
    (net (code "97") (name "Net-(TP145-Pad1)") (class "Default")
      (node (ref "TP145") (pin "1") (pinfunction "1_1") (pintype "bidirectional"))
      (node (ref "U7") (pin "K4") (pinfunction "NC_K4") (pintype "bidirectional"))
    )
    (net (code "98") (name "Net-(TP150-Pad1)") (class "Default")
      (node (ref "TP150") (pin "1") (pinfunction "1_1") (pintype "bidirectional"))
      (node (ref "U7") (pin "J6") (pinfunction "NC_J6") (pintype "bidirectional"))
    )
    (net (code "99") (name "Net-(TP161-Pad1)") (class "Default")
      (node (ref "TP161") (pin "1") (pinfunction "1_1") (pintype "bidirectional"))
      (node (ref "U7") (pin "F11") (pinfunction "SYS_VDD2_3P3V_F11") (pintype "power_in"))
      (node (ref "U7") (pin "G11") (pinfunction "SYS_VDD2_3P3V_G11") (pintype "power_in"))
    )
    (net (code "100") (name "Net-(TP172-Pad1)") (class "Default")
      (node (ref "TP172") (pin "1") (pinfunction "1_1") (pintype "bidirectional"))
      (node (ref "U7") (pin "D12") (pinfunction "NC_D12") (pintype "bidirectional"))
    )
    (net (code "101") (name "Net-(U$1-2)") (class "Default")
      (node (ref "JP107") (pin "2") (pinfunction "2_2") (pintype "passive"))
      (node (ref "U$1") (pin "P$2") (pinfunction "2_P$2") (pintype "passive"))
      (node (ref "U7") (pin "G1") (pinfunction "LCD_DATA2_G1") (pintype "bidirectional"))
    )
    (net (code "102") (name "Net-(U2-BUSPWR)") (class "Default")
      (node (ref "R99") (pin "2") (pinfunction "2_2") (pintype "passive"))
      (node (ref "TP18") (pin "1") (pinfunction "1_1") (pintype "bidirectional"))
      (node (ref "U2") (pin "8") (pinfunction "BUSPWR_8") (pintype "input"))
    )
    (net (code "103") (name "Net-(U2-DM0)") (class "Default")
      (node (ref "U2") (pin "2") (pinfunction "DM0_2") (pintype "bidirectional"))
      (node (ref "U7") (pin "L16") (pinfunction "USB1_DM_L16") (pintype "bidirectional"))
    )
    (net (code "104") (name "Net-(U2-DM1)") (class "Default")
      (node (ref "R77") (pin "2") (pinfunction "2_2") (pintype "passive"))
      (node (ref "U2") (pin "11") (pinfunction "DM1_11") (pintype "bidirectional"))
    )
    (net (code "105") (name "Net-(U2-DM2)") (class "Default")
      (node (ref "R89") (pin "2") (pinfunction "2_2") (pintype "passive"))
      (node (ref "U2") (pin "15") (pinfunction "DM2_15") (pintype "bidirectional"))
    )
    (net (code "106") (name "Net-(U2-DM3)") (class "Default")
      (node (ref "R93") (pin "2") (pinfunction "2_2") (pintype "passive"))
      (node (ref "U2") (pin "19") (pinfunction "DM3_19") (pintype "bidirectional"))
    )
    (net (code "107") (name "Net-(U2-DM4)") (class "Default")
      (node (ref "R101") (pin "2") (pinfunction "2_2") (pintype "passive"))
      (node (ref "U2") (pin "23") (pinfunction "DM4_23") (pintype "bidirectional"))
    )
    (net (code "108") (name "Net-(U2-DP0)") (class "Default")
      (node (ref "U2") (pin "1") (pinfunction "DP0_1") (pintype "bidirectional"))
      (node (ref "U7") (pin "L15") (pinfunction "USB1_DP_L15") (pintype "bidirectional"))
    )
    (net (code "109") (name "Net-(U2-DP1)") (class "Default")
      (node (ref "R79") (pin "2") (pinfunction "2_2") (pintype "passive"))
      (node (ref "U2") (pin "12") (pinfunction "DP1_12") (pintype "bidirectional"))
    )
    (net (code "110") (name "Net-(U2-DP2)") (class "Default")
      (node (ref "R91") (pin "2") (pinfunction "2_2") (pintype "passive"))
      (node (ref "U2") (pin "16") (pinfunction "DP2_16") (pintype "bidirectional"))
    )
    (net (code "111") (name "Net-(U2-DP3)") (class "Default")
      (node (ref "R95") (pin "2") (pinfunction "2_2") (pintype "passive"))
      (node (ref "U2") (pin "20") (pinfunction "DP3_20") (pintype "bidirectional"))
    )
    (net (code "112") (name "Net-(U2-DP4)") (class "Default")
      (node (ref "R100") (pin "2") (pinfunction "2_2") (pintype "passive"))
      (node (ref "U2") (pin "24") (pinfunction "DP4_24") (pintype "bidirectional"))
    )
    (net (code "113") (name "Net-(U2-EECLK)") (class "Default")
      (node (ref "TP20") (pin "1") (pinfunction "1_1") (pintype "bidirectional"))
      (node (ref "U2") (pin "5") (pinfunction "EECLK_5") (pintype "output"))
    )
    (net (code "114") (name "Net-(U2-EEDATA{slash}GANGED)") (class "Default")
      (node (ref "TP19") (pin "1") (pinfunction "1_1") (pintype "bidirectional"))
      (node (ref "U2") (pin "6") (pinfunction "EEDATA/GANGED_6") (pintype "bidirectional"))
    )
    (net (code "115") (name "Net-(U2-SUSPND)") (class "Default")
      (node (ref "TP16") (pin "1") (pinfunction "1_1") (pintype "bidirectional"))
      (node (ref "U2") (pin "32") (pinfunction "SUSPND_32") (pintype "output"))
    )
    (net (code "116") (name "Net-(U2-XTAL1)") (class "Default")
      (node (ref "C63") (pin "1") (pinfunction "1_1") (pintype "passive"))
      (node (ref "U2") (pin "30") (pinfunction "XTAL1_30") (pintype "passive"))
      (node (ref "Y3") (pin "3") (pinfunction "X1_3") (pintype "passive"))
    )
    (net (code "117") (name "Net-(U2-XTAL2)") (class "Default")
      (node (ref "R98") (pin "1") (pinfunction "1_1") (pintype "passive"))
      (node (ref "U2") (pin "29") (pinfunction "XTAL2_29") (pintype "passive"))
    )
    (net (code "118") (name "Net-(U2-~{OVRCUR1})") (class "Default")
      (node (ref "R6") (pin "1") (pinfunction "1_1") (pintype "passive"))
      (node (ref "U2") (pin "10") (pinfunction "~{OVRCUR1}_10") (pintype "input"))
      (node (ref "U9") (pin "3") (pinfunction "~{OC}_3") (pintype "open_collector"))
    )
    (net (code "119") (name "Net-(U2-~{OVRCUR2})") (class "Default")
      (node (ref "R76") (pin "1") (pinfunction "1_1") (pintype "passive"))
      (node (ref "U2") (pin "14") (pinfunction "~{OVRCUR2}_14") (pintype "input"))
      (node (ref "U21") (pin "3") (pinfunction "~{OC}_3") (pintype "open_collector"))
    )
    (net (code "120") (name "Net-(U2-~{OVRCUR3})") (class "Default")
      (node (ref "R7") (pin "1") (pinfunction "1_1") (pintype "passive"))
      (node (ref "U2") (pin "18") (pinfunction "~{OVRCUR3}_18") (pintype "input"))
      (node (ref "U20") (pin "3") (pinfunction "~{OC}_3") (pintype "open_collector"))
    )
    (net (code "121") (name "Net-(U2-~{PWRON1})") (class "Default")
      (node (ref "U2") (pin "9") (pinfunction "~{PWRON1}_9") (pintype "output"))
      (node (ref "U9") (pin "4") (pinfunction "~{EN}_4") (pintype "input"))
    )
    (net (code "122") (name "Net-(U2-~{PWRON2})") (class "Default")
      (node (ref "U2") (pin "13") (pinfunction "~{PWRON2}_13") (pintype "output"))
      (node (ref "U21") (pin "4") (pinfunction "~{EN}_4") (pintype "input"))
    )
    (net (code "123") (name "Net-(U2-~{PWRON3})") (class "Default")
      (node (ref "U2") (pin "17") (pinfunction "~{PWRON3}_17") (pintype "output"))
      (node (ref "U20") (pin "4") (pinfunction "~{EN}_4") (pintype "input"))
    )
    (net (code "124") (name "Net-(U2-~{RESET})") (class "Default")
      (node (ref "R97") (pin "2") (pinfunction "2_2") (pintype "passive"))
      (node (ref "TP17") (pin "1") (pinfunction "1_1") (pintype "bidirectional"))
      (node (ref "U2") (pin "4") (pinfunction "~{RESET}_4") (pintype "input"))
    )
    (net (code "125") (name "Net-(U3-VDDI)") (class "Default")
      (node (ref "C10") (pin "1") (pinfunction "1_1") (pintype "passive"))
      (node (ref "C12") (pin "1") (pinfunction "1_1") (pintype "passive"))
      (node (ref "U3") (pin "C2") (pinfunction "VDDI_C2") (pintype "power_in"))
    )
    (net (code "126") (name "Net-(U5-PG)") (class "Default")
      (node (ref "TP6") (pin "1") (pinfunction "1_1") (pintype "passive"))
      (node (ref "U5") (pin "13") (pinfunction "PG_13") (pintype "open_collector"))
    )
    (net (code "127") (name "Net-(U5-SYNC)") (class "Default")
      (node (ref "R12") (pin "1") (pinfunction "1_1") (pintype "passive"))
      (node (ref "R14") (pin "2") (pinfunction "2_2") (pintype "passive"))
      (node (ref "TP5") (pin "1") (pinfunction "1_1") (pintype "passive"))
      (node (ref "U5") (pin "5") (pinfunction "SYNC_5") (pintype "input"))
    )
    (net (code "128") (name "Net-(U6-Y)") (class "Default")
      (node (ref "U6") (pin "4") (pinfunction "Y_4") (pintype "output"))
      (node (ref "U8") (pin "6") (pinfunction "EN_6") (pintype "input"))
    )
    (net (code "129") (name "Net-(U7A-EEPROM_WP)") (class "Default")
      (node (ref "R75") (pin "2") (pinfunction "2_2") (pintype "passive"))
      (node (ref "U7") (pin "M2") (pinfunction "EEPROM_WP_M2") (pintype "bidirectional"))
    )
    (net (code "130") (name "Net-(U7A-EXTINTN)") (class "Default")
      (node (ref "TP167") (pin "1") (pinfunction "1_1") (pintype "bidirectional"))
      (node (ref "U7") (pin "D4") (pinfunction "EXTINTN_D4") (pintype "bidirectional"))
      (node (ref "U7") (pin "E4") (pinfunction "PMIC_NINT_E4") (pintype "output"))
    )
    (net (code "131") (name "Net-(U7A-EXT_WAKEUP)") (class "Default")
      (node (ref "TP140") (pin "1") (pinfunction "1_1") (pintype "bidirectional"))
      (node (ref "U7") (pin "L4") (pinfunction "PMIC_NWAKEUP_L4") (pintype "output"))
      (node (ref "U7") (pin "M4") (pinfunction "EXT_WAKEUP_M4") (pintype "bidirectional"))
    )
    (net (code "132") (name "Net-(U7A-I2C0_SCL)") (class "Default")
      (node (ref "R73") (pin "2") (pinfunction "2_2") (pintype "passive"))
      (node (ref "U7") (pin "C10") (pinfunction "I2C0_SCL_C10") (pintype "bidirectional"))
      (node (ref "U7") (pin "D10") (pinfunction "PMIC_SCL_D10") (pintype "bidirectional"))
    )
    (net (code "133") (name "Net-(U7A-I2C0_SDA)") (class "Default")
      (node (ref "R74") (pin "2") (pinfunction "2_2") (pintype "passive"))
      (node (ref "U7") (pin "C11") (pinfunction "I2C0_SDA_C11") (pintype "bidirectional"))
      (node (ref "U7") (pin "D11") (pinfunction "PMIC_SDA_D11") (pintype "bidirectional"))
    )
    (net (code "134") (name "Net-(U7A-PMIC_BAT_SENSE)") (class "Default")
      (node (ref "TP130") (pin "1") (pinfunction "1_1") (pintype "bidirectional"))
      (node (ref "TP4") (pin "1") (pinfunction "1_1") (pintype "bidirectional"))
      (node (ref "U7") (pin "N7") (pinfunction "PMIC_BAT_SENSE_N7") (pintype "bidirectional"))
      (node (ref "U7") (pin "P8") (pinfunction "VIN_BAT_P8") (pintype "power_in"))
      (node (ref "U7") (pin "R8") (pinfunction "VIN_BAT_R8") (pintype "power_in"))
      (node (ref "U7") (pin "T8") (pinfunction "VIN_BAT_T8") (pintype "power_in"))
    )
    (net (code "135") (name "Net-(U7A-PMIC_LDO_PGOOD)") (class "Default")
      (node (ref "TP132") (pin "1") (pinfunction "1_1") (pintype "bidirectional"))
      (node (ref "U7") (pin "N4") (pinfunction "PMIC_LDO_PGOOD_N4") (pintype "output"))
      (node (ref "U7") (pin "N5") (pinfunction "RTC_PWRONRSTN_N5") (pintype "bidirectional"))
    )
    (net (code "136") (name "Net-(U7A-PMIC_NRESET)") (class "Default")
      (node (ref "TP136") (pin "1") (pinfunction "1_1") (pintype "bidirectional"))
      (node (ref "U7") (pin "M13") (pinfunction "PMIC_NRESET_M13") (pintype "bidirectional"))
    )
    (net (code "137") (name "Net-(U7A-PMIC_PB_IN)") (class "Default")
      (node (ref "TP102") (pin "1") (pinfunction "1_1") (pintype "bidirectional"))
      (node (ref "U7") (pin "T11") (pinfunction "PMIC_PB_IN_T11") (pintype "bidirectional"))
    )
    (net (code "138") (name "Net-(U7A-PMIC_POWER_EN)") (class "Default")
      (node (ref "TP121") (pin "1") (pinfunction "1_1") (pintype "bidirectional"))
      (node (ref "U7") (pin "N10") (pinfunction "PMIC_POWER_EN_N10") (pintype "output"))
      (node (ref "U7") (pin "N11") (pinfunction "PMIC_PWR_EN_N11") (pintype "input"))
    )
    (net (code "139") (name "Net-(U7A-PMIC_TS)") (class "Default")
      (node (ref "TP129") (pin "1") (pinfunction "1_1") (pintype "bidirectional"))
      (node (ref "U7") (pin "N6") (pinfunction "PMIC_TS_N6") (pintype "bidirectional"))
    )
    (net (code "140") (name "Net-(U7A-RTC_KALDO_ENN)") (class "Default")
      (node (ref "R15") (pin "2") (pinfunction "2_2") (pintype "passive"))
      (node (ref "U7") (pin "M16") (pinfunction "RTC_KALDO_ENN_M16") (pintype "bidirectional"))
    )
    (net (code "141") (name "Net-(U7B-AIN0)") (class "Default")
      (node (ref "TP39") (pin "1") (pinfunction "1_1") (pintype "bidirectional"))
      (node (ref "U7") (pin "A8") (pinfunction "AIN0_A8") (pintype "bidirectional"))
    )
    (net (code "142") (name "Net-(U7B-AIN1)") (class "Default")
      (node (ref "TP38") (pin "1") (pinfunction "1_1") (pintype "bidirectional"))
      (node (ref "U7") (pin "B8") (pinfunction "AIN1_B8") (pintype "bidirectional"))
    )
    (net (code "143") (name "Net-(U7B-AIN2)") (class "Default")
      (node (ref "TP181") (pin "1") (pinfunction "1_1") (pintype "bidirectional"))
      (node (ref "U7") (pin "B6") (pinfunction "AIN2_B6") (pintype "bidirectional"))
    )
    (net (code "144") (name "Net-(U7B-AIN3)") (class "Default")
      (node (ref "TP175") (pin "1") (pinfunction "1_1") (pintype "bidirectional"))
      (node (ref "U7") (pin "C6") (pinfunction "AIN3_C6") (pintype "bidirectional"))
    )
    (net (code "145") (name "Net-(U7B-AIN4)") (class "Default")
      (node (ref "TP176") (pin "1") (pinfunction "1_1") (pintype "bidirectional"))
      (node (ref "U7") (pin "C7") (pinfunction "AIN4_C7") (pintype "bidirectional"))
    )
    (net (code "146") (name "Net-(U7B-AIN5)") (class "Default")
      (node (ref "TP169") (pin "1") (pinfunction "1_1") (pintype "bidirectional"))
      (node (ref "U7") (pin "C8") (pinfunction "AIN5_C8") (pintype "bidirectional"))
    )
    (net (code "147") (name "Net-(U7B-AIN7)") (class "Default")
      (node (ref "U7") (pin "D6") (pinfunction "PMIC_MUX_OUT_D6") (pintype "bidirectional"))
      (node (ref "U7") (pin "D7") (pinfunction "AIN7_D7") (pintype "bidirectional"))
    )
    (net (code "148") (name "Net-(U7B-EMU0)") (class "Default")
      (node (ref "R22") (pin "1") (pinfunction "1_1") (pintype "passive"))
      (node (ref "U7") (pin "E2") (pinfunction "EMU0_E2") (pintype "bidirectional"))
    )
    (net (code "149") (name "Net-(U7B-EMU1)") (class "Default")
      (node (ref "R20") (pin "1") (pinfunction "1_1") (pintype "passive"))
      (node (ref "U7") (pin "E3") (pinfunction "EMU1_E3") (pintype "bidirectional"))
    )
    (net (code "150") (name "Net-(U7B-OSC1_GND)") (class "Default")
      (node (ref "C29") (pin "2") (pinfunction "2_2") (pintype "passive"))
      (node (ref "C30") (pin "2") (pinfunction "2_2") (pintype "passive"))
      (node (ref "U7") (pin "B5") (pinfunction "OSC1_GND_B5") (pintype "bidirectional"))
    )
    (net (code "151") (name "Net-(U7B-OSC1_IN)") (class "Default")
      (node (ref "C30") (pin "1") (pinfunction "1_1") (pintype "passive"))
      (node (ref "R27") (pin "2") (pinfunction "2_2") (pintype "passive"))
      (node (ref "U7") (pin "A6") (pinfunction "OSC1_IN_A6") (pintype "bidirectional"))
      (node (ref "Y2") (pin "P$2") (pinfunction "P$2_P$2") (pintype "passive"))
    )
    (net (code "152") (name "Net-(U7B-OSC1_OUT)") (class "Default")
      (node (ref "C29") (pin "1") (pinfunction "1_1") (pintype "passive"))
      (node (ref "R27") (pin "1") (pinfunction "1_1") (pintype "passive"))
      (node (ref "U7") (pin "A5") (pinfunction "OSC1_OUT_A5") (pintype "bidirectional"))
      (node (ref "Y2") (pin "P$1") (pinfunction "P$1_P$1") (pintype "passive"))
    )
    (net (code "153") (name "Net-(U7B-TRSTN)") (class "Default")
      (node (ref "R19") (pin "2") (pinfunction "2_2") (pintype "passive"))
      (node (ref "TP31") (pin "1") (pinfunction "1_1") (pintype "bidirectional"))
      (node (ref "U7") (pin "D3") (pinfunction "TRSTN_D3") (pintype "bidirectional"))
    )
    (net (code "154") (name "Net-(U7B-USB0_CE)") (class "Default")
      (node (ref "TP141") (pin "1") (pinfunction "1_1") (pintype "bidirectional"))
      (node (ref "U7") (pin "K13") (pinfunction "USB0_CE_K13") (pintype "bidirectional"))
    )
    (net (code "155") (name "Net-(U7B-USB0_DRVVBUS)") (class "Default")
      (node (ref "TP139") (pin "1") (pinfunction "1_1") (pintype "bidirectional"))
      (node (ref "U7") (pin "J15") (pinfunction "USB0_DRVVBUS_J15") (pintype "bidirectional"))
    )
    (net (code "156") (name "Net-(U7B-USB0_ID)") (class "Default")
      (node (ref "TP138") (pin "1") (pinfunction "1_1") (pintype "bidirectional"))
      (node (ref "U7") (pin "K14") (pinfunction "USB0_ID_K14") (pintype "bidirectional"))
    )
    (net (code "157") (name "Net-(U7B-USB1_CE)") (class "Default")
      (node (ref "TP144") (pin "1") (pinfunction "1_1") (pintype "bidirectional"))
      (node (ref "U7") (pin "L13") (pinfunction "USB1_CE_L13") (pintype "bidirectional"))
    )
    (net (code "158") (name "Net-(U7B-USB1_DRVVBUS)") (class "Default")
      (node (ref "TP12") (pin "1") (pinfunction "1_1") (pintype "bidirectional"))
      (node (ref "U7") (pin "M14") (pinfunction "USB1_DRVVBUS_M14") (pintype "bidirectional"))
    )
    (net (code "159") (name "Net-(U7B-USB1_ID)") (class "Default")
      (node (ref "JP100") (pin "1") (pinfunction "1_1") (pintype "passive"))
      (node (ref "U7") (pin "L14") (pinfunction "USB1_ID_L14") (pintype "bidirectional"))
    )
    (net (code "160") (name "Net-(U7C-ECAP0_IN_PWM0_OUT)") (class "Default")
      (node (ref "TP180") (pin "1") (pinfunction "1_1") (pintype "bidirectional"))
      (node (ref "U7") (pin "C5") (pinfunction "ECAP0_IN_PWM0_OUT_C5") (pintype "bidirectional"))
    )
    (net (code "161") (name "Net-(U7C-GPMC_A0)") (class "Default")
      (node (ref "TP100") (pin "1") (pinfunction "1_1") (pintype "bidirectional"))
      (node (ref "U7") (pin "T12") (pinfunction "GPMC_A0_T12") (pintype "bidirectional"))
    )
    (net (code "162") (name "Net-(U7C-GPMC_A1)") (class "Default")
      (node (ref "TP118") (pin "1") (pinfunction "1_1") (pintype "bidirectional"))
      (node (ref "U7") (pin "R12") (pinfunction "GPMC_A1_R12") (pintype "bidirectional"))
    )
    (net (code "163") (name "Net-(U7C-GPMC_A2)") (class "Default")
      (node (ref "TP126") (pin "1") (pinfunction "1_1") (pintype "bidirectional"))
      (node (ref "U7") (pin "P12") (pinfunction "GPMC_A2_P12") (pintype "bidirectional"))
    )
    (net (code "164") (name "Net-(U7C-GPMC_A3)") (class "Default")
      (node (ref "TP101") (pin "1") (pinfunction "1_1") (pintype "bidirectional"))
      (node (ref "U7") (pin "T13") (pinfunction "GPMC_A3_T13") (pintype "bidirectional"))
    )
    (net (code "165") (name "Net-(U7C-GPMC_A5)") (class "Default")
      (node (ref "R2") (pin "1") (pinfunction "1_1") (pintype "passive"))
      (node (ref "U7") (pin "P13") (pinfunction "GPMC_A5_P13") (pintype "bidirectional"))
    )
    (net (code "166") (name "Net-(U7C-GPMC_A6)") (class "Default")
      (node (ref "R3") (pin "1") (pinfunction "1_1") (pintype "passive"))
      (node (ref "U7") (pin "T14") (pinfunction "GPMC_A6_T14") (pintype "bidirectional"))
    )
    (net (code "167") (name "Net-(U7C-GPMC_A7)") (class "Default")
      (node (ref "R4") (pin "1") (pinfunction "1_1") (pintype "passive"))
      (node (ref "U7") (pin "R14") (pinfunction "GPMC_A7_R14") (pintype "bidirectional"))
    )
    (net (code "168") (name "Net-(U7C-GPMC_A8)") (class "Default")
      (node (ref "R5") (pin "1") (pinfunction "1_1") (pintype "passive"))
      (node (ref "U7") (pin "P14") (pinfunction "GPMC_A8_P14") (pintype "bidirectional"))
    )
    (net (code "169") (name "Net-(U7C-GPMC_A9)") (class "Default")
      (node (ref "TP108") (pin "1") (pinfunction "1_1") (pintype "bidirectional"))
      (node (ref "U7") (pin "T15") (pinfunction "GPMC_A9_T15") (pintype "bidirectional"))
    )
    (net (code "170") (name "Net-(U7C-GPMC_A10)") (class "Default")
      (node (ref "TP117") (pin "1") (pinfunction "1_1") (pintype "bidirectional"))
      (node (ref "U7") (pin "R15") (pinfunction "GPMC_A10_R15") (pintype "bidirectional"))
    )
    (net (code "171") (name "Net-(U7C-GPMC_A11)") (class "Default")
      (node (ref "TP103") (pin "1") (pinfunction "1_1") (pintype "bidirectional"))
      (node (ref "U7") (pin "T16") (pinfunction "GPMC_A11_T16") (pintype "bidirectional"))
    )
    (net (code "172") (name "Net-(U7C-GPMC_AD8)") (class "Default")
      (node (ref "TP104") (pin "1") (pinfunction "1_1") (pintype "bidirectional"))
      (node (ref "U7") (pin "T4") (pinfunction "GPMC_AD8_T4") (pintype "bidirectional"))
    )
    (net (code "173") (name "Net-(U7C-GPMC_AD9)") (class "Default")
      (node (ref "TP123") (pin "1") (pinfunction "1_1") (pintype "bidirectional"))
      (node (ref "U7") (pin "P5") (pinfunction "GPMC_AD9_P5") (pintype "bidirectional"))
    )
    (net (code "174") (name "Net-(U7C-GPMC_AD10)") (class "Default")
      (node (ref "TP115") (pin "1") (pinfunction "1_1") (pintype "bidirectional"))
      (node (ref "U7") (pin "R5") (pinfunction "GPMC_AD10_R5") (pintype "bidirectional"))
    )
    (net (code "175") (name "Net-(U7C-GPMC_AD11)") (class "Default")
      (node (ref "TP105") (pin "1") (pinfunction "1_1") (pintype "bidirectional"))
      (node (ref "U7") (pin "T5") (pinfunction "GPMC_AD11_T5") (pintype "bidirectional"))
    )
    (net (code "176") (name "Net-(U7C-GPMC_AD12)") (class "Default")
      (node (ref "TP124") (pin "1") (pinfunction "1_1") (pintype "bidirectional"))
      (node (ref "U7") (pin "P6") (pinfunction "GPMC_AD12_P6") (pintype "bidirectional"))
    )
    (net (code "177") (name "Net-(U7C-GPMC_AD13)") (class "Default")
      (node (ref "TP120") (pin "1") (pinfunction "1_1") (pintype "bidirectional"))
      (node (ref "U7") (pin "R6") (pinfunction "GPMC_AD13_R6") (pintype "bidirectional"))
    )
    (net (code "178") (name "Net-(U7C-GPMC_ADVN_ALE)") (class "Default")
      (node (ref "TP134") (pin "1") (pinfunction "1_1") (pintype "bidirectional"))
      (node (ref "U7") (pin "M1") (pinfunction "GPMC_ADVN_ALE_M1") (pintype "bidirectional"))
    )
    (net (code "179") (name "Net-(U7C-GPMC_BEN0_CLE)") (class "Default")
      (node (ref "TP131") (pin "1") (pinfunction "1_1") (pintype "bidirectional"))
      (node (ref "U7") (pin "N3") (pinfunction "GPMC_BEN0_CLE_N3") (pintype "bidirectional"))
    )
    (net (code "180") (name "Net-(U7C-GPMC_BEN1)") (class "Default")
      (node (ref "TP125") (pin "1") (pinfunction "1_1") (pintype "bidirectional"))
      (node (ref "U7") (pin "N14") (pinfunction "GPMC_BEN1_N14") (pintype "bidirectional"))
    )
    (net (code "181") (name "Net-(U7C-GPMC_CLK)") (class "Default")
      (node (ref "TP106") (pin "1") (pinfunction "1_1") (pintype "bidirectional"))
      (node (ref "U7") (pin "T7") (pinfunction "GPMC_CLK_T7") (pintype "bidirectional"))
    )
    (net (code "182") (name "Net-(U7C-GPMC_CSN0)") (class "Default")
      (node (ref "TP122") (pin "1") (pinfunction "1_1") (pintype "bidirectional"))
      (node (ref "U7") (pin "P3") (pinfunction "GPMC_CSN0_P3") (pintype "bidirectional"))
    )
    (net (code "183") (name "Net-(U7C-GPMC_CSN3)") (class "Default")
      (node (ref "TP107") (pin "1") (pinfunction "1_1") (pintype "bidirectional"))
      (node (ref "U7") (pin "R7") (pinfunction "GPMC_CSN3_R7") (pintype "bidirectional"))
    )
    (net (code "184") (name "Net-(U7C-GPMC_OEN_REN)") (class "Default")
      (node (ref "TP128") (pin "1") (pinfunction "1_1") (pintype "bidirectional"))
      (node (ref "U7") (pin "N1") (pinfunction "GPMC_OEN_REN_N1") (pintype "bidirectional"))
    )
    (net (code "185") (name "Net-(U7C-GPMC_WAIT0)") (class "Default")
      (node (ref "TP114") (pin "1") (pinfunction "1_1") (pintype "bidirectional"))
      (node (ref "U7") (pin "P15") (pinfunction "GPMC_WAIT0_P15") (pintype "bidirectional"))
    )
    (net (code "186") (name "Net-(U7C-GPMC_WEN)") (class "Default")
      (node (ref "TP127") (pin "1") (pinfunction "1_1") (pintype "bidirectional"))
      (node (ref "U7") (pin "N2") (pinfunction "GPMC_WEN_N2") (pintype "bidirectional"))
    )
    (net (code "187") (name "Net-(U7C-GPMC_WPN)") (class "Default")
      (node (ref "TP111") (pin "1") (pinfunction "1_1") (pintype "bidirectional"))
      (node (ref "U7") (pin "R16") (pinfunction "GPMC_WPN_R16") (pintype "bidirectional"))
    )
    (net (code "188") (name "Net-(U7C-UART0_CTSN)") (class "Default")
      (node (ref "TP177") (pin "1") (pinfunction "1_1") (pintype "bidirectional"))
      (node (ref "U7") (pin "C12") (pinfunction "UART0_CTSN_C12") (pintype "bidirectional"))
    )
    (net (code "189") (name "Net-(U7C-UART0_RTSN)") (class "Default")
      (node (ref "TP178") (pin "1") (pinfunction "1_1") (pintype "bidirectional"))
      (node (ref "U7") (pin "C13") (pinfunction "UART0_RTSN_C13") (pintype "bidirectional"))
    )
    (net (code "190") (name "Net-(U7C-XDMA_EVENT_INTR0)") (class "Default")
      (node (ref "TP30") (pin "1") (pinfunction "1_1") (pintype "bidirectional"))
      (node (ref "U7") (pin "A4") (pinfunction "XDMA_EVENT_INTR0_A4") (pintype "bidirectional"))
    )
    (net (code "191") (name "Net-(U7D-LCD_AC_BIAS_EN)") (class "Default")
      (node (ref "TP159") (pin "1") (pinfunction "1_1") (pintype "bidirectional"))
      (node (ref "U7") (pin "E1") (pinfunction "LCD_AC_BIAS_EN_E1") (pintype "bidirectional"))
    )
    (net (code "192") (name "Net-(U7D-LCD_DATA0)") (class "Default")
      (node (ref "JP105") (pin "2") (pinfunction "2_2") (pintype "passive"))
      (node (ref "U7") (pin "G3") (pinfunction "LCD_DATA0_G3") (pintype "bidirectional"))
    )
    (net (code "193") (name "Net-(U7D-LCD_DATA1)") (class "Default")
      (node (ref "JP106") (pin "2") (pinfunction "2_2") (pintype "passive"))
      (node (ref "U7") (pin "G2") (pinfunction "LCD_DATA1_G2") (pintype "bidirectional"))
    )
    (net (code "194") (name "Net-(U7D-LCD_DATA3)") (class "Default")
      (node (ref "JP108") (pin "2") (pinfunction "2_2") (pintype "passive"))
      (node (ref "U7") (pin "H3") (pinfunction "LCD_DATA3_H3") (pintype "bidirectional"))
    )
    (net (code "195") (name "Net-(U7D-LCD_DATA4)") (class "Default")
      (node (ref "JP109") (pin "2") (pinfunction "2_2") (pintype "passive"))
      (node (ref "U7") (pin "H2") (pinfunction "LCD_DATA4_H2") (pintype "bidirectional"))
    )
    (net (code "196") (name "Net-(U7D-LCD_HSYNC)") (class "Default")
      (node (ref "TP152") (pin "1") (pinfunction "1_1") (pintype "bidirectional"))
      (node (ref "U7") (pin "F2") (pinfunction "LCD_HSYNC_F2") (pintype "bidirectional"))
    )
    (net (code "197") (name "Net-(U7D-LCD_PCLK)") (class "Default")
      (node (ref "TP162") (pin "1") (pinfunction "1_1") (pintype "bidirectional"))
      (node (ref "U7") (pin "F1") (pinfunction "LCD_PCLK_F1") (pintype "bidirectional"))
    )
    (net (code "198") (name "Net-(U7D-LCD_VSYNC)") (class "Default")
      (node (ref "TP153") (pin "1") (pinfunction "1_1") (pintype "bidirectional"))
      (node (ref "U7") (pin "F3") (pinfunction "LCD_VSYNC_F3") (pintype "bidirectional"))
    )
    (net (code "199") (name "Net-(U7D-MDC)") (class "Default")
      (node (ref "TP174") (pin "1") (pinfunction "1_1") (pintype "bidirectional"))
      (node (ref "U7") (pin "D13") (pinfunction "MDC_D13") (pintype "bidirectional"))
    )
    (net (code "200") (name "Net-(U7D-MDIO)") (class "Default")
      (node (ref "TP158") (pin "1") (pinfunction "1_1") (pintype "bidirectional"))
      (node (ref "U7") (pin "E13") (pinfunction "MDIO_E13") (pintype "bidirectional"))
    )
    (net (code "201") (name "Net-(U7D-MII1_TXD0)") (class "Default")
      (node (ref "TP137") (pin "1") (pinfunction "1_1") (pintype "bidirectional"))
      (node (ref "U7") (pin "H15") (pinfunction "MII1_TXD0_H15") (pintype "bidirectional"))
    )
    (net (code "202") (name "Net-(U7D-MII1_TXD1)") (class "Default")
      (node (ref "TP149") (pin "1") (pinfunction "1_1") (pintype "bidirectional"))
      (node (ref "U7") (pin "H14") (pinfunction "MII1_TXD1_H14") (pintype "bidirectional"))
    )
    (net (code "203") (name "Net-(U7D-MII1_TXD2)") (class "Default")
      (node (ref "TP135") (pin "1") (pinfunction "1_1") (pintype "bidirectional"))
      (node (ref "U7") (pin "G16") (pinfunction "MII1_TXD2_G16") (pintype "bidirectional"))
    )
    (net (code "204") (name "Net-(U7D-MII1_TX_EN)") (class "Default")
      (node (ref "TP148") (pin "1") (pinfunction "1_1") (pintype "bidirectional"))
      (node (ref "U7") (pin "G14") (pinfunction "MII1_TX_EN_G14") (pintype "bidirectional"))
    )
    (net (code "205") (name "Net-(U7D-RMII1_REF_CLK)") (class "Default")
      (node (ref "TP143") (pin "1") (pinfunction "1_1") (pintype "bidirectional"))
      (node (ref "U7") (pin "J14") (pinfunction "RMII1_REF_CLK_J14") (pintype "bidirectional"))
    )
    (net (code "206") (name "Net-(U7F-CAP_VDD_RTC)") (class "Default")
      (node (ref "TP173") (pin "1") (pinfunction "1_1") (pintype "bidirectional"))
      (node (ref "U7") (pin "D5") (pinfunction "CAP_VDD_RTC_D5") (pintype "bidirectional"))
    )
    (net (code "207") (name "Net-(U7F-VDDS_DDR)") (class "Default")
      (node (ref "TP156") (pin "1") (pinfunction "1_1") (pintype "bidirectional"))
      (node (ref "U7") (pin "F4") (pinfunction "VDDS_DDR_F4") (pintype "bidirectional"))
    )
    (net (code "208") (name "Net-(U7F-VDDS_PLL)") (class "Default")
      (node (ref "TP166") (pin "1") (pinfunction "1_1") (pintype "bidirectional"))
      (node (ref "U7") (pin "G13") (pinfunction "VDDS_PLL_G13") (pintype "bidirectional"))
    )
    (net (code "209") (name "Net-(U7F-VDD_CORE)") (class "Default")
      (node (ref "TP154") (pin "1") (pinfunction "1_1") (pintype "bidirectional"))
      (node (ref "U7") (pin "G4") (pinfunction "VDD_CORE_G4") (pintype "bidirectional"))
    )
    (net (code "210") (name "Net-(U7F-VDD_MPU)") (class "Default")
      (node (ref "TP160") (pin "1") (pinfunction "1_1") (pintype "bidirectional"))
      (node (ref "U7") (pin "F13") (pinfunction "VDD_MPU_F13") (pintype "bidirectional"))
    )
    (net (code "211") (name "Net-(U7F-VPP)") (class "Default")
      (node (ref "TP157") (pin "1") (pinfunction "1_1") (pintype "bidirectional"))
      (node (ref "U7") (pin "H6") (pinfunction "VPP_H6") (pintype "bidirectional"))
    )
    (net (code "212") (name "Net-(U9-OUT)") (class "Default")
      (node (ref "C27") (pin "1") (pinfunction "1_1") (pintype "passive"))
      (node (ref "C7") (pin "1") (pinfunction "1_1") (pintype "passive"))
      (node (ref "FB3") (pin "1") (pinfunction "1_1") (pintype "passive"))
      (node (ref "U9") (pin "1") (pinfunction "OUT_1") (pintype "output"))
    )
    (net (code "213") (name "Net-(U10-ANODE)") (class "Default")
      (node (ref "JP104") (pin "2") (pinfunction "2_2") (pintype "passive"))
      (node (ref "Q1") (pin "C") (pinfunction "C_C") (pintype "passive"))
      (node (ref "R31") (pin "1") (pinfunction "1_1") (pintype "passive"))
      (node (ref "U10") (pin "3") (pinfunction "ANODE_3") (pintype "bidirectional"))
    )
    (net (code "214") (name "Net-(U10-CATHODE)") (class "Default")
      (node (ref "Q1") (pin "B") (pinfunction "B_B") (pintype "passive"))
      (node (ref "R23") (pin "1") (pinfunction "1_1") (pintype "passive"))
      (node (ref "U10") (pin "2") (pinfunction "CATHODE_2") (pintype "bidirectional"))
    )
    (net (code "215") (name "Net-(U10-REF)") (class "Default")
      (node (ref "R28") (pin "1") (pinfunction "1_1") (pintype "passive"))
      (node (ref "R31") (pin "2") (pinfunction "2_2") (pintype "passive"))
      (node (ref "U10") (pin "1") (pinfunction "REF_1") (pintype "bidirectional"))
    )
    (net (code "216") (name "Net-(U11-RXD)") (class "Default")
      (node (ref "U11") (pin "4") (pinfunction "RXD_4") (pintype "output"))
      (node (ref "U7") (pin "B11") (pinfunction "UART1_TXD_B11") (pintype "bidirectional"))
    )
    (net (code "217") (name "Net-(U11-S)") (class "Default")
      (node (ref "TP40") (pin "1") (pinfunction "1_1") (pintype "bidirectional"))
      (node (ref "U11") (pin "8") (pinfunction "S_8") (pintype "input"))
    )
    (net (code "218") (name "Net-(U11-SHDN)") (class "Default")
      (node (ref "TP35") (pin "1") (pinfunction "1_1") (pintype "bidirectional"))
      (node (ref "U11") (pin "5") (pinfunction "SHDN_5") (pintype "input"))
    )
    (net (code "219") (name "Net-(U11-TXD)") (class "Default")
      (node (ref "U11") (pin "1") (pinfunction "TXD_1") (pintype "input"))
      (node (ref "U7") (pin "A11") (pinfunction "UART1_RXD_A11") (pintype "bidirectional"))
    )
    (net (code "220") (name "Net-(U12-INP)") (class "Default")
      (node (ref "C32") (pin "1") (pinfunction "1_1") (pintype "passive"))
      (node (ref "R36") (pin "1") (pinfunction "1_1") (pintype "passive"))
      (node (ref "R37") (pin "1") (pinfunction "1_1") (pintype "passive"))
      (node (ref "U12") (pin "1") (pinfunction "INP_1") (pintype "input"))
    )
    (net (code "221") (name "Net-(U12-OUT)") (class "Default")
      (node (ref "R35") (pin "1") (pinfunction "1_1") (pintype "passive"))
      (node (ref "TP44") (pin "1") (pinfunction "1_1") (pintype "passive"))
      (node (ref "U12") (pin "4") (pinfunction "OUT_4") (pintype "output"))
    )
    (net (code "222") (name "Net-(U13-INP)") (class "Default")
      (node (ref "C35") (pin "1") (pinfunction "1_1") (pintype "passive"))
      (node (ref "R44") (pin "1") (pinfunction "1_1") (pintype "passive"))
      (node (ref "R45") (pin "1") (pinfunction "1_1") (pintype "passive"))
      (node (ref "U13") (pin "1") (pinfunction "INP_1") (pintype "input"))
    )
    (net (code "223") (name "Net-(U13-OUT)") (class "Default")
      (node (ref "R43") (pin "1") (pinfunction "1_1") (pintype "passive"))
      (node (ref "TP43") (pin "1") (pinfunction "1_1") (pintype "passive"))
      (node (ref "U13") (pin "4") (pinfunction "OUT_4") (pintype "output"))
    )
    (net (code "224") (name "Net-(U14-CIN1+)") (class "Default")
      (node (ref "R50") (pin "1") (pinfunction "1_1") (pintype "passive"))
      (node (ref "R51") (pin "2") (pinfunction "2_2") (pintype "passive"))
      (node (ref "TP57") (pin "1") (pinfunction "1_1") (pintype "passive"))
      (node (ref "U14") (pin "10") (pinfunction "CIN1+_10") (pintype "input"))
    )
    (net (code "225") (name "Net-(U14-CIN1-)") (class "Default")
      (node (ref "R42") (pin "2") (pinfunction "2_2") (pintype "passive"))
      (node (ref "R47") (pin "1") (pinfunction "1_1") (pintype "passive"))
      (node (ref "TP47") (pin "1") (pinfunction "1_1") (pintype "passive"))
      (node (ref "U14") (pin "11") (pinfunction "CIN1-_11") (pintype "input"))
    )
    (net (code "226") (name "Net-(U14-CIN2+)") (class "Default")
      (node (ref "R47") (pin "2") (pinfunction "2_2") (pintype "passive"))
      (node (ref "U14") (pin "12") (pinfunction "REF_12") (pintype "output"))
      (node (ref "U14") (pin "8") (pinfunction "CIN2+_8") (pintype "input"))
    )
    (net (code "227") (name "Net-(U14-INHIBIT)") (class "Default")
      (node (ref "R38") (pin "1") (pinfunction "1_1") (pintype "passive"))
      (node (ref "U14") (pin "5") (pinfunction "INHIBIT_5") (pintype "input"))
    )
    (net (code "228") (name "Net-(U14-IOUT)") (class "Default")
      (node (ref "R50") (pin "2") (pinfunction "2_2") (pintype "passive"))
      (node (ref "U14") (pin "14") (pinfunction "IOUT_14") (pintype "output"))
    )
    (net (code "229") (name "Net-(U14-RS+)") (class "Default")
      (node (ref "C44") (pin "1") (pinfunction "1_1") (pintype "passive"))
      (node (ref "Q6") (pin "1") (pinfunction "D_1") (pintype "passive"))
      (node (ref "Q6") (pin "2") (pinfunction "D_2") (pintype "passive"))
      (node (ref "Q6") (pin "5") (pinfunction "D_5") (pintype "passive"))
      (node (ref "Q6") (pin "6") (pinfunction "D_6") (pintype "passive"))
      (node (ref "R63") (pin "1") (pinfunction "1_1") (pintype "passive"))
      (node (ref "U14") (pin "16") (pinfunction "RS+_16") (pintype "passive"))
    )
    (net (code "230") (name "Net-(U15-PG)") (class "Default")
      (node (ref "TP48") (pin "1") (pinfunction "1_1") (pintype "passive"))
      (node (ref "U15") (pin "13") (pinfunction "PG_13") (pintype "open_collector"))
    )
    (net (code "231") (name "Net-(U15-SYNC)") (class "Default")
      (node (ref "R34") (pin "1") (pinfunction "1_1") (pintype "passive"))
      (node (ref "R40") (pin "2") (pinfunction "2_2") (pintype "passive"))
      (node (ref "TP46") (pin "1") (pinfunction "1_1") (pintype "passive"))
      (node (ref "U15") (pin "5") (pinfunction "SYNC_5") (pintype "input"))
    )
    (net (code "232") (name "Net-(U16-IO6)") (class "Default")
      (node (ref "TP53") (pin "1") (pinfunction "1_1") (pintype "passive"))
      (node (ref "U16") (pin "11") (pinfunction "IO6_11") (pintype "bidirectional"))
    )
    (net (code "233") (name "Net-(U16-IO7)") (class "Default")
      (node (ref "TP56") (pin "1") (pinfunction "1_1") (pintype "passive"))
      (node (ref "U16") (pin "12") (pinfunction "IO7_12") (pintype "bidirectional"))
    )
    (net (code "234") (name "Net-(U16-~{RESET})") (class "Default")
      (node (ref "R72") (pin "1") (pinfunction "1_1") (pintype "passive"))
      (node (ref "U16") (pin "13") (pinfunction "~{RESET}_13") (pintype "input"))
    )
    (net (code "235") (name "Net-(U17-MISO)") (class "Default")
      (node (ref "U17") (pin "2") (pinfunction "MISO_2") (pintype "output"))
      (node (ref "U7") (pin "B13") (pinfunction "SPI0_D0_B13") (pintype "bidirectional"))
    )
    (net (code "236") (name "Net-(U17-MOSI)") (class "Default")
      (node (ref "U17") (pin "5") (pinfunction "MOSI_5") (pintype "input"))
      (node (ref "U7") (pin "B14") (pinfunction "SPI0_D1_B14") (pintype "bidirectional"))
    )
    (net (code "237") (name "Net-(U17-SCK)") (class "Default")
      (node (ref "U17") (pin "6") (pinfunction "SCK_6") (pintype "input"))
      (node (ref "U7") (pin "A13") (pinfunction "SPI0_SCLK_A13") (pintype "bidirectional"))
    )
    (net (code "238") (name "Net-(U17-~{CS})") (class "Default")
      (node (ref "U17") (pin "1") (pinfunction "~{CS}_1") (pintype "input"))
      (node (ref "U7") (pin "A14") (pinfunction "SPI0_CS0_A14") (pintype "bidirectional"))
    )
    (net (code "239") (name "Net-(U17-~{HOLD})") (class "Default")
      (node (ref "TP69") (pin "1") (pinfunction "1_1") (pintype "bidirectional"))
      (node (ref "U17") (pin "7") (pinfunction "~{HOLD}_7") (pintype "input"))
    )
    (net (code "240") (name "Net-(U17-~{WP})") (class "Default")
      (node (ref "R59") (pin "1") (pinfunction "1_1") (pintype "passive"))
      (node (ref "R60") (pin "2") (pinfunction "2_2") (pintype "passive"))
      (node (ref "U17") (pin "3") (pinfunction "~{WP}_3") (pintype "input"))
    )
    (net (code "241") (name "Net-(U19-IREF2)") (class "Default")
      (node (ref "C47") (pin "1") (pinfunction "1_1") (pintype "passive"))
      (node (ref "R81") (pin "2") (pinfunction "2_2") (pintype "passive"))
      (node (ref "U19") (pin "8") (pinfunction "IREF2_8") (pintype "passive"))
    )
    (net (code "242") (name "Net-(U19-VBIAS)") (class "Default")
      (node (ref "R82") (pin "1") (pinfunction "1_1") (pintype "passive"))
      (node (ref "U19") (pin "16") (pinfunction "VBIAS_16") (pintype "power_in"))
    )
    (net (code "243") (name "Net-(U19-VCC1)") (class "Default")
      (node (ref "L8") (pin "1") (pinfunction "1_1") (pintype "passive"))
      (node (ref "U19") (pin "20") (pinfunction "VCC1_20") (pintype "power_in"))
    )
    (net (code "244") (name "Net-(U19-VCC2)") (class "Default")
      (node (ref "L10") (pin "1") (pinfunction "1_1") (pintype "bidirectional"))
      (node (ref "U19") (pin "18") (pinfunction "VCC2_18") (pintype "power_in"))
    )
    (net (code "245") (name "Net-(U20-OUT)") (class "Default")
      (node (ref "C42") (pin "1") (pinfunction "1_1") (pintype "passive"))
      (node (ref "C53") (pin "1") (pinfunction "1_1") (pintype "passive"))
      (node (ref "FB1") (pin "1") (pinfunction "1_1") (pintype "passive"))
      (node (ref "U20") (pin "1") (pinfunction "OUT_1") (pintype "output"))
    )
    (net (code "246") (name "Net-(U21-OUT)") (class "Default")
      (node (ref "C55") (pin "1") (pinfunction "1_1") (pintype "passive"))
      (node (ref "C56") (pin "1") (pinfunction "1_1") (pintype "passive"))
      (node (ref "FB4") (pin "1") (pinfunction "1_1") (pintype "passive"))
      (node (ref "U21") (pin "1") (pinfunction "OUT_1") (pintype "output"))
    )
    (net (code "247") (name "Net-(Y3-X2)") (class "Default")
      (node (ref "C64") (pin "1") (pinfunction "1_1") (pintype "passive"))
      (node (ref "R98") (pin "2") (pinfunction "2_2") (pintype "passive"))
      (node (ref "Y3") (pin "1") (pinfunction "X2_1") (pintype "passive"))
    )
    (net (code "248") (name "ON{slash}~{OFF}") (class "Default")
      (node (ref "C34") (pin "1") (pinfunction "1_1") (pintype "passive"))
      (node (ref "Q4") (pin "1") (pinfunction "G_1") (pintype "passive"))
      (node (ref "R46") (pin "2") (pinfunction "2_2") (pintype "passive"))
      (node (ref "R49") (pin "2") (pinfunction "2_2") (pintype "passive"))
      (node (ref "TP50") (pin "1") (pinfunction "1_1") (pintype "passive"))
      (node (ref "U14") (pin "1") (pinfunction "VCC_1") (pintype "power_in"))
      (node (ref "U16") (pin "8") (pinfunction "IO3_8") (pintype "bidirectional"))
    )
    (net (code "249") (name "OPD_PWR") (class "Default")
      (node (ref "J4") (pin "15") (pinfunction "15_15") (pintype "passive"))
      (node (ref "J4") (pin "16") (pinfunction "16_16") (pintype "passive"))
      (node (ref "R71") (pin "1") (pinfunction "1_1") (pintype "passive"))
    )
    (net (code "250") (name "OPD_SCL") (class "Default")
      (node (ref "J4") (pin "13") (pinfunction "13_13") (pintype "passive"))
      (node (ref "J4") (pin "14") (pinfunction "14_14") (pintype "passive"))
      (node (ref "R48") (pin "1") (pinfunction "1_1") (pintype "passive"))
    )
    (net (code "251") (name "OPD_SDA") (class "Default")
      (node (ref "J4") (pin "11") (pinfunction "11_11") (pintype "passive"))
      (node (ref "J4") (pin "12") (pinfunction "12_12") (pintype "passive"))
      (node (ref "R41") (pin "1") (pinfunction "1_1") (pintype "passive"))
    )
    (net (code "252") (name "OSC0_GND") (class "Default")
      (node (ref "C19") (pin "1") (pinfunction "1_1") (pintype "passive"))
      (node (ref "C22") (pin "1") (pinfunction "1_1") (pintype "passive"))
      (node (ref "U7") (pin "N15") (pinfunction "OSC0_GND_N15") (pintype "bidirectional"))
    )
    (net (code "253") (name "OSC0_IN") (class "Default")
      (node (ref "C19") (pin "2") (pinfunction "2_2") (pintype "passive"))
      (node (ref "R13") (pin "2") (pinfunction "2_2") (pintype "passive"))
      (node (ref "U7") (pin "P16") (pinfunction "OSC0_IN_P16") (pintype "bidirectional"))
      (node (ref "Y1") (pin "1") (pinfunction "X1_1") (pintype "passive"))
    )
    (net (code "254") (name "OSC0_OUT") (class "Default")
      (node (ref "C22") (pin "2") (pinfunction "2_2") (pintype "passive"))
      (node (ref "R13") (pin "1") (pinfunction "1_1") (pintype "passive"))
      (node (ref "U7") (pin "N16") (pinfunction "OSC0_OUT_N16") (pintype "bidirectional"))
      (node (ref "Y1") (pin "3") (pinfunction "X2_3") (pintype "passive"))
    )
    (net (code "255") (name "PA_ENABLE") (class "Default")
      (node (ref "R17") (pin "2") (pinfunction "2_2") (pintype "passive"))
      (node (ref "TP11") (pin "1") (pinfunction "1_1") (pintype "passive"))
      (node (ref "U6") (pin "2") (pinfunction "B_2") (pintype "input"))
      (node (ref "U7") (pin "H16") (pinfunction "MII1_TX_CLK_H16") (pintype "bidirectional"))
    )
    (net (code "256") (name "PA_THERMISTOR") (class "Default")
      (node (ref "C23") (pin "1") (pinfunction "1_1") (pintype "passive"))
      (node (ref "R18") (pin "2") (pinfunction "2_2") (pintype "passive"))
      (node (ref "RT2") (pin "1") (pinfunction "1_1") (pintype "passive"))
      (node (ref "TP10") (pin "1") (pinfunction "1_1") (pintype "passive"))
      (node (ref "U7") (pin "C9") (pinfunction "AIN6_C9") (pintype "bidirectional"))
    )
    (net (code "257") (name "PA_TOGGLE") (class "Default")
      (node (ref "R30") (pin "1") (pinfunction "1_1") (pintype "passive"))
      (node (ref "R81") (pin "1") (pinfunction "1_1") (pintype "passive"))
      (node (ref "U19") (pin "6") (pinfunction "IREF1_6") (pintype "passive"))
      (node (ref "U8") (pin "1") (pinfunction "VOUT_1") (pintype "output"))
    )
    (net (code "258") (name "PB6{slash}SCL") (class "Default")
      (node (ref "TP67") (pin "1") (pinfunction "1_1") (pintype "passive"))
      (node (ref "U16") (pin "4") (pinfunction "IO0_4") (pintype "bidirectional"))
    )
    (net (code "259") (name "PB7{slash}SDA") (class "Default")
      (node (ref "TP68") (pin "1") (pinfunction "1_1") (pintype "passive"))
      (node (ref "U16") (pin "5") (pinfunction "IO1_5") (pintype "bidirectional"))
    )
    (net (code "260") (name "PEN-SCL-FILT") (class "Default")
      (node (ref "Q3") (pin "6") (pinfunction "D_6") (pintype "passive"))
      (node (ref "R37") (pin "2") (pinfunction "2_2") (pintype "passive"))
      (node (ref "R65") (pin "1") (pinfunction "1_1") (pintype "passive"))
      (node (ref "R67") (pin "1") (pinfunction "1_1") (pintype "passive"))
      (node (ref "R69") (pin "1") (pinfunction "1_1") (pintype "passive"))
      (node (ref "TP42") (pin "1") (pinfunction "1_1") (pintype "passive"))
      (node (ref "TP66") (pin "1") (pinfunction "1_1") (pintype "passive"))
      (node (ref "U16") (pin "15") (pinfunction "SCL_15") (pintype "input"))
    )
    (net (code "261") (name "PEN-SDA-FILT") (class "Default")
      (node (ref "Q3") (pin "4") (pinfunction "D_4") (pintype "passive"))
      (node (ref "R45") (pin "2") (pinfunction "2_2") (pintype "passive"))
      (node (ref "R66") (pin "2") (pinfunction "2_2") (pintype "passive"))
      (node (ref "R68") (pin "2") (pinfunction "2_2") (pintype "passive"))
      (node (ref "R70") (pin "2") (pinfunction "2_2") (pintype "passive"))
      (node (ref "TP41") (pin "1") (pinfunction "1_1") (pintype "passive"))
      (node (ref "TP65") (pin "1") (pinfunction "1_1") (pintype "passive"))
      (node (ref "U16") (pin "16") (pinfunction "SDA_16") (pintype "bidirectional"))
    )
    (net (code "262") (name "PMIC_PGOOD") (class "Default")
      (node (ref "TP110") (pin "1") (pinfunction "1_1") (pintype "bidirectional"))
      (node (ref "U4") (pin "2") (pinfunction "A_2") (pintype "bidirectional"))
      (node (ref "U7") (pin "N12") (pinfunction "PMIC_PGOOD_N12") (pintype "output"))
      (node (ref "U7") (pin "P11") (pinfunction "PWRONRSTN_P11") (pintype "bidirectional"))
    )
    (net (code "263") (name "POUT") (class "Default")
      (node (ref "TP64") (pin "1") (pinfunction "1_1") (pintype "passive"))
      (node (ref "U14") (pin "13") (pinfunction "POUT_13") (pintype "output"))
    )
    (net (code "264") (name "RESET#") (class "Default")
      (node (ref "JP1") (pin "1") (pinfunction "1_1") (pintype "passive"))
      (node (ref "TP109") (pin "1") (pinfunction "1_1") (pintype "bidirectional"))
      (node (ref "U4") (pin "4") (pinfunction "Y_4") (pintype "bidirectional"))
      (node (ref "U7") (pin "R11") (pinfunction "WARMRSTN_R11") (pintype "bidirectional"))
    )
    (net (code "265") (name "SPARE1") (class "Default")
      (node (ref "J4") (pin "10") (pinfunction "10_10") (pintype "passive"))
      (node (ref "J4") (pin "9") (pinfunction "9_9") (pintype "passive"))
      (node (ref "TP58") (pin "1") (pinfunction "1_1") (pintype "bidirectional"))
    )
    (net (code "266") (name "SPARE2") (class "Default")
      (node (ref "J4") (pin "7") (pinfunction "7_7") (pintype "passive"))
      (node (ref "J4") (pin "8") (pinfunction "8_8") (pintype "passive"))
      (node (ref "TP59") (pin "1") (pinfunction "1_1") (pintype "bidirectional"))
    )
    (net (code "267") (name "SPARE3") (class "Default")
      (node (ref "J4") (pin "5") (pinfunction "5_5") (pintype "passive"))
      (node (ref "J4") (pin "6") (pinfunction "6_6") (pintype "passive"))
      (node (ref "TP60") (pin "1") (pinfunction "1_1") (pintype "bidirectional"))
    )
    (net (code "268") (name "SPARE4") (class "Default")
      (node (ref "J4") (pin "3") (pinfunction "3_3") (pintype "passive"))
      (node (ref "J4") (pin "4") (pinfunction "4_4") (pintype "passive"))
      (node (ref "TP61") (pin "1") (pinfunction "1_1") (pintype "bidirectional"))
    )
    (net (code "269") (name "TX_OUT") (class "Default")
      (node (ref "C49") (pin "2") (pinfunction "2_2") (pintype "passive"))
      (node (ref "J6") (pin "RF") (pinfunction "CENTER_RF") (pintype "passive"))
    )
    (net (code "270") (name "UART0_RX") (class "Default")
      (node (ref "J1") (pin "12") (pinfunction "CARD-RX_12") (pintype "passive"))
      (node (ref "TP146") (pin "1") (pinfunction "1_1") (pintype "bidirectional"))
      (node (ref "U7") (pin "A12") (pinfunction "UART0_RXD_A12") (pintype "bidirectional"))
    )
    (net (code "271") (name "UART0_TX") (class "Default")
      (node (ref "J1") (pin "13") (pinfunction "CARD-TX_13") (pintype "passive"))
      (node (ref "TP142") (pin "1") (pinfunction "1_1") (pintype "bidirectional"))
      (node (ref "U7") (pin "B12") (pinfunction "UART0_TXD_B12") (pintype "bidirectional"))
    )
    (net (code "272") (name "USB_CAM_N") (class "Default")
      (node (ref "C57") (pin "1") (pinfunction "1_1") (pintype "passive"))
      (node (ref "J10") (pin "5") (pinfunction "5_5") (pintype "passive"))
      (node (ref "R77") (pin "1") (pinfunction "1_1") (pintype "passive"))
      (node (ref "R78") (pin "2") (pinfunction "2_2") (pintype "passive"))
    )
    (net (code "273") (name "USB_CAM_P") (class "Default")
      (node (ref "C58") (pin "1") (pinfunction "1_1") (pintype "passive"))
      (node (ref "J10") (pin "4") (pinfunction "4_4") (pintype "passive"))
      (node (ref "R79") (pin "1") (pinfunction "1_1") (pintype "passive"))
      (node (ref "R83") (pin "2") (pinfunction "2_2") (pintype "passive"))
    )
    (net (code "274") (name "USB_CAM_VBUS") (class "Default")
      (node (ref "FB3") (pin "2") (pinfunction "2_2") (pintype "passive"))
      (node (ref "J10") (pin "6") (pinfunction "6_6") (pintype "passive"))
      (node (ref "TP1") (pin "1") (pinfunction "1_1") (pintype "passive"))
    )
    (net (code "275") (name "USB_DEV_N") (class "Default")
      (node (ref "J1") (pin "5") (pinfunction "DEVICE-D-_5") (pintype "passive"))
      (node (ref "U1") (pin "6") (pinfunction "I4_6") (pintype "bidirectional"))
      (node (ref "U7") (pin "K16") (pinfunction "USB0_DM_K16") (pintype "bidirectional"))
    )
    (net (code "276") (name "USB_DEV_P") (class "Default")
      (node (ref "J1") (pin "4") (pinfunction "DEVICE-D+_4") (pintype "passive"))
      (node (ref "U1") (pin "4") (pinfunction "I3_4") (pintype "bidirectional"))
      (node (ref "U7") (pin "K15") (pinfunction "USB0_DP_K15") (pintype "bidirectional"))
    )
    (net (code "277") (name "USB_DEV_VBUS") (class "Default")
      (node (ref "FB2") (pin "1") (pinfunction "1_1") (pintype "passive"))
      (node (ref "J1") (pin "1") (pinfunction "VBUSP_1") (pintype "passive"))
      (node (ref "J1") (pin "2") (pinfunction "VBUSP_2") (pintype "passive"))
    )
    (net (code "278") (name "USB_HO_N") (class "Default")
      (node (ref "C59") (pin "1") (pinfunction "1_1") (pintype "passive"))
      (node (ref "J1") (pin "8") (pinfunction "HOST-D-_8") (pintype "passive"))
      (node (ref "R89") (pin "1") (pinfunction "1_1") (pintype "passive"))
      (node (ref "R90") (pin "2") (pinfunction "2_2") (pintype "passive"))
    )
    (net (code "279") (name "USB_HO_P") (class "Default")
      (node (ref "C60") (pin "1") (pinfunction "1_1") (pintype "passive"))
      (node (ref "J1") (pin "7") (pinfunction "HOST-D+_7") (pintype "passive"))
      (node (ref "R91") (pin "1") (pinfunction "1_1") (pintype "passive"))
      (node (ref "R92") (pin "2") (pinfunction "2_2") (pintype "passive"))
    )
    (net (code "280") (name "USB_HO_VBUS") (class "Default")
      (node (ref "FB4") (pin "2") (pinfunction "2_2") (pintype "passive"))
      (node (ref "J1") (pin "17") (pinfunction "DEBUG-0_17") (pintype "passive"))
      (node (ref "TP13") (pin "1") (pinfunction "1_1") (pintype "passive"))
    )
    (net (code "281") (name "USB_WIFI_N") (class "Default")
      (node (ref "C61") (pin "1") (pinfunction "1_1") (pintype "passive"))
      (node (ref "J2") (pin "5") (pinfunction "5_5") (pintype "passive"))
      (node (ref "R93") (pin "1") (pinfunction "1_1") (pintype "passive"))
      (node (ref "R94") (pin "2") (pinfunction "2_2") (pintype "passive"))
    )
    (net (code "282") (name "USB_WIFI_P") (class "Default")
      (node (ref "C62") (pin "1") (pinfunction "1_1") (pintype "passive"))
      (node (ref "J2") (pin "4") (pinfunction "4_4") (pintype "passive"))
      (node (ref "R95") (pin "1") (pinfunction "1_1") (pintype "passive"))
      (node (ref "R96") (pin "2") (pinfunction "2_2") (pintype "passive"))
    )
    (net (code "283") (name "USB_WIFI_VBUS") (class "Default")
      (node (ref "FB1") (pin "2") (pinfunction "2_2") (pintype "passive"))
      (node (ref "J2") (pin "6") (pinfunction "6_6") (pintype "passive"))
      (node (ref "R21") (pin "1") (pinfunction "1_1") (pintype "passive"))
      (node (ref "R29") (pin "1") (pinfunction "1_1") (pintype "passive"))
      (node (ref "TP15") (pin "1") (pinfunction "1_1") (pintype "passive"))
    )
    (net (code "284") (name "VBUS") (class "Default")
      (node (ref "J4") (pin "21") (pinfunction "21_21") (pintype "passive"))
      (node (ref "J4") (pin "22") (pinfunction "22_22") (pintype "passive"))
      (node (ref "J4") (pin "23") (pinfunction "23_23") (pintype "passive"))
      (node (ref "J4") (pin "24") (pinfunction "24_24") (pintype "passive"))
      (node (ref "J4") (pin "25") (pinfunction "25_25") (pintype "passive"))
      (node (ref "J4") (pin "26") (pinfunction "26_26") (pintype "passive"))
      (node (ref "Q6") (pin "4") (pinfunction "S_4") (pintype "passive"))
      (node (ref "R52") (pin "2") (pinfunction "2_2") (pintype "passive"))
    )
    (net (code "285") (name "VBUSP") (class "Default")
      (node (ref "C16") (pin "1") (pinfunction "1_1") (pintype "passive"))
      (node (ref "C17") (pin "1") (pinfunction "1_1") (pintype "passive"))
      (node (ref "C33") (pin "2") (pinfunction "2_2") (pintype "passive"))
      (node (ref "C37") (pin "1") (pinfunction "1_1") (pintype "passive"))
      (node (ref "C38") (pin "1") (pinfunction "1_1") (pintype "passive"))
      (node (ref "Q5") (pin "1") (pinfunction "D_1") (pintype "passive"))
      (node (ref "Q5") (pin "2") (pinfunction "D_2") (pintype "passive"))
      (node (ref "Q5") (pin "5") (pinfunction "D_5") (pintype "passive"))
      (node (ref "Q5") (pin "6") (pinfunction "D_6") (pintype "passive"))
      (node (ref "R12") (pin "2") (pinfunction "2_2") (pintype "passive"))
      (node (ref "R34") (pin "2") (pinfunction "2_2") (pintype "passive"))
      (node (ref "R61") (pin "2") (pinfunction "2_2") (pintype "passive"))
      (node (ref "TP55") (pin "1") (pinfunction "1_1") (pintype "passive"))
      (node (ref "U15") (pin "2") (pinfunction "VIN_2") (pintype "power_in"))
      (node (ref "U15") (pin "3") (pinfunction "VIN_3") (pintype "power_in"))
      (node (ref "U15") (pin "4") (pinfunction "EN_4") (pintype "input"))
      (node (ref "U15") (pin "8") (pinfunction "VIN_8") (pintype "power_in"))
      (node (ref "U5") (pin "2") (pinfunction "VIN_2") (pintype "power_in"))
      (node (ref "U5") (pin "3") (pinfunction "VIN_3") (pintype "power_in"))
      (node (ref "U5") (pin "4") (pinfunction "EN_4") (pintype "input"))
      (node (ref "U5") (pin "8") (pinfunction "VIN_8") (pintype "power_in"))
    )
    (net (code "286") (name "VDD") (class "Default")
      (node (ref "TP3") (pin "1") (pinfunction "1_1") (pintype "bidirectional"))
      (node (ref "U7") (pin "K6") (pinfunction "SYS_VOUT_K6") (pintype "power_in"))
      (node (ref "U7") (pin "K7") (pinfunction "SYS_VOUT_K7") (pintype "power_in"))
      (node (ref "U7") (pin "L6") (pinfunction "SYS_VOUT_L6") (pintype "power_in"))
      (node (ref "U7") (pin "L7") (pinfunction "SYS_VOUT_L7") (pintype "power_in"))
    )
    (net (code "287") (name "VIN_USB") (class "Default")
      (node (ref "C13") (pin "1") (pinfunction "1_1") (pintype "passive"))
      (node (ref "C4") (pin "1") (pinfunction "1_1") (pintype "passive"))
      (node (ref "FB2") (pin "2") (pinfunction "2_2") (pintype "passive"))
      (node (ref "TP2") (pin "1") (pinfunction "1_1") (pintype "bidirectional"))
      (node (ref "U1") (pin "5") (pinfunction "VCC_5") (pintype "power_in"))
      (node (ref "U7") (pin "J16") (pinfunction "USB0_VBUS_J16") (pintype "bidirectional"))
      (node (ref "U7") (pin "P9") (pinfunction "VIN_USB_P9") (pintype "power_in"))
      (node (ref "U7") (pin "R9") (pinfunction "VIN_USB_R9") (pintype "power_in"))
      (node (ref "U7") (pin "T9") (pinfunction "VIN_USB_T9") (pintype "power_in"))
    )
    (net (code "288") (name "VPD") (class "Default")
      (node (ref "C39") (pin "2") (pinfunction "2_2") (pintype "passive"))
      (node (ref "R32") (pin "2") (pinfunction "2_2") (pintype "passive"))
      (node (ref "R36") (pin "2") (pinfunction "2_2") (pintype "passive"))
      (node (ref "R44") (pin "2") (pinfunction "2_2") (pintype "passive"))
      (node (ref "R53") (pin "2") (pinfunction "2_2") (pintype "passive"))
      (node (ref "R55") (pin "2") (pinfunction "2_2") (pintype "passive"))
      (node (ref "R57") (pin "2") (pinfunction "2_2") (pintype "passive"))
      (node (ref "R71") (pin "2") (pinfunction "2_2") (pintype "passive"))
      (node (ref "R72") (pin "2") (pinfunction "2_2") (pintype "passive"))
      (node (ref "TP63") (pin "1") (pinfunction "1_1") (pintype "passive"))
      (node (ref "U12") (pin "5") (pinfunction "VDD_5") (pintype "power_in"))
      (node (ref "U13") (pin "5") (pinfunction "VDD_5") (pintype "power_in"))
      (node (ref "U16") (pin "14") (pinfunction "V+_14") (pintype "power_in"))
    )
    (net (code "289") (name "WIFI_ENABLE") (class "Default")
      (node (ref "J2") (pin "1") (pinfunction "1_1") (pintype "passive"))
      (node (ref "R29") (pin "2") (pinfunction "2_2") (pintype "passive"))
    )
    (net (code "290") (name "WIFI_STATUS") (class "Default")
      (node (ref "D10") (pin "C") (pinfunction "C_C") (pintype "passive"))
      (node (ref "J2") (pin "2") (pinfunction "2_2") (pintype "passive"))
    )
    (net (code "291") (name "unconnected-(J1-NRST-Pad10)") (class "Default")
      (node (ref "J1") (pin "10") (pinfunction "NRST_10") (pintype "passive"))
    )
    (net (code "292") (name "unconnected-(J1-SWCLK-Pad15)") (class "Default")
      (node (ref "J1") (pin "15") (pinfunction "SWCLK_15") (pintype "passive"))
    )
    (net (code "293") (name "unconnected-(J1-SWDIO-Pad14)") (class "Default")
      (node (ref "J1") (pin "14") (pinfunction "SWDIO_14") (pintype "passive"))
    )
    (net (code "294") (name "unconnected-(J1-SWO-Pad16)") (class "Default")
      (node (ref "J1") (pin "16") (pinfunction "SWO_16") (pintype "passive"))
    )
    (net (code "295") (name "unconnected-(J1-VTARGET-Pad11)") (class "Default")
      (node (ref "J1") (pin "11") (pinfunction "VTARGET_11") (pintype "passive"))
    )
    (net (code "296") (name "unconnected-(J10-Pad1)") (class "Default")
      (node (ref "J10") (pin "1") (pinfunction "1_1") (pintype "passive"))
    )
    (net (code "297") (name "unconnected-(J10-Pad2)") (class "Default")
      (node (ref "J10") (pin "2") (pinfunction "2_2") (pintype "passive"))
    )
    (net (code "298") (name "unconnected-(R8-11-Pad1)") (class "Default")
      (node (ref "R8") (pin "1") (pinfunction "11_1") (pintype "passive"))
    )
    (net (code "299") (name "unconnected-(R10-33-Pad3)") (class "Default")
      (node (ref "R10") (pin "3") (pinfunction "33_3") (pintype "passive"))
    )
    (net (code "300") (name "unconnected-(R10-44-Pad4)") (class "Default")
      (node (ref "R10") (pin "4") (pinfunction "44_4") (pintype "passive"))
    )
    (net (code "301") (name "unconnected-(R10-66-Pad6)") (class "Default")
      (node (ref "R10") (pin "6") (pinfunction "66_6") (pintype "passive"))
    )
    (net (code "302") (name "unconnected-(R10-77-Pad7)") (class "Default")
      (node (ref "R10") (pin "7") (pinfunction "77_7") (pintype "passive"))
    )
    (net (code "303") (name "unconnected-(R10-88-Pad8)") (class "Default")
      (node (ref "R10") (pin "8") (pinfunction "88_8") (pintype "passive"))
    )
    (net (code "304") (name "unconnected-(R24-33-Pad3)") (class "Default")
      (node (ref "R24") (pin "3") (pinfunction "33_3") (pintype "passive"))
    )
    (net (code "305") (name "unconnected-(R24-44-Pad4)") (class "Default")
      (node (ref "R24") (pin "4") (pinfunction "44_4") (pintype "passive"))
    )
    (net (code "306") (name "unconnected-(R25-88-Pad8)") (class "Default")
      (node (ref "R25") (pin "8") (pinfunction "88_8") (pintype "passive"))
    )
    (net (code "307") (name "unconnected-(U1-I1-Pad1)") (class "Default")
      (node (ref "U1") (pin "1") (pinfunction "I1_1") (pintype "bidirectional"))
    )
    (net (code "308") (name "unconnected-(U1-I2-Pad3)") (class "Default")
      (node (ref "U1") (pin "3") (pinfunction "I2_3") (pintype "bidirectional"))
    )
    (net (code "309") (name "unconnected-(U2-~{PWRON4}-Pad21)") (class "Default")
      (node (ref "U2") (pin "21") (pinfunction "~{PWRON4}_21") (pintype "output"))
    )
    (net (code "310") (name "unconnected-(U7B-USB1_VBUS-PadM15)") (class "Default")
      (node (ref "U7") (pin "M15") (pinfunction "USB1_VBUS_M15") (pintype "bidirectional"))
    )
    (net (code "311") (name "unconnected-(U7C-GPMC_AD14-PadT6)") (class "Default")
      (node (ref "U7") (pin "T6") (pinfunction "GPMC_AD14_T6") (pintype "bidirectional"))
    )
    (net (code "312") (name "unconnected-(U7C-GPMC_AD15-PadP7)") (class "Default")
      (node (ref "U7") (pin "P7") (pinfunction "GPMC_AD15_P7") (pintype "bidirectional"))
    )
    (net (code "313") (name "unconnected-(U7C-MCASP0_ACLKR-PadA3)") (class "Default")
      (node (ref "U7") (pin "A3") (pinfunction "MCASP0_ACLKR_A3") (pintype "bidirectional"))
    )
    (net (code "314") (name "unconnected-(U7C-MCASP0_ACLKX-PadA1)") (class "Default")
      (node (ref "U7") (pin "A1") (pinfunction "MCASP0_ACLKX_A1") (pintype "bidirectional"))
    )
    (net (code "315") (name "unconnected-(U7C-MCASP0_AHCLKR-PadB1)") (class "Default")
      (node (ref "U7") (pin "B1") (pinfunction "MCASP0_AHCLKR_B1") (pintype "bidirectional"))
    )
    (net (code "316") (name "unconnected-(U7C-MCASP0_AHCLKX-PadC4)") (class "Default")
      (node (ref "U7") (pin "C4") (pinfunction "MCASP0_AHCLKX_C4") (pintype "bidirectional"))
    )
    (net (code "317") (name "unconnected-(U7C-MCASP0_AXR0-PadB2)") (class "Default")
      (node (ref "U7") (pin "B2") (pinfunction "MCASP0_AXR0_B2") (pintype "bidirectional"))
    )
    (net (code "318") (name "unconnected-(U7C-MCASP0_AXR1-PadC3)") (class "Default")
      (node (ref "U7") (pin "C3") (pinfunction "MCASP0_AXR1_C3") (pintype "bidirectional"))
    )
    (net (code "319") (name "unconnected-(U7C-MCASP0_FSR-PadB3)") (class "Default")
      (node (ref "U7") (pin "B3") (pinfunction "MCASP0_FSR_B3") (pintype "bidirectional"))
    )
    (net (code "320") (name "unconnected-(U7C-MCASP0_FSX-PadA2)") (class "Default")
      (node (ref "U7") (pin "A2") (pinfunction "MCASP0_FSX_A2") (pintype "bidirectional"))
    )
    (net (code "321") (name "unconnected-(U7C-UART1_CTSN-PadB10)") (class "Default")
      (node (ref "U7") (pin "B10") (pinfunction "UART1_CTSN_B10") (pintype "bidirectional"))
    )
    (net (code "322") (name "unconnected-(U7C-UART1_RTSN-PadA10)") (class "Default")
      (node (ref "U7") (pin "A10") (pinfunction "UART1_RTSN_A10") (pintype "bidirectional"))
    )
    (net (code "323") (name "unconnected-(U7C-XDMA_EVENT_INTR1-PadB4)") (class "Default")
      (node (ref "U7") (pin "B4") (pinfunction "XDMA_EVENT_INTR1_B4") (pintype "bidirectional"))
    )
    (net (code "324") (name "unconnected-(U7D-MII1_COL-PadF15)") (class "Default")
      (node (ref "U7") (pin "F15") (pinfunction "MII1_COL_F15") (pintype "bidirectional"))
    )
    (net (code "325") (name "unconnected-(U7D-MII1_CRS-PadF14)") (class "Default")
      (node (ref "U7") (pin "F14") (pinfunction "MII1_CRS_F14") (pintype "bidirectional"))
    )
    (net (code "326") (name "unconnected-(U7D-MII1_RXD0-PadE14)") (class "Default")
      (node (ref "U7") (pin "E14") (pinfunction "MII1_RXD0_E14") (pintype "bidirectional"))
    )
    (net (code "327") (name "unconnected-(U7D-MII1_RXD1-PadD16)") (class "Default")
      (node (ref "U7") (pin "D16") (pinfunction "MII1_RXD1_D16") (pintype "bidirectional"))
    )
    (net (code "328") (name "unconnected-(U7D-MII1_RXD2-PadD15)") (class "Default")
      (node (ref "U7") (pin "D15") (pinfunction "MII1_RXD2_D15") (pintype "bidirectional"))
    )
    (net (code "329") (name "unconnected-(U7D-MII1_RXD3-PadD14)") (class "Default")
      (node (ref "U7") (pin "D14") (pinfunction "MII1_RXD3_D14") (pintype "bidirectional"))
    )
    (net (code "330") (name "unconnected-(U7D-MII1_RX_CLK-PadE16)") (class "Default")
      (node (ref "U7") (pin "E16") (pinfunction "MII1_RX_CLK_E16") (pintype "bidirectional"))
    )
    (net (code "331") (name "unconnected-(U7D-MII1_RX_DV-PadF16)") (class "Default")
      (node (ref "U7") (pin "F16") (pinfunction "MII1_RX_DV_F16") (pintype "bidirectional"))
    )
    (net (code "332") (name "unconnected-(U7D-MII1_RX_ER-PadE15)") (class "Default")
      (node (ref "U7") (pin "E15") (pinfunction "MII1_RX_ER_E15") (pintype "bidirectional"))
    )
    (net (code "333") (name "unconnected-(U7D-MII1_TXD3-PadG15)") (class "Default")
      (node (ref "U7") (pin "G15") (pinfunction "MII1_TXD3_G15") (pintype "bidirectional"))
    )
    (net (code "334") (name "unconnected-(U8-NC-Pad3)") (class "Default")
      (node (ref "U8") (pin "3") (pinfunction "NC_3") (pintype "no_connect"))
    )
    (net (code "335") (name "unconnected-(U18-I3-Pad4)") (class "Default")
      (node (ref "U18") (pin "4") (pinfunction "I3_4") (pintype "bidirectional"))
    )
    (net (code "336") (name "~{FAULT}") (class "Default")
      (node (ref "Q2") (pin "3") (pinfunction "D_3") (pintype "passive"))
      (node (ref "R32") (pin "1") (pinfunction "1_1") (pintype "passive"))
      (node (ref "TP45") (pin "1") (pinfunction "1_1") (pintype "passive"))
      (node (ref "U16") (pin "7") (pinfunction "IO2_7") (pintype "bidirectional"))
    )
    (net (code "337") (name "~{SD}") (class "Default")
      (node (ref "J4") (pin "39") (pinfunction "39_39") (pintype "passive"))
      (node (ref "J4") (pin "40") (pinfunction "40_40") (pintype "passive"))
    )
  )
)
